# WS2812-Ring_v10.net
KiCad netlist of a schematic drawn in EAGLE
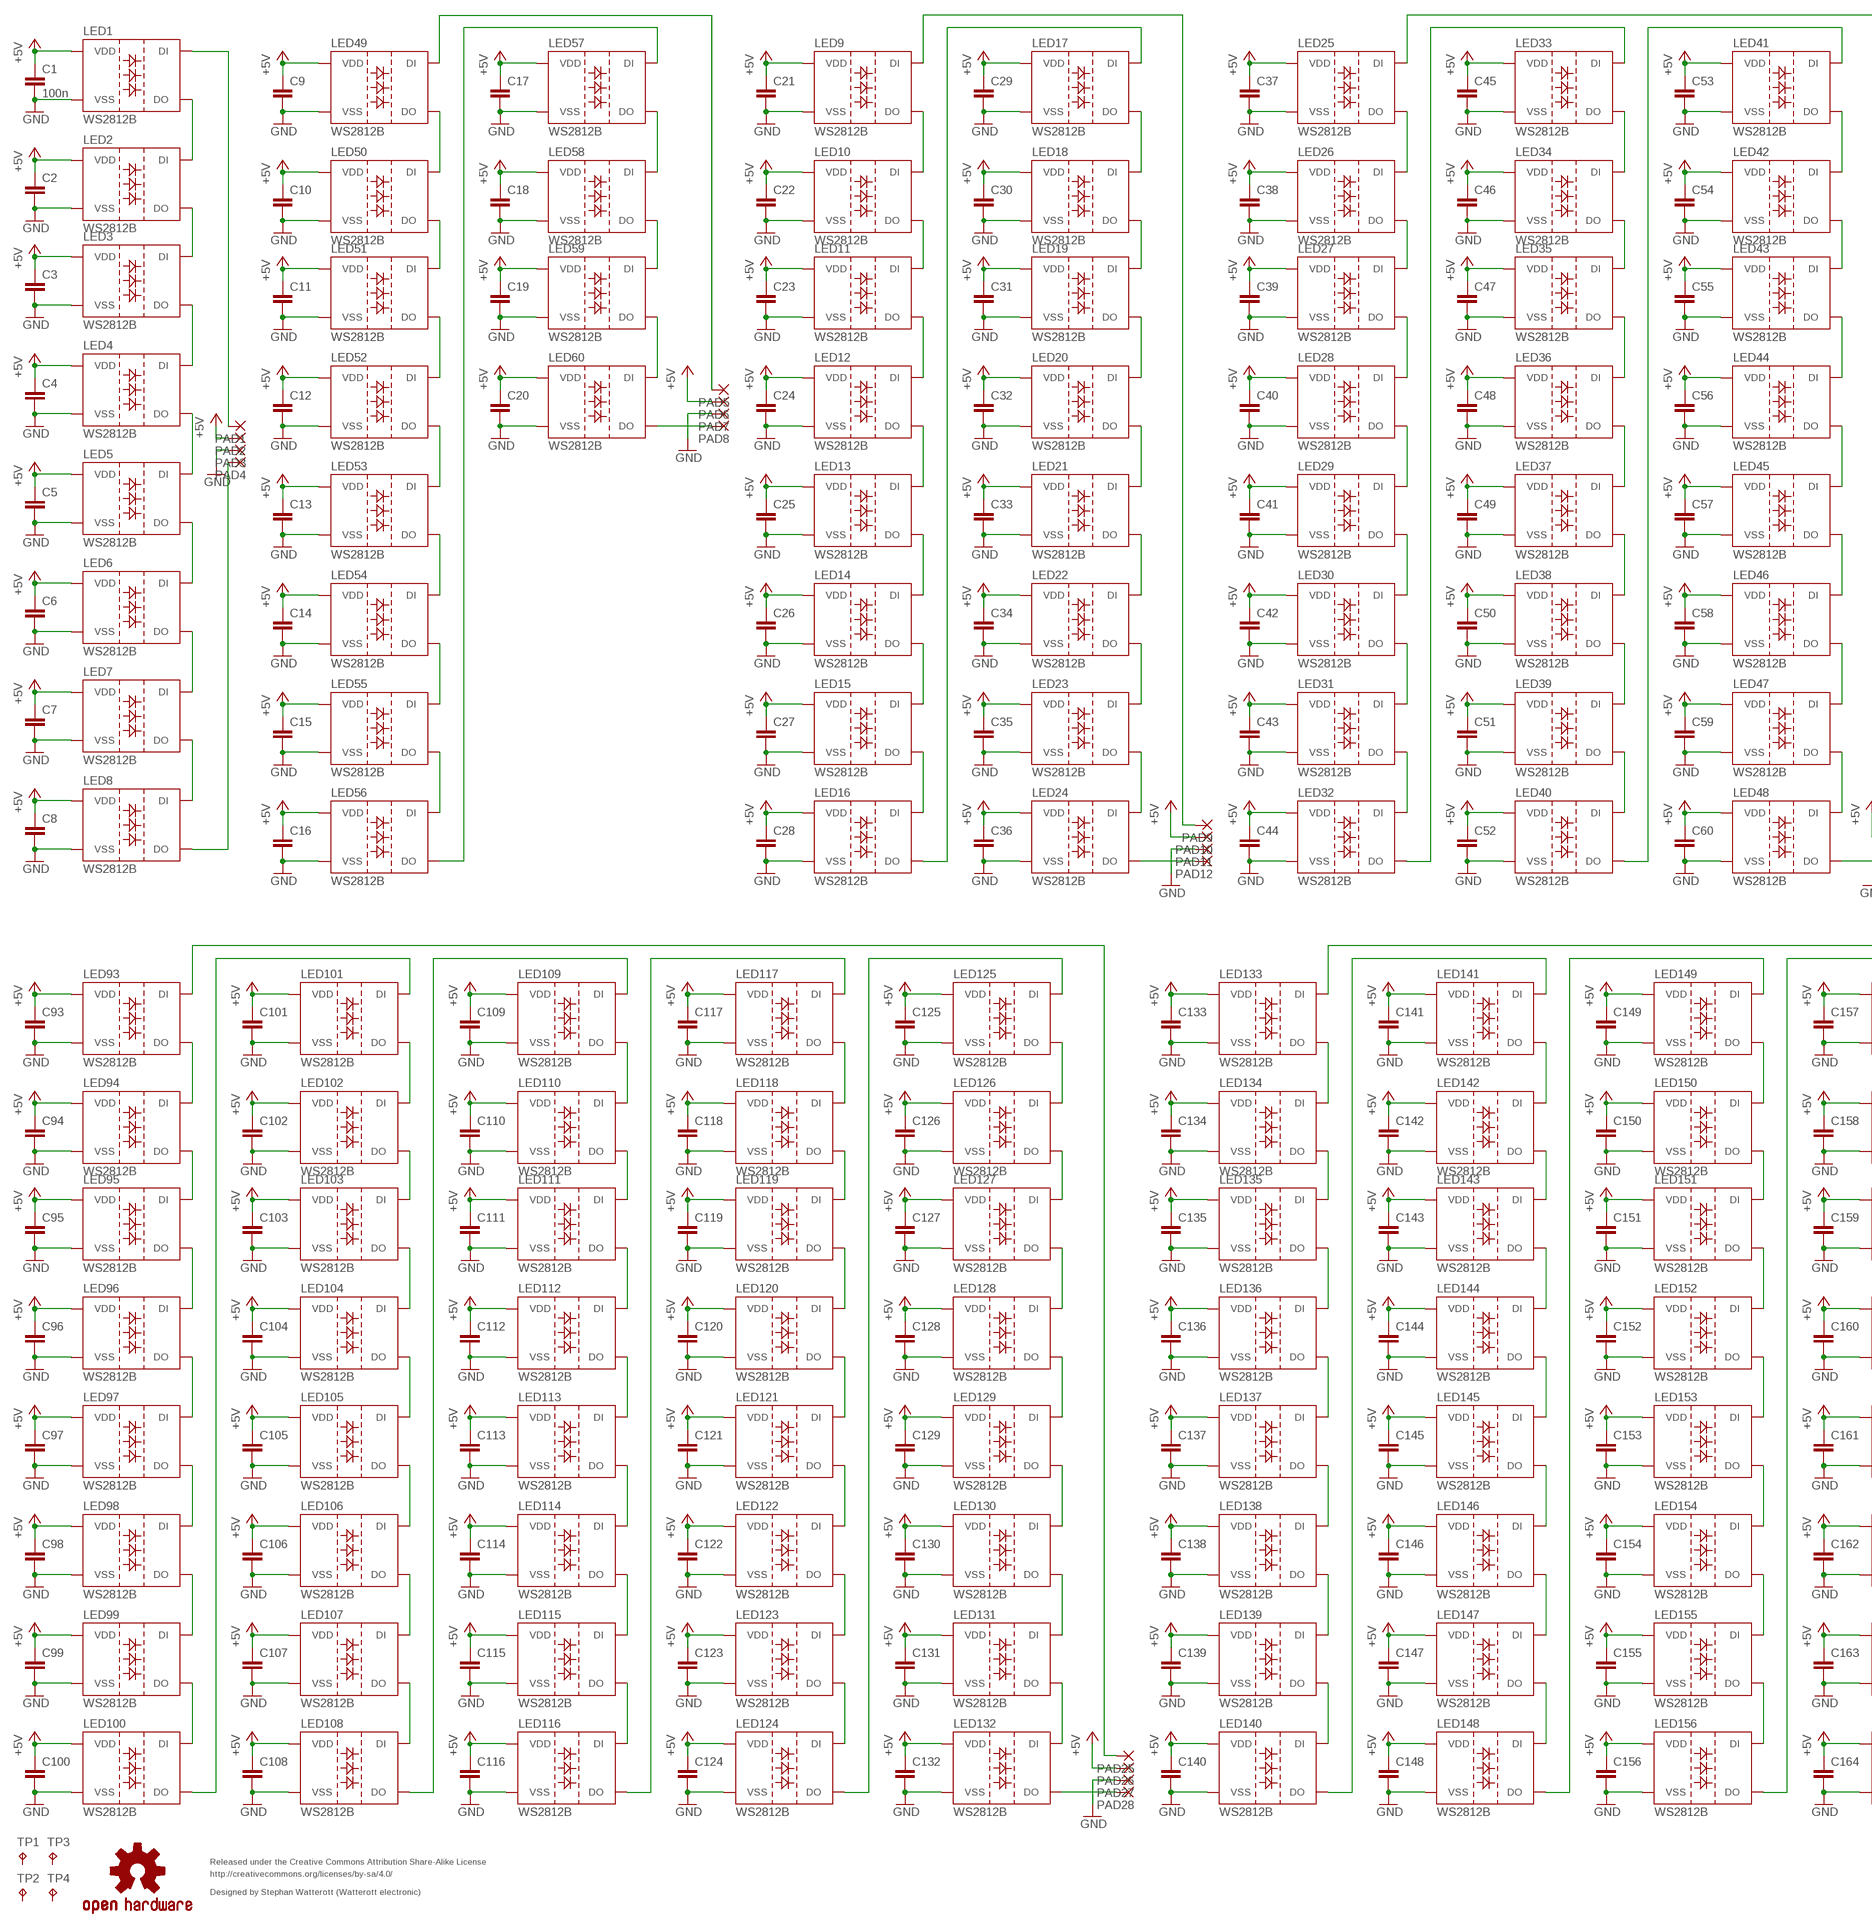
[diagram p0: schematic, sheet 1, part 1 of 2]
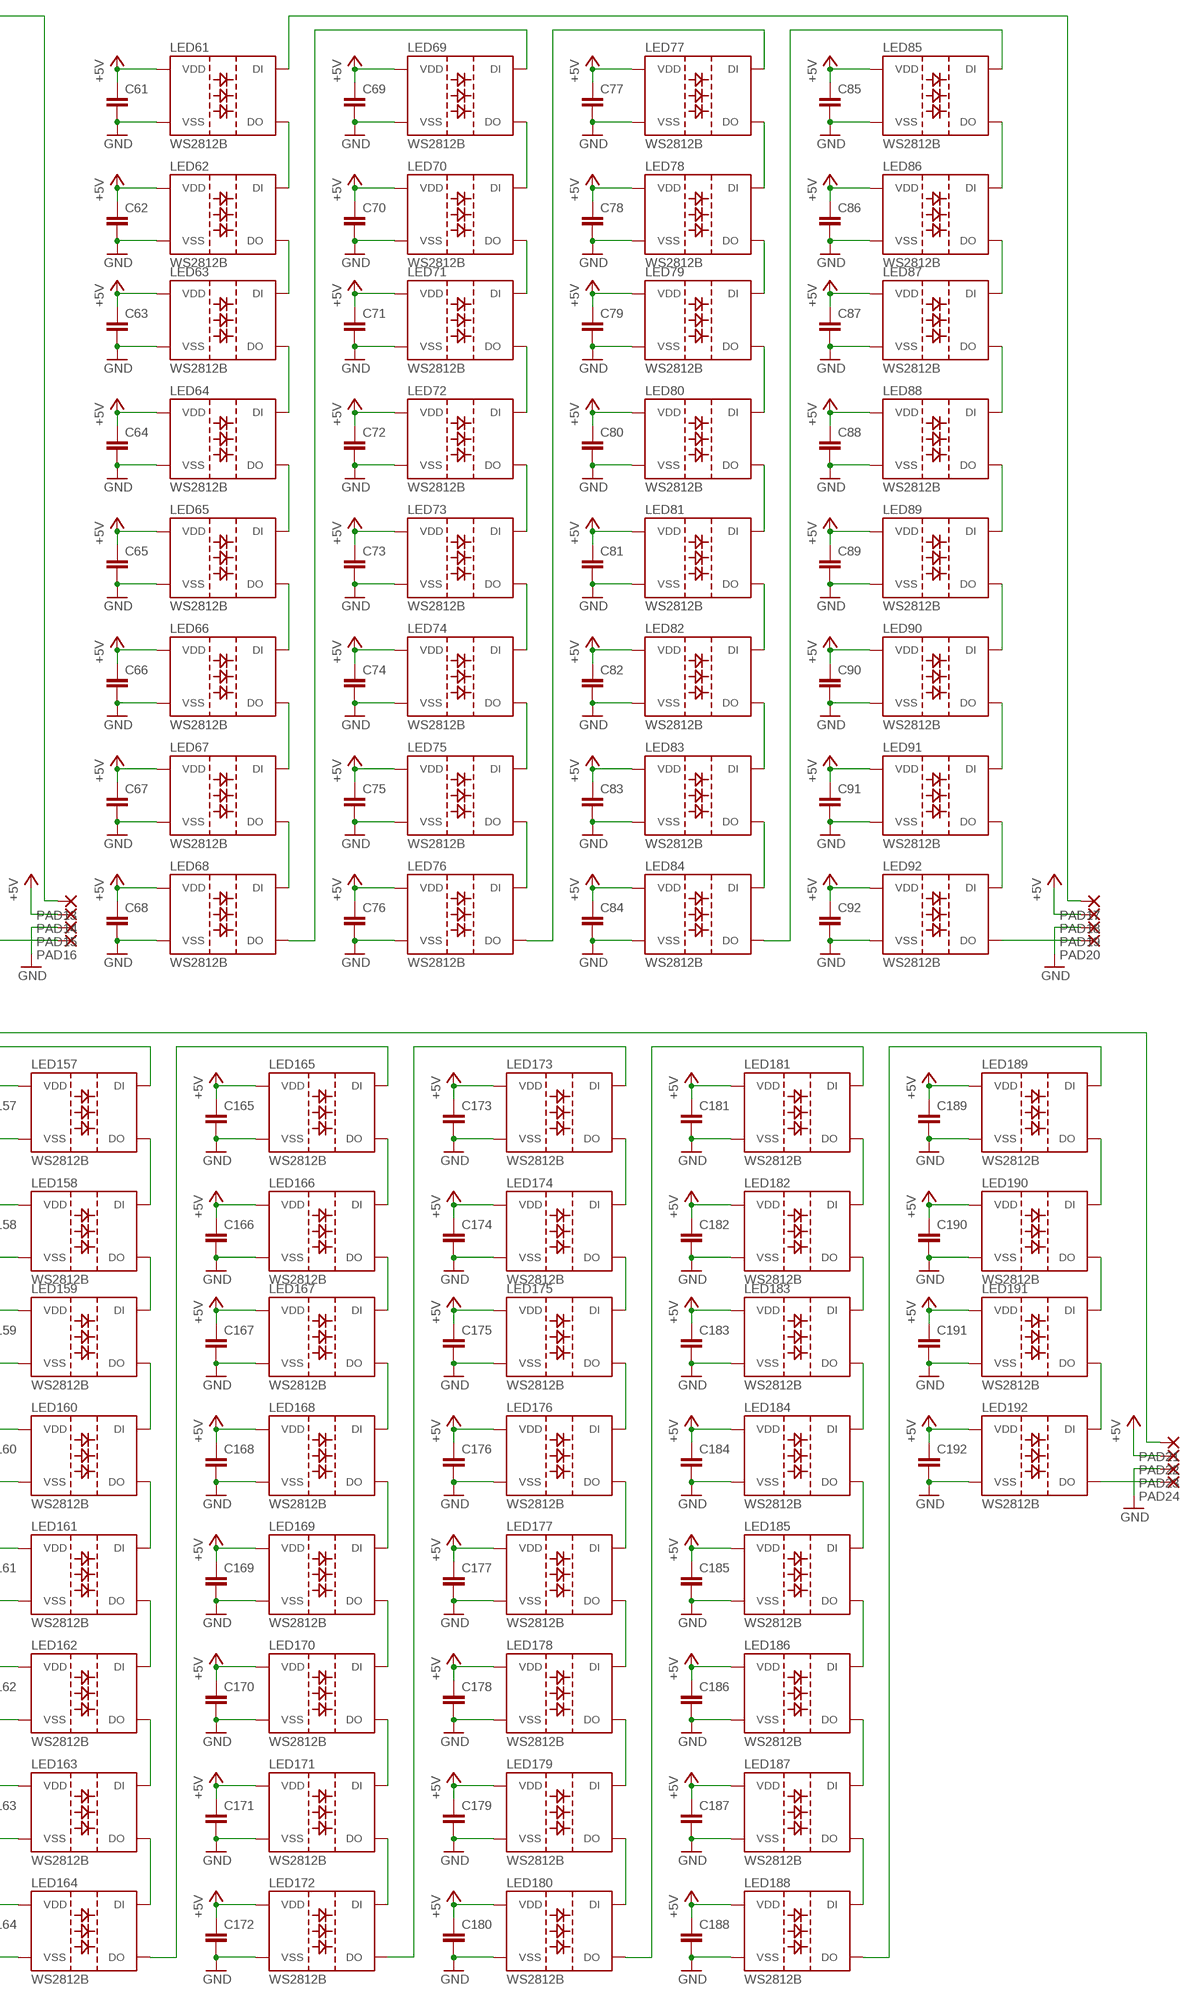
[diagram p1: schematic, sheet 1, part 2 of 2]

(export (version "E")
  (design (tool "Eeschema 10.0.6"))
  (components
    (comp (ref "C1")
      (value "100n")
      (footprint "eagle-import:C0402K")
      (libsource (lib "eagle-import") (part "C-EUC0402K"))
    )
    (comp (ref "C2")
      (value "C-EUC0402K")
      (footprint "eagle-import:C0402K")
      (libsource (lib "eagle-import") (part "C-EUC0402K"))
    )
    (comp (ref "C3")
      (value "C-EUC0402K")
      (footprint "eagle-import:C0402K")
      (libsource (lib "eagle-import") (part "C-EUC0402K"))
    )
    (comp (ref "C4")
      (value "C-EUC0402K")
      (footprint "eagle-import:C0402K")
      (libsource (lib "eagle-import") (part "C-EUC0402K"))
    )
    (comp (ref "C5")
      (value "C-EUC0402K")
      (footprint "eagle-import:C0402K")
      (libsource (lib "eagle-import") (part "C-EUC0402K"))
    )
    (comp (ref "C6")
      (value "C-EUC0402K")
      (footprint "eagle-import:C0402K")
      (libsource (lib "eagle-import") (part "C-EUC0402K"))
    )
    (comp (ref "C7")
      (value "C-EUC0402K")
      (footprint "eagle-import:C0402K")
      (libsource (lib "eagle-import") (part "C-EUC0402K"))
    )
    (comp (ref "C8")
      (value "C-EUC0402K")
      (footprint "eagle-import:C0402K")
      (libsource (lib "eagle-import") (part "C-EUC0402K"))
    )
    (comp (ref "C9")
      (value "C-EUC0402K")
      (footprint "eagle-import:C0402K")
      (libsource (lib "eagle-import") (part "C-EUC0402K"))
    )
    (comp (ref "C10")
      (value "C-EUC0402K")
      (footprint "eagle-import:C0402K")
      (libsource (lib "eagle-import") (part "C-EUC0402K"))
    )
    (comp (ref "C11")
      (value "C-EUC0402K")
      (footprint "eagle-import:C0402K")
      (libsource (lib "eagle-import") (part "C-EUC0402K"))
    )
    (comp (ref "C12")
      (value "C-EUC0402K")
      (footprint "eagle-import:C0402K")
      (libsource (lib "eagle-import") (part "C-EUC0402K"))
    )
    (comp (ref "C13")
      (value "C-EUC0402K")
      (footprint "eagle-import:C0402K")
      (libsource (lib "eagle-import") (part "C-EUC0402K"))
    )
    (comp (ref "C14")
      (value "C-EUC0402K")
      (footprint "eagle-import:C0402K")
      (libsource (lib "eagle-import") (part "C-EUC0402K"))
    )
    (comp (ref "C15")
      (value "C-EUC0402K")
      (footprint "eagle-import:C0402K")
      (libsource (lib "eagle-import") (part "C-EUC0402K"))
    )
    (comp (ref "C16")
      (value "C-EUC0402K")
      (footprint "eagle-import:C0402K")
      (libsource (lib "eagle-import") (part "C-EUC0402K"))
    )
    (comp (ref "C17")
      (value "C-EUC0402K")
      (footprint "eagle-import:C0402K")
      (libsource (lib "eagle-import") (part "C-EUC0402K"))
    )
    (comp (ref "C18")
      (value "C-EUC0402K")
      (footprint "eagle-import:C0402K")
      (libsource (lib "eagle-import") (part "C-EUC0402K"))
    )
    (comp (ref "C19")
      (value "C-EUC0402K")
      (footprint "eagle-import:C0402K")
      (libsource (lib "eagle-import") (part "C-EUC0402K"))
    )
    (comp (ref "C20")
      (value "C-EUC0402K")
      (footprint "eagle-import:C0402K")
      (libsource (lib "eagle-import") (part "C-EUC0402K"))
    )
    (comp (ref "C21")
      (value "C-EUC0402K")
      (footprint "eagle-import:C0402K")
      (libsource (lib "eagle-import") (part "C-EUC0402K"))
    )
    (comp (ref "C22")
      (value "C-EUC0402K")
      (footprint "eagle-import:C0402K")
      (libsource (lib "eagle-import") (part "C-EUC0402K"))
    )
    (comp (ref "C23")
      (value "C-EUC0402K")
      (footprint "eagle-import:C0402K")
      (libsource (lib "eagle-import") (part "C-EUC0402K"))
    )
    (comp (ref "C24")
      (value "C-EUC0402K")
      (footprint "eagle-import:C0402K")
      (libsource (lib "eagle-import") (part "C-EUC0402K"))
    )
    (comp (ref "C25")
      (value "C-EUC0402K")
      (footprint "eagle-import:C0402K")
      (libsource (lib "eagle-import") (part "C-EUC0402K"))
    )
    (comp (ref "C26")
      (value "C-EUC0402K")
      (footprint "eagle-import:C0402K")
      (libsource (lib "eagle-import") (part "C-EUC0402K"))
    )
    (comp (ref "C27")
      (value "C-EUC0402K")
      (footprint "eagle-import:C0402K")
      (libsource (lib "eagle-import") (part "C-EUC0402K"))
    )
    (comp (ref "C28")
      (value "C-EUC0402K")
      (footprint "eagle-import:C0402K")
      (libsource (lib "eagle-import") (part "C-EUC0402K"))
    )
    (comp (ref "C29")
      (value "C-EUC0402K")
      (footprint "eagle-import:C0402K")
      (libsource (lib "eagle-import") (part "C-EUC0402K"))
    )
    (comp (ref "C30")
      (value "C-EUC0402K")
      (footprint "eagle-import:C0402K")
      (libsource (lib "eagle-import") (part "C-EUC0402K"))
    )
    (comp (ref "C31")
      (value "C-EUC0402K")
      (footprint "eagle-import:C0402K")
      (libsource (lib "eagle-import") (part "C-EUC0402K"))
    )
    (comp (ref "C32")
      (value "C-EUC0402K")
      (footprint "eagle-import:C0402K")
      (libsource (lib "eagle-import") (part "C-EUC0402K"))
    )
    (comp (ref "C33")
      (value "C-EUC0402K")
      (footprint "eagle-import:C0402K")
      (libsource (lib "eagle-import") (part "C-EUC0402K"))
    )
    (comp (ref "C34")
      (value "C-EUC0402K")
      (footprint "eagle-import:C0402K")
      (libsource (lib "eagle-import") (part "C-EUC0402K"))
    )
    (comp (ref "C35")
      (value "C-EUC0402K")
      (footprint "eagle-import:C0402K")
      (libsource (lib "eagle-import") (part "C-EUC0402K"))
    )
    (comp (ref "C36")
      (value "C-EUC0402K")
      (footprint "eagle-import:C0402K")
      (libsource (lib "eagle-import") (part "C-EUC0402K"))
    )
    (comp (ref "C37")
      (value "C-EUC0402K")
      (footprint "eagle-import:C0402K")
      (libsource (lib "eagle-import") (part "C-EUC0402K"))
    )
    (comp (ref "C38")
      (value "C-EUC0402K")
      (footprint "eagle-import:C0402K")
      (libsource (lib "eagle-import") (part "C-EUC0402K"))
    )
    (comp (ref "C39")
      (value "C-EUC0402K")
      (footprint "eagle-import:C0402K")
      (libsource (lib "eagle-import") (part "C-EUC0402K"))
    )
    (comp (ref "C40")
      (value "C-EUC0402K")
      (footprint "eagle-import:C0402K")
      (libsource (lib "eagle-import") (part "C-EUC0402K"))
    )
    (comp (ref "C41")
      (value "C-EUC0402K")
      (footprint "eagle-import:C0402K")
      (libsource (lib "eagle-import") (part "C-EUC0402K"))
    )
    (comp (ref "C42")
      (value "C-EUC0402K")
      (footprint "eagle-import:C0402K")
      (libsource (lib "eagle-import") (part "C-EUC0402K"))
    )
    (comp (ref "C43")
      (value "C-EUC0402K")
      (footprint "eagle-import:C0402K")
      (libsource (lib "eagle-import") (part "C-EUC0402K"))
    )
    (comp (ref "C44")
      (value "C-EUC0402K")
      (footprint "eagle-import:C0402K")
      (libsource (lib "eagle-import") (part "C-EUC0402K"))
    )
    (comp (ref "C45")
      (value "C-EUC0402K")
      (footprint "eagle-import:C0402K")
      (libsource (lib "eagle-import") (part "C-EUC0402K"))
    )
    (comp (ref "C46")
      (value "C-EUC0402K")
      (footprint "eagle-import:C0402K")
      (libsource (lib "eagle-import") (part "C-EUC0402K"))
    )
    (comp (ref "C47")
      (value "C-EUC0402K")
      (footprint "eagle-import:C0402K")
      (libsource (lib "eagle-import") (part "C-EUC0402K"))
    )
    (comp (ref "C48")
      (value "C-EUC0402K")
      (footprint "eagle-import:C0402K")
      (libsource (lib "eagle-import") (part "C-EUC0402K"))
    )
    (comp (ref "C49")
      (value "C-EUC0402K")
      (footprint "eagle-import:C0402K")
      (libsource (lib "eagle-import") (part "C-EUC0402K"))
    )
    (comp (ref "C50")
      (value "C-EUC0402K")
      (footprint "eagle-import:C0402K")
      (libsource (lib "eagle-import") (part "C-EUC0402K"))
    )
    (comp (ref "C51")
      (value "C-EUC0402K")
      (footprint "eagle-import:C0402K")
      (libsource (lib "eagle-import") (part "C-EUC0402K"))
    )
    (comp (ref "C52")
      (value "C-EUC0402K")
      (footprint "eagle-import:C0402K")
      (libsource (lib "eagle-import") (part "C-EUC0402K"))
    )
    (comp (ref "C53")
      (value "C-EUC0402K")
      (footprint "eagle-import:C0402K")
      (libsource (lib "eagle-import") (part "C-EUC0402K"))
    )
    (comp (ref "C54")
      (value "C-EUC0402K")
      (footprint "eagle-import:C0402K")
      (libsource (lib "eagle-import") (part "C-EUC0402K"))
    )
    (comp (ref "C55")
      (value "C-EUC0402K")
      (footprint "eagle-import:C0402K")
      (libsource (lib "eagle-import") (part "C-EUC0402K"))
    )
    (comp (ref "C56")
      (value "C-EUC0402K")
      (footprint "eagle-import:C0402K")
      (libsource (lib "eagle-import") (part "C-EUC0402K"))
    )
    (comp (ref "C57")
      (value "C-EUC0402K")
      (footprint "eagle-import:C0402K")
      (libsource (lib "eagle-import") (part "C-EUC0402K"))
    )
    (comp (ref "C58")
      (value "C-EUC0402K")
      (footprint "eagle-import:C0402K")
      (libsource (lib "eagle-import") (part "C-EUC0402K"))
    )
    (comp (ref "C59")
      (value "C-EUC0402K")
      (footprint "eagle-import:C0402K")
      (libsource (lib "eagle-import") (part "C-EUC0402K"))
    )
    (comp (ref "C60")
      (value "C-EUC0402K")
      (footprint "eagle-import:C0402K")
      (libsource (lib "eagle-import") (part "C-EUC0402K"))
    )
    (comp (ref "C61")
      (value "C-EUC0402K")
      (footprint "eagle-import:C0402K")
      (libsource (lib "eagle-import") (part "C-EUC0402K"))
    )
    (comp (ref "C62")
      (value "C-EUC0402K")
      (footprint "eagle-import:C0402K")
      (libsource (lib "eagle-import") (part "C-EUC0402K"))
    )
    (comp (ref "C63")
      (value "C-EUC0402K")
      (footprint "eagle-import:C0402K")
      (libsource (lib "eagle-import") (part "C-EUC0402K"))
    )
    (comp (ref "C64")
      (value "C-EUC0402K")
      (footprint "eagle-import:C0402K")
      (libsource (lib "eagle-import") (part "C-EUC0402K"))
    )
    (comp (ref "C65")
      (value "C-EUC0402K")
      (footprint "eagle-import:C0402K")
      (libsource (lib "eagle-import") (part "C-EUC0402K"))
    )
    (comp (ref "C66")
      (value "C-EUC0402K")
      (footprint "eagle-import:C0402K")
      (libsource (lib "eagle-import") (part "C-EUC0402K"))
    )
    (comp (ref "C67")
      (value "C-EUC0402K")
      (footprint "eagle-import:C0402K")
      (libsource (lib "eagle-import") (part "C-EUC0402K"))
    )
    (comp (ref "C68")
      (value "C-EUC0402K")
      (footprint "eagle-import:C0402K")
      (libsource (lib "eagle-import") (part "C-EUC0402K"))
    )
    (comp (ref "C69")
      (value "C-EUC0402K")
      (footprint "eagle-import:C0402K")
      (libsource (lib "eagle-import") (part "C-EUC0402K"))
    )
    (comp (ref "C70")
      (value "C-EUC0402K")
      (footprint "eagle-import:C0402K")
      (libsource (lib "eagle-import") (part "C-EUC0402K"))
    )
    (comp (ref "C71")
      (value "C-EUC0402K")
      (footprint "eagle-import:C0402K")
      (libsource (lib "eagle-import") (part "C-EUC0402K"))
    )
    (comp (ref "C72")
      (value "C-EUC0402K")
      (footprint "eagle-import:C0402K")
      (libsource (lib "eagle-import") (part "C-EUC0402K"))
    )
    (comp (ref "C73")
      (value "C-EUC0402K")
      (footprint "eagle-import:C0402K")
      (libsource (lib "eagle-import") (part "C-EUC0402K"))
    )
    (comp (ref "C74")
      (value "C-EUC0402K")
      (footprint "eagle-import:C0402K")
      (libsource (lib "eagle-import") (part "C-EUC0402K"))
    )
    (comp (ref "C75")
      (value "C-EUC0402K")
      (footprint "eagle-import:C0402K")
      (libsource (lib "eagle-import") (part "C-EUC0402K"))
    )
    (comp (ref "C76")
      (value "C-EUC0402K")
      (footprint "eagle-import:C0402K")
      (libsource (lib "eagle-import") (part "C-EUC0402K"))
    )
    (comp (ref "C77")
      (value "C-EUC0402K")
      (footprint "eagle-import:C0402K")
      (libsource (lib "eagle-import") (part "C-EUC0402K"))
    )
    (comp (ref "C78")
      (value "C-EUC0402K")
      (footprint "eagle-import:C0402K")
      (libsource (lib "eagle-import") (part "C-EUC0402K"))
    )
    (comp (ref "C79")
      (value "C-EUC0402K")
      (footprint "eagle-import:C0402K")
      (libsource (lib "eagle-import") (part "C-EUC0402K"))
    )
    (comp (ref "C80")
      (value "C-EUC0402K")
      (footprint "eagle-import:C0402K")
      (libsource (lib "eagle-import") (part "C-EUC0402K"))
    )
    (comp (ref "C81")
      (value "C-EUC0402K")
      (footprint "eagle-import:C0402K")
      (libsource (lib "eagle-import") (part "C-EUC0402K"))
    )
    (comp (ref "C82")
      (value "C-EUC0402K")
      (footprint "eagle-import:C0402K")
      (libsource (lib "eagle-import") (part "C-EUC0402K"))
    )
    (comp (ref "C83")
      (value "C-EUC0402K")
      (footprint "eagle-import:C0402K")
      (libsource (lib "eagle-import") (part "C-EUC0402K"))
    )
    (comp (ref "C84")
      (value "C-EUC0402K")
      (footprint "eagle-import:C0402K")
      (libsource (lib "eagle-import") (part "C-EUC0402K"))
    )
    (comp (ref "C85")
      (value "C-EUC0402K")
      (footprint "eagle-import:C0402K")
      (libsource (lib "eagle-import") (part "C-EUC0402K"))
    )
    (comp (ref "C86")
      (value "C-EUC0402K")
      (footprint "eagle-import:C0402K")
      (libsource (lib "eagle-import") (part "C-EUC0402K"))
    )
    (comp (ref "C87")
      (value "C-EUC0402K")
      (footprint "eagle-import:C0402K")
      (libsource (lib "eagle-import") (part "C-EUC0402K"))
    )
    (comp (ref "C88")
      (value "C-EUC0402K")
      (footprint "eagle-import:C0402K")
      (libsource (lib "eagle-import") (part "C-EUC0402K"))
    )
    (comp (ref "C89")
      (value "C-EUC0402K")
      (footprint "eagle-import:C0402K")
      (libsource (lib "eagle-import") (part "C-EUC0402K"))
    )
    (comp (ref "C90")
      (value "C-EUC0402K")
      (footprint "eagle-import:C0402K")
      (libsource (lib "eagle-import") (part "C-EUC0402K"))
    )
    (comp (ref "C91")
      (value "C-EUC0402K")
      (footprint "eagle-import:C0402K")
      (libsource (lib "eagle-import") (part "C-EUC0402K"))
    )
    (comp (ref "C92")
      (value "C-EUC0402K")
      (footprint "eagle-import:C0402K")
      (libsource (lib "eagle-import") (part "C-EUC0402K"))
    )
    (comp (ref "C93")
      (value "C-EUC0402K")
      (footprint "eagle-import:C0402K")
      (libsource (lib "eagle-import") (part "C-EUC0402K"))
    )
    (comp (ref "C94")
      (value "C-EUC0402K")
      (footprint "eagle-import:C0402K")
      (libsource (lib "eagle-import") (part "C-EUC0402K"))
    )
    (comp (ref "C95")
      (value "C-EUC0402K")
      (footprint "eagle-import:C0402K")
      (libsource (lib "eagle-import") (part "C-EUC0402K"))
    )
    (comp (ref "C96")
      (value "C-EUC0402K")
      (footprint "eagle-import:C0402K")
      (libsource (lib "eagle-import") (part "C-EUC0402K"))
    )
    (comp (ref "C97")
      (value "C-EUC0402K")
      (footprint "eagle-import:C0402K")
      (libsource (lib "eagle-import") (part "C-EUC0402K"))
    )
    (comp (ref "C98")
      (value "C-EUC0402K")
      (footprint "eagle-import:C0402K")
      (libsource (lib "eagle-import") (part "C-EUC0402K"))
    )
    (comp (ref "C99")
      (value "C-EUC0402K")
      (footprint "eagle-import:C0402K")
      (libsource (lib "eagle-import") (part "C-EUC0402K"))
    )
    (comp (ref "C100")
      (value "C-EUC0402K")
      (footprint "eagle-import:C0402K")
      (libsource (lib "eagle-import") (part "C-EUC0402K"))
    )
    (comp (ref "C101")
      (value "C-EUC0402K")
      (footprint "eagle-import:C0402K")
      (libsource (lib "eagle-import") (part "C-EUC0402K"))
    )
    (comp (ref "C102")
      (value "C-EUC0402K")
      (footprint "eagle-import:C0402K")
      (libsource (lib "eagle-import") (part "C-EUC0402K"))
    )
    (comp (ref "C103")
      (value "C-EUC0402K")
      (footprint "eagle-import:C0402K")
      (libsource (lib "eagle-import") (part "C-EUC0402K"))
    )
    (comp (ref "C104")
      (value "C-EUC0402K")
      (footprint "eagle-import:C0402K")
      (libsource (lib "eagle-import") (part "C-EUC0402K"))
    )
    (comp (ref "C105")
      (value "C-EUC0402K")
      (footprint "eagle-import:C0402K")
      (libsource (lib "eagle-import") (part "C-EUC0402K"))
    )
    (comp (ref "C106")
      (value "C-EUC0402K")
      (footprint "eagle-import:C0402K")
      (libsource (lib "eagle-import") (part "C-EUC0402K"))
    )
    (comp (ref "C107")
      (value "C-EUC0402K")
      (footprint "eagle-import:C0402K")
      (libsource (lib "eagle-import") (part "C-EUC0402K"))
    )
    (comp (ref "C108")
      (value "C-EUC0402K")
      (footprint "eagle-import:C0402K")
      (libsource (lib "eagle-import") (part "C-EUC0402K"))
    )
    (comp (ref "C109")
      (value "C-EUC0402K")
      (footprint "eagle-import:C0402K")
      (libsource (lib "eagle-import") (part "C-EUC0402K"))
    )
    (comp (ref "C110")
      (value "C-EUC0402K")
      (footprint "eagle-import:C0402K")
      (libsource (lib "eagle-import") (part "C-EUC0402K"))
    )
    (comp (ref "C111")
      (value "C-EUC0402K")
      (footprint "eagle-import:C0402K")
      (libsource (lib "eagle-import") (part "C-EUC0402K"))
    )
    (comp (ref "C112")
      (value "C-EUC0402K")
      (footprint "eagle-import:C0402K")
      (libsource (lib "eagle-import") (part "C-EUC0402K"))
    )
    (comp (ref "C113")
      (value "C-EUC0402K")
      (footprint "eagle-import:C0402K")
      (libsource (lib "eagle-import") (part "C-EUC0402K"))
    )
    (comp (ref "C114")
      (value "C-EUC0402K")
      (footprint "eagle-import:C0402K")
      (libsource (lib "eagle-import") (part "C-EUC0402K"))
    )
    (comp (ref "C115")
      (value "C-EUC0402K")
      (footprint "eagle-import:C0402K")
      (libsource (lib "eagle-import") (part "C-EUC0402K"))
    )
    (comp (ref "C116")
      (value "C-EUC0402K")
      (footprint "eagle-import:C0402K")
      (libsource (lib "eagle-import") (part "C-EUC0402K"))
    )
    (comp (ref "C117")
      (value "C-EUC0402K")
      (footprint "eagle-import:C0402K")
      (libsource (lib "eagle-import") (part "C-EUC0402K"))
    )
    (comp (ref "C118")
      (value "C-EUC0402K")
      (footprint "eagle-import:C0402K")
      (libsource (lib "eagle-import") (part "C-EUC0402K"))
    )
    (comp (ref "C119")
      (value "C-EUC0402K")
      (footprint "eagle-import:C0402K")
      (libsource (lib "eagle-import") (part "C-EUC0402K"))
    )
    (comp (ref "C120")
      (value "C-EUC0402K")
      (footprint "eagle-import:C0402K")
      (libsource (lib "eagle-import") (part "C-EUC0402K"))
    )
    (comp (ref "C121")
      (value "C-EUC0402K")
      (footprint "eagle-import:C0402K")
      (libsource (lib "eagle-import") (part "C-EUC0402K"))
    )
    (comp (ref "C122")
      (value "C-EUC0402K")
      (footprint "eagle-import:C0402K")
      (libsource (lib "eagle-import") (part "C-EUC0402K"))
    )
    (comp (ref "C123")
      (value "C-EUC0402K")
      (footprint "eagle-import:C0402K")
      (libsource (lib "eagle-import") (part "C-EUC0402K"))
    )
    (comp (ref "C124")
      (value "C-EUC0402K")
      (footprint "eagle-import:C0402K")
      (libsource (lib "eagle-import") (part "C-EUC0402K"))
    )
    (comp (ref "C125")
      (value "C-EUC0402K")
      (footprint "eagle-import:C0402K")
      (libsource (lib "eagle-import") (part "C-EUC0402K"))
    )
    (comp (ref "C126")
      (value "C-EUC0402K")
      (footprint "eagle-import:C0402K")
      (libsource (lib "eagle-import") (part "C-EUC0402K"))
    )
    (comp (ref "C127")
      (value "C-EUC0402K")
      (footprint "eagle-import:C0402K")
      (libsource (lib "eagle-import") (part "C-EUC0402K"))
    )
    (comp (ref "C128")
      (value "C-EUC0402K")
      (footprint "eagle-import:C0402K")
      (libsource (lib "eagle-import") (part "C-EUC0402K"))
    )
    (comp (ref "C129")
      (value "C-EUC0402K")
      (footprint "eagle-import:C0402K")
      (libsource (lib "eagle-import") (part "C-EUC0402K"))
    )
    (comp (ref "C130")
      (value "C-EUC0402K")
      (footprint "eagle-import:C0402K")
      (libsource (lib "eagle-import") (part "C-EUC0402K"))
    )
    (comp (ref "C131")
      (value "C-EUC0402K")
      (footprint "eagle-import:C0402K")
      (libsource (lib "eagle-import") (part "C-EUC0402K"))
    )
    (comp (ref "C132")
      (value "C-EUC0402K")
      (footprint "eagle-import:C0402K")
      (libsource (lib "eagle-import") (part "C-EUC0402K"))
    )
    (comp (ref "C133")
      (value "C-EUC0402K")
      (footprint "eagle-import:C0402K")
      (libsource (lib "eagle-import") (part "C-EUC0402K"))
    )
    (comp (ref "C134")
      (value "C-EUC0402K")
      (footprint "eagle-import:C0402K")
      (libsource (lib "eagle-import") (part "C-EUC0402K"))
    )
    (comp (ref "C135")
      (value "C-EUC0402K")
      (footprint "eagle-import:C0402K")
      (libsource (lib "eagle-import") (part "C-EUC0402K"))
    )
    (comp (ref "C136")
      (value "C-EUC0402K")
      (footprint "eagle-import:C0402K")
      (libsource (lib "eagle-import") (part "C-EUC0402K"))
    )
    (comp (ref "C137")
      (value "C-EUC0402K")
      (footprint "eagle-import:C0402K")
      (libsource (lib "eagle-import") (part "C-EUC0402K"))
    )
    (comp (ref "C138")
      (value "C-EUC0402K")
      (footprint "eagle-import:C0402K")
      (libsource (lib "eagle-import") (part "C-EUC0402K"))
    )
    (comp (ref "C139")
      (value "C-EUC0402K")
      (footprint "eagle-import:C0402K")
      (libsource (lib "eagle-import") (part "C-EUC0402K"))
    )
    (comp (ref "C140")
      (value "C-EUC0402K")
      (footprint "eagle-import:C0402K")
      (libsource (lib "eagle-import") (part "C-EUC0402K"))
    )
    (comp (ref "C141")
      (value "C-EUC0402K")
      (footprint "eagle-import:C0402K")
      (libsource (lib "eagle-import") (part "C-EUC0402K"))
    )
    (comp (ref "C142")
      (value "C-EUC0402K")
      (footprint "eagle-import:C0402K")
      (libsource (lib "eagle-import") (part "C-EUC0402K"))
    )
    (comp (ref "C143")
      (value "C-EUC0402K")
      (footprint "eagle-import:C0402K")
      (libsource (lib "eagle-import") (part "C-EUC0402K"))
    )
    (comp (ref "C144")
      (value "C-EUC0402K")
      (footprint "eagle-import:C0402K")
      (libsource (lib "eagle-import") (part "C-EUC0402K"))
    )
    (comp (ref "C145")
      (value "C-EUC0402K")
      (footprint "eagle-import:C0402K")
      (libsource (lib "eagle-import") (part "C-EUC0402K"))
    )
    (comp (ref "C146")
      (value "C-EUC0402K")
      (footprint "eagle-import:C0402K")
      (libsource (lib "eagle-import") (part "C-EUC0402K"))
    )
    (comp (ref "C147")
      (value "C-EUC0402K")
      (footprint "eagle-import:C0402K")
      (libsource (lib "eagle-import") (part "C-EUC0402K"))
    )
    (comp (ref "C148")
      (value "C-EUC0402K")
      (footprint "eagle-import:C0402K")
      (libsource (lib "eagle-import") (part "C-EUC0402K"))
    )
    (comp (ref "C149")
      (value "C-EUC0402K")
      (footprint "eagle-import:C0402K")
      (libsource (lib "eagle-import") (part "C-EUC0402K"))
    )
    (comp (ref "C150")
      (value "C-EUC0402K")
      (footprint "eagle-import:C0402K")
      (libsource (lib "eagle-import") (part "C-EUC0402K"))
    )
    (comp (ref "C151")
      (value "C-EUC0402K")
      (footprint "eagle-import:C0402K")
      (libsource (lib "eagle-import") (part "C-EUC0402K"))
    )
    (comp (ref "C152")
      (value "C-EUC0402K")
      (footprint "eagle-import:C0402K")
      (libsource (lib "eagle-import") (part "C-EUC0402K"))
    )
    (comp (ref "C153")
      (value "C-EUC0402K")
      (footprint "eagle-import:C0402K")
      (libsource (lib "eagle-import") (part "C-EUC0402K"))
    )
    (comp (ref "C154")
      (value "C-EUC0402K")
      (footprint "eagle-import:C0402K")
      (libsource (lib "eagle-import") (part "C-EUC0402K"))
    )
    (comp (ref "C155")
      (value "C-EUC0402K")
      (footprint "eagle-import:C0402K")
      (libsource (lib "eagle-import") (part "C-EUC0402K"))
    )
    (comp (ref "C156")
      (value "C-EUC0402K")
      (footprint "eagle-import:C0402K")
      (libsource (lib "eagle-import") (part "C-EUC0402K"))
    )
    (comp (ref "C157")
      (value "C-EUC0402K")
      (footprint "eagle-import:C0402K")
      (libsource (lib "eagle-import") (part "C-EUC0402K"))
    )
    (comp (ref "C158")
      (value "C-EUC0402K")
      (footprint "eagle-import:C0402K")
      (libsource (lib "eagle-import") (part "C-EUC0402K"))
    )
    (comp (ref "C159")
      (value "C-EUC0402K")
      (footprint "eagle-import:C0402K")
      (libsource (lib "eagle-import") (part "C-EUC0402K"))
    )
    (comp (ref "C160")
      (value "C-EUC0402K")
      (footprint "eagle-import:C0402K")
      (libsource (lib "eagle-import") (part "C-EUC0402K"))
    )
    (comp (ref "C161")
      (value "C-EUC0402K")
      (footprint "eagle-import:C0402K")
      (libsource (lib "eagle-import") (part "C-EUC0402K"))
    )
    (comp (ref "C162")
      (value "C-EUC0402K")
      (footprint "eagle-import:C0402K")
      (libsource (lib "eagle-import") (part "C-EUC0402K"))
    )
    (comp (ref "C163")
      (value "C-EUC0402K")
      (footprint "eagle-import:C0402K")
      (libsource (lib "eagle-import") (part "C-EUC0402K"))
    )
    (comp (ref "C164")
      (value "C-EUC0402K")
      (footprint "eagle-import:C0402K")
      (libsource (lib "eagle-import") (part "C-EUC0402K"))
    )
    (comp (ref "C165")
      (value "C-EUC0402K")
      (footprint "eagle-import:C0402K")
      (libsource (lib "eagle-import") (part "C-EUC0402K"))
    )
    (comp (ref "C166")
      (value "C-EUC0402K")
      (footprint "eagle-import:C0402K")
      (libsource (lib "eagle-import") (part "C-EUC0402K"))
    )
    (comp (ref "C167")
      (value "C-EUC0402K")
      (footprint "eagle-import:C0402K")
      (libsource (lib "eagle-import") (part "C-EUC0402K"))
    )
    (comp (ref "C168")
      (value "C-EUC0402K")
      (footprint "eagle-import:C0402K")
      (libsource (lib "eagle-import") (part "C-EUC0402K"))
    )
    (comp (ref "C169")
      (value "C-EUC0402K")
      (footprint "eagle-import:C0402K")
      (libsource (lib "eagle-import") (part "C-EUC0402K"))
    )
    (comp (ref "C170")
      (value "C-EUC0402K")
      (footprint "eagle-import:C0402K")
      (libsource (lib "eagle-import") (part "C-EUC0402K"))
    )
    (comp (ref "C171")
      (value "C-EUC0402K")
      (footprint "eagle-import:C0402K")
      (libsource (lib "eagle-import") (part "C-EUC0402K"))
    )
    (comp (ref "C172")
      (value "C-EUC0402K")
      (footprint "eagle-import:C0402K")
      (libsource (lib "eagle-import") (part "C-EUC0402K"))
    )
    (comp (ref "C173")
      (value "C-EUC0402K")
      (footprint "eagle-import:C0402K")
      (libsource (lib "eagle-import") (part "C-EUC0402K"))
    )
    (comp (ref "C174")
      (value "C-EUC0402K")
      (footprint "eagle-import:C0402K")
      (libsource (lib "eagle-import") (part "C-EUC0402K"))
    )
    (comp (ref "C175")
      (value "C-EUC0402K")
      (footprint "eagle-import:C0402K")
      (libsource (lib "eagle-import") (part "C-EUC0402K"))
    )
    (comp (ref "C176")
      (value "C-EUC0402K")
      (footprint "eagle-import:C0402K")
      (libsource (lib "eagle-import") (part "C-EUC0402K"))
    )
    (comp (ref "C177")
      (value "C-EUC0402K")
      (footprint "eagle-import:C0402K")
      (libsource (lib "eagle-import") (part "C-EUC0402K"))
    )
    (comp (ref "C178")
      (value "C-EUC0402K")
      (footprint "eagle-import:C0402K")
      (libsource (lib "eagle-import") (part "C-EUC0402K"))
    )
    (comp (ref "C179")
      (value "C-EUC0402K")
      (footprint "eagle-import:C0402K")
      (libsource (lib "eagle-import") (part "C-EUC0402K"))
    )
    (comp (ref "C180")
      (value "C-EUC0402K")
      (footprint "eagle-import:C0402K")
      (libsource (lib "eagle-import") (part "C-EUC0402K"))
    )
    (comp (ref "C181")
      (value "C-EUC0402K")
      (footprint "eagle-import:C0402K")
      (libsource (lib "eagle-import") (part "C-EUC0402K"))
    )
    (comp (ref "C182")
      (value "C-EUC0402K")
      (footprint "eagle-import:C0402K")
      (libsource (lib "eagle-import") (part "C-EUC0402K"))
    )
    (comp (ref "C183")
      (value "C-EUC0402K")
      (footprint "eagle-import:C0402K")
      (libsource (lib "eagle-import") (part "C-EUC0402K"))
    )
    (comp (ref "C184")
      (value "C-EUC0402K")
      (footprint "eagle-import:C0402K")
      (libsource (lib "eagle-import") (part "C-EUC0402K"))
    )
    (comp (ref "C185")
      (value "C-EUC0402K")
      (footprint "eagle-import:C0402K")
      (libsource (lib "eagle-import") (part "C-EUC0402K"))
    )
    (comp (ref "C186")
      (value "C-EUC0402K")
      (footprint "eagle-import:C0402K")
      (libsource (lib "eagle-import") (part "C-EUC0402K"))
    )
    (comp (ref "C187")
      (value "C-EUC0402K")
      (footprint "eagle-import:C0402K")
      (libsource (lib "eagle-import") (part "C-EUC0402K"))
    )
    (comp (ref "C188")
      (value "C-EUC0402K")
      (footprint "eagle-import:C0402K")
      (libsource (lib "eagle-import") (part "C-EUC0402K"))
    )
    (comp (ref "C189")
      (value "C-EUC0402K")
      (footprint "eagle-import:C0402K")
      (libsource (lib "eagle-import") (part "C-EUC0402K"))
    )
    (comp (ref "C190")
      (value "C-EUC0402K")
      (footprint "eagle-import:C0402K")
      (libsource (lib "eagle-import") (part "C-EUC0402K"))
    )
    (comp (ref "C191")
      (value "C-EUC0402K")
      (footprint "eagle-import:C0402K")
      (libsource (lib "eagle-import") (part "C-EUC0402K"))
    )
    (comp (ref "C192")
      (value "C-EUC0402K")
      (footprint "eagle-import:C0402K")
      (libsource (lib "eagle-import") (part "C-EUC0402K"))
    )
    (comp (ref "LED1")
      (value "WS2812B")
      (footprint "eagle-import:WS2812B")
      (libsource (lib "eagle-import") (part "WS2812B"))
    )
    (comp (ref "LED2")
      (value "WS2812B")
      (footprint "eagle-import:WS2812B")
      (libsource (lib "eagle-import") (part "WS2812B"))
    )
    (comp (ref "LED3")
      (value "WS2812B")
      (footprint "eagle-import:WS2812B")
      (libsource (lib "eagle-import") (part "WS2812B"))
    )
    (comp (ref "LED4")
      (value "WS2812B")
      (footprint "eagle-import:WS2812B")
      (libsource (lib "eagle-import") (part "WS2812B"))
    )
    (comp (ref "LED5")
      (value "WS2812B")
      (footprint "eagle-import:WS2812B")
      (libsource (lib "eagle-import") (part "WS2812B"))
    )
    (comp (ref "LED6")
      (value "WS2812B")
      (footprint "eagle-import:WS2812B")
      (libsource (lib "eagle-import") (part "WS2812B"))
    )
    (comp (ref "LED7")
      (value "WS2812B")
      (footprint "eagle-import:WS2812B")
      (libsource (lib "eagle-import") (part "WS2812B"))
    )
    (comp (ref "LED8")
      (value "WS2812B")
      (footprint "eagle-import:WS2812B")
      (libsource (lib "eagle-import") (part "WS2812B"))
    )
    (comp (ref "LED9")
      (value "WS2812B")
      (footprint "eagle-import:WS2812B")
      (libsource (lib "eagle-import") (part "WS2812B"))
    )
    (comp (ref "LED10")
      (value "WS2812B")
      (footprint "eagle-import:WS2812B")
      (libsource (lib "eagle-import") (part "WS2812B"))
    )
    (comp (ref "LED11")
      (value "WS2812B")
      (footprint "eagle-import:WS2812B")
      (libsource (lib "eagle-import") (part "WS2812B"))
    )
    (comp (ref "LED12")
      (value "WS2812B")
      (footprint "eagle-import:WS2812B")
      (libsource (lib "eagle-import") (part "WS2812B"))
    )
    (comp (ref "LED13")
      (value "WS2812B")
      (footprint "eagle-import:WS2812B")
      (libsource (lib "eagle-import") (part "WS2812B"))
    )
    (comp (ref "LED14")
      (value "WS2812B")
      (footprint "eagle-import:WS2812B")
      (libsource (lib "eagle-import") (part "WS2812B"))
    )
    (comp (ref "LED15")
      (value "WS2812B")
      (footprint "eagle-import:WS2812B")
      (libsource (lib "eagle-import") (part "WS2812B"))
    )
    (comp (ref "LED16")
      (value "WS2812B")
      (footprint "eagle-import:WS2812B")
      (libsource (lib "eagle-import") (part "WS2812B"))
    )
    (comp (ref "LED17")
      (value "WS2812B")
      (footprint "eagle-import:WS2812B")
      (libsource (lib "eagle-import") (part "WS2812B"))
    )
    (comp (ref "LED18")
      (value "WS2812B")
      (footprint "eagle-import:WS2812B")
      (libsource (lib "eagle-import") (part "WS2812B"))
    )
    (comp (ref "LED19")
      (value "WS2812B")
      (footprint "eagle-import:WS2812B")
      (libsource (lib "eagle-import") (part "WS2812B"))
    )
    (comp (ref "LED20")
      (value "WS2812B")
      (footprint "eagle-import:WS2812B")
      (libsource (lib "eagle-import") (part "WS2812B"))
    )
    (comp (ref "LED21")
      (value "WS2812B")
      (footprint "eagle-import:WS2812B")
      (libsource (lib "eagle-import") (part "WS2812B"))
    )
    (comp (ref "LED22")
      (value "WS2812B")
      (footprint "eagle-import:WS2812B")
      (libsource (lib "eagle-import") (part "WS2812B"))
    )
    (comp (ref "LED23")
      (value "WS2812B")
      (footprint "eagle-import:WS2812B")
      (libsource (lib "eagle-import") (part "WS2812B"))
    )
    (comp (ref "LED24")
      (value "WS2812B")
      (footprint "eagle-import:WS2812B")
      (libsource (lib "eagle-import") (part "WS2812B"))
    )
    (comp (ref "LED25")
      (value "WS2812B")
      (footprint "eagle-import:WS2812B")
      (libsource (lib "eagle-import") (part "WS2812B"))
    )
    (comp (ref "LED26")
      (value "WS2812B")
      (footprint "eagle-import:WS2812B")
      (libsource (lib "eagle-import") (part "WS2812B"))
    )
    (comp (ref "LED27")
      (value "WS2812B")
      (footprint "eagle-import:WS2812B")
      (libsource (lib "eagle-import") (part "WS2812B"))
    )
    (comp (ref "LED28")
      (value "WS2812B")
      (footprint "eagle-import:WS2812B")
      (libsource (lib "eagle-import") (part "WS2812B"))
    )
    (comp (ref "LED29")
      (value "WS2812B")
      (footprint "eagle-import:WS2812B")
      (libsource (lib "eagle-import") (part "WS2812B"))
    )
    (comp (ref "LED30")
      (value "WS2812B")
      (footprint "eagle-import:WS2812B")
      (libsource (lib "eagle-import") (part "WS2812B"))
    )
    (comp (ref "LED31")
      (value "WS2812B")
      (footprint "eagle-import:WS2812B")
      (libsource (lib "eagle-import") (part "WS2812B"))
    )
    (comp (ref "LED32")
      (value "WS2812B")
      (footprint "eagle-import:WS2812B")
      (libsource (lib "eagle-import") (part "WS2812B"))
    )
    (comp (ref "LED33")
      (value "WS2812B")
      (footprint "eagle-import:WS2812B")
      (libsource (lib "eagle-import") (part "WS2812B"))
    )
    (comp (ref "LED34")
      (value "WS2812B")
      (footprint "eagle-import:WS2812B")
      (libsource (lib "eagle-import") (part "WS2812B"))
    )
    (comp (ref "LED35")
      (value "WS2812B")
      (footprint "eagle-import:WS2812B")
      (libsource (lib "eagle-import") (part "WS2812B"))
    )
    (comp (ref "LED36")
      (value "WS2812B")
      (footprint "eagle-import:WS2812B")
      (libsource (lib "eagle-import") (part "WS2812B"))
    )
    (comp (ref "LED37")
      (value "WS2812B")
      (footprint "eagle-import:WS2812B")
      (libsource (lib "eagle-import") (part "WS2812B"))
    )
    (comp (ref "LED38")
      (value "WS2812B")
      (footprint "eagle-import:WS2812B")
      (libsource (lib "eagle-import") (part "WS2812B"))
    )
    (comp (ref "LED39")
      (value "WS2812B")
      (footprint "eagle-import:WS2812B")
      (libsource (lib "eagle-import") (part "WS2812B"))
    )
    (comp (ref "LED40")
      (value "WS2812B")
      (footprint "eagle-import:WS2812B")
      (libsource (lib "eagle-import") (part "WS2812B"))
    )
    (comp (ref "LED41")
      (value "WS2812B")
      (footprint "eagle-import:WS2812B")
      (libsource (lib "eagle-import") (part "WS2812B"))
    )
    (comp (ref "LED42")
      (value "WS2812B")
      (footprint "eagle-import:WS2812B")
      (libsource (lib "eagle-import") (part "WS2812B"))
    )
    (comp (ref "LED43")
      (value "WS2812B")
      (footprint "eagle-import:WS2812B")
      (libsource (lib "eagle-import") (part "WS2812B"))
    )
    (comp (ref "LED44")
      (value "WS2812B")
      (footprint "eagle-import:WS2812B")
      (libsource (lib "eagle-import") (part "WS2812B"))
    )
    (comp (ref "LED45")
      (value "WS2812B")
      (footprint "eagle-import:WS2812B")
      (libsource (lib "eagle-import") (part "WS2812B"))
    )
    (comp (ref "LED46")
      (value "WS2812B")
      (footprint "eagle-import:WS2812B")
      (libsource (lib "eagle-import") (part "WS2812B"))
    )
    (comp (ref "LED47")
      (value "WS2812B")
      (footprint "eagle-import:WS2812B")
      (libsource (lib "eagle-import") (part "WS2812B"))
    )
    (comp (ref "LED48")
      (value "WS2812B")
      (footprint "eagle-import:WS2812B")
      (libsource (lib "eagle-import") (part "WS2812B"))
    )
    (comp (ref "LED49")
      (value "WS2812B")
      (footprint "eagle-import:WS2812B")
      (libsource (lib "eagle-import") (part "WS2812B"))
    )
    (comp (ref "LED50")
      (value "WS2812B")
      (footprint "eagle-import:WS2812B")
      (libsource (lib "eagle-import") (part "WS2812B"))
    )
    (comp (ref "LED51")
      (value "WS2812B")
      (footprint "eagle-import:WS2812B")
      (libsource (lib "eagle-import") (part "WS2812B"))
    )
    (comp (ref "LED52")
      (value "WS2812B")
      (footprint "eagle-import:WS2812B")
      (libsource (lib "eagle-import") (part "WS2812B"))
    )
    (comp (ref "LED53")
      (value "WS2812B")
      (footprint "eagle-import:WS2812B")
      (libsource (lib "eagle-import") (part "WS2812B"))
    )
    (comp (ref "LED54")
      (value "WS2812B")
      (footprint "eagle-import:WS2812B")
      (libsource (lib "eagle-import") (part "WS2812B"))
    )
    (comp (ref "LED55")
      (value "WS2812B")
      (footprint "eagle-import:WS2812B")
      (libsource (lib "eagle-import") (part "WS2812B"))
    )
    (comp (ref "LED56")
      (value "WS2812B")
      (footprint "eagle-import:WS2812B")
      (libsource (lib "eagle-import") (part "WS2812B"))
    )
    (comp (ref "LED57")
      (value "WS2812B")
      (footprint "eagle-import:WS2812B")
      (libsource (lib "eagle-import") (part "WS2812B"))
    )
    (comp (ref "LED58")
      (value "WS2812B")
      (footprint "eagle-import:WS2812B")
      (libsource (lib "eagle-import") (part "WS2812B"))
    )
    (comp (ref "LED59")
      (value "WS2812B")
      (footprint "eagle-import:WS2812B")
      (libsource (lib "eagle-import") (part "WS2812B"))
    )
    (comp (ref "LED60")
      (value "WS2812B")
      (footprint "eagle-import:WS2812B")
      (libsource (lib "eagle-import") (part "WS2812B"))
    )
    (comp (ref "LED61")
      (value "WS2812B")
      (footprint "eagle-import:WS2812B")
      (libsource (lib "eagle-import") (part "WS2812B"))
    )
    (comp (ref "LED62")
      (value "WS2812B")
      (footprint "eagle-import:WS2812B")
      (libsource (lib "eagle-import") (part "WS2812B"))
    )
    (comp (ref "LED63")
      (value "WS2812B")
      (footprint "eagle-import:WS2812B")
      (libsource (lib "eagle-import") (part "WS2812B"))
    )
    (comp (ref "LED64")
      (value "WS2812B")
      (footprint "eagle-import:WS2812B")
      (libsource (lib "eagle-import") (part "WS2812B"))
    )
    (comp (ref "LED65")
      (value "WS2812B")
      (footprint "eagle-import:WS2812B")
      (libsource (lib "eagle-import") (part "WS2812B"))
    )
    (comp (ref "LED66")
      (value "WS2812B")
      (footprint "eagle-import:WS2812B")
      (libsource (lib "eagle-import") (part "WS2812B"))
    )
    (comp (ref "LED67")
      (value "WS2812B")
      (footprint "eagle-import:WS2812B")
      (libsource (lib "eagle-import") (part "WS2812B"))
    )
    (comp (ref "LED68")
      (value "WS2812B")
      (footprint "eagle-import:WS2812B")
      (libsource (lib "eagle-import") (part "WS2812B"))
    )
    (comp (ref "LED69")
      (value "WS2812B")
      (footprint "eagle-import:WS2812B")
      (libsource (lib "eagle-import") (part "WS2812B"))
    )
    (comp (ref "LED70")
      (value "WS2812B")
      (footprint "eagle-import:WS2812B")
      (libsource (lib "eagle-import") (part "WS2812B"))
    )
    (comp (ref "LED71")
      (value "WS2812B")
      (footprint "eagle-import:WS2812B")
      (libsource (lib "eagle-import") (part "WS2812B"))
    )
    (comp (ref "LED72")
      (value "WS2812B")
      (footprint "eagle-import:WS2812B")
      (libsource (lib "eagle-import") (part "WS2812B"))
    )
    (comp (ref "LED73")
      (value "WS2812B")
      (footprint "eagle-import:WS2812B")
      (libsource (lib "eagle-import") (part "WS2812B"))
    )
    (comp (ref "LED74")
      (value "WS2812B")
      (footprint "eagle-import:WS2812B")
      (libsource (lib "eagle-import") (part "WS2812B"))
    )
    (comp (ref "LED75")
      (value "WS2812B")
      (footprint "eagle-import:WS2812B")
      (libsource (lib "eagle-import") (part "WS2812B"))
    )
    (comp (ref "LED76")
      (value "WS2812B")
      (footprint "eagle-import:WS2812B")
      (libsource (lib "eagle-import") (part "WS2812B"))
    )
    (comp (ref "LED77")
      (value "WS2812B")
      (footprint "eagle-import:WS2812B")
      (libsource (lib "eagle-import") (part "WS2812B"))
    )
    (comp (ref "LED78")
      (value "WS2812B")
      (footprint "eagle-import:WS2812B")
      (libsource (lib "eagle-import") (part "WS2812B"))
    )
    (comp (ref "LED79")
      (value "WS2812B")
      (footprint "eagle-import:WS2812B")
      (libsource (lib "eagle-import") (part "WS2812B"))
    )
    (comp (ref "LED80")
      (value "WS2812B")
      (footprint "eagle-import:WS2812B")
      (libsource (lib "eagle-import") (part "WS2812B"))
    )
    (comp (ref "LED81")
      (value "WS2812B")
      (footprint "eagle-import:WS2812B")
      (libsource (lib "eagle-import") (part "WS2812B"))
    )
    (comp (ref "LED82")
      (value "WS2812B")
      (footprint "eagle-import:WS2812B")
      (libsource (lib "eagle-import") (part "WS2812B"))
    )
    (comp (ref "LED83")
      (value "WS2812B")
      (footprint "eagle-import:WS2812B")
      (libsource (lib "eagle-import") (part "WS2812B"))
    )
    (comp (ref "LED84")
      (value "WS2812B")
      (footprint "eagle-import:WS2812B")
      (libsource (lib "eagle-import") (part "WS2812B"))
    )
    (comp (ref "LED85")
      (value "WS2812B")
      (footprint "eagle-import:WS2812B")
      (libsource (lib "eagle-import") (part "WS2812B"))
    )
    (comp (ref "LED86")
      (value "WS2812B")
      (footprint "eagle-import:WS2812B")
      (libsource (lib "eagle-import") (part "WS2812B"))
    )
    (comp (ref "LED87")
      (value "WS2812B")
      (footprint "eagle-import:WS2812B")
      (libsource (lib "eagle-import") (part "WS2812B"))
    )
    (comp (ref "LED88")
      (value "WS2812B")
      (footprint "eagle-import:WS2812B")
      (libsource (lib "eagle-import") (part "WS2812B"))
    )
    (comp (ref "LED89")
      (value "WS2812B")
      (footprint "eagle-import:WS2812B")
      (libsource (lib "eagle-import") (part "WS2812B"))
    )
    (comp (ref "LED90")
      (value "WS2812B")
      (footprint "eagle-import:WS2812B")
      (libsource (lib "eagle-import") (part "WS2812B"))
    )
    (comp (ref "LED91")
      (value "WS2812B")
      (footprint "eagle-import:WS2812B")
      (libsource (lib "eagle-import") (part "WS2812B"))
    )
    (comp (ref "LED92")
      (value "WS2812B")
      (footprint "eagle-import:WS2812B")
      (libsource (lib "eagle-import") (part "WS2812B"))
    )
    (comp (ref "LED93")
      (value "WS2812B")
      (footprint "eagle-import:WS2812B")
      (libsource (lib "eagle-import") (part "WS2812B"))
    )
    (comp (ref "LED94")
      (value "WS2812B")
      (footprint "eagle-import:WS2812B")
      (libsource (lib "eagle-import") (part "WS2812B"))
    )
    (comp (ref "LED95")
      (value "WS2812B")
      (footprint "eagle-import:WS2812B")
      (libsource (lib "eagle-import") (part "WS2812B"))
    )
    (comp (ref "LED96")
      (value "WS2812B")
      (footprint "eagle-import:WS2812B")
      (libsource (lib "eagle-import") (part "WS2812B"))
    )
    (comp (ref "LED97")
      (value "WS2812B")
      (footprint "eagle-import:WS2812B")
      (libsource (lib "eagle-import") (part "WS2812B"))
    )
    (comp (ref "LED98")
      (value "WS2812B")
      (footprint "eagle-import:WS2812B")
      (libsource (lib "eagle-import") (part "WS2812B"))
    )
    (comp (ref "LED99")
      (value "WS2812B")
      (footprint "eagle-import:WS2812B")
      (libsource (lib "eagle-import") (part "WS2812B"))
    )
    (comp (ref "LED100")
      (value "WS2812B")
      (footprint "eagle-import:WS2812B")
      (libsource (lib "eagle-import") (part "WS2812B"))
    )
    (comp (ref "LED101")
      (value "WS2812B")
      (footprint "eagle-import:WS2812B")
      (libsource (lib "eagle-import") (part "WS2812B"))
    )
    (comp (ref "LED102")
      (value "WS2812B")
      (footprint "eagle-import:WS2812B")
      (libsource (lib "eagle-import") (part "WS2812B"))
    )
    (comp (ref "LED103")
      (value "WS2812B")
      (footprint "eagle-import:WS2812B")
      (libsource (lib "eagle-import") (part "WS2812B"))
    )
    (comp (ref "LED104")
      (value "WS2812B")
      (footprint "eagle-import:WS2812B")
      (libsource (lib "eagle-import") (part "WS2812B"))
    )
    (comp (ref "LED105")
      (value "WS2812B")
      (footprint "eagle-import:WS2812B")
      (libsource (lib "eagle-import") (part "WS2812B"))
    )
    (comp (ref "LED106")
      (value "WS2812B")
      (footprint "eagle-import:WS2812B")
      (libsource (lib "eagle-import") (part "WS2812B"))
    )
    (comp (ref "LED107")
      (value "WS2812B")
      (footprint "eagle-import:WS2812B")
      (libsource (lib "eagle-import") (part "WS2812B"))
    )
    (comp (ref "LED108")
      (value "WS2812B")
      (footprint "eagle-import:WS2812B")
      (libsource (lib "eagle-import") (part "WS2812B"))
    )
    (comp (ref "LED109")
      (value "WS2812B")
      (footprint "eagle-import:WS2812B")
      (libsource (lib "eagle-import") (part "WS2812B"))
    )
    (comp (ref "LED110")
      (value "WS2812B")
      (footprint "eagle-import:WS2812B")
      (libsource (lib "eagle-import") (part "WS2812B"))
    )
    (comp (ref "LED111")
      (value "WS2812B")
      (footprint "eagle-import:WS2812B")
      (libsource (lib "eagle-import") (part "WS2812B"))
    )
    (comp (ref "LED112")
      (value "WS2812B")
      (footprint "eagle-import:WS2812B")
      (libsource (lib "eagle-import") (part "WS2812B"))
    )
    (comp (ref "LED113")
      (value "WS2812B")
      (footprint "eagle-import:WS2812B")
      (libsource (lib "eagle-import") (part "WS2812B"))
    )
    (comp (ref "LED114")
      (value "WS2812B")
      (footprint "eagle-import:WS2812B")
      (libsource (lib "eagle-import") (part "WS2812B"))
    )
    (comp (ref "LED115")
      (value "WS2812B")
      (footprint "eagle-import:WS2812B")
      (libsource (lib "eagle-import") (part "WS2812B"))
    )
    (comp (ref "LED116")
      (value "WS2812B")
      (footprint "eagle-import:WS2812B")
      (libsource (lib "eagle-import") (part "WS2812B"))
    )
    (comp (ref "LED117")
      (value "WS2812B")
      (footprint "eagle-import:WS2812B")
      (libsource (lib "eagle-import") (part "WS2812B"))
    )
    (comp (ref "LED118")
      (value "WS2812B")
      (footprint "eagle-import:WS2812B")
      (libsource (lib "eagle-import") (part "WS2812B"))
    )
    (comp (ref "LED119")
      (value "WS2812B")
      (footprint "eagle-import:WS2812B")
      (libsource (lib "eagle-import") (part "WS2812B"))
    )
    (comp (ref "LED120")
      (value "WS2812B")
      (footprint "eagle-import:WS2812B")
      (libsource (lib "eagle-import") (part "WS2812B"))
    )
    (comp (ref "LED121")
      (value "WS2812B")
      (footprint "eagle-import:WS2812B")
      (libsource (lib "eagle-import") (part "WS2812B"))
    )
    (comp (ref "LED122")
      (value "WS2812B")
      (footprint "eagle-import:WS2812B")
      (libsource (lib "eagle-import") (part "WS2812B"))
    )
    (comp (ref "LED123")
      (value "WS2812B")
      (footprint "eagle-import:WS2812B")
      (libsource (lib "eagle-import") (part "WS2812B"))
    )
    (comp (ref "LED124")
      (value "WS2812B")
      (footprint "eagle-import:WS2812B")
      (libsource (lib "eagle-import") (part "WS2812B"))
    )
    (comp (ref "LED125")
      (value "WS2812B")
      (footprint "eagle-import:WS2812B")
      (libsource (lib "eagle-import") (part "WS2812B"))
    )
    (comp (ref "LED126")
      (value "WS2812B")
      (footprint "eagle-import:WS2812B")
      (libsource (lib "eagle-import") (part "WS2812B"))
    )
    (comp (ref "LED127")
      (value "WS2812B")
      (footprint "eagle-import:WS2812B")
      (libsource (lib "eagle-import") (part "WS2812B"))
    )
    (comp (ref "LED128")
      (value "WS2812B")
      (footprint "eagle-import:WS2812B")
      (libsource (lib "eagle-import") (part "WS2812B"))
    )
    (comp (ref "LED129")
      (value "WS2812B")
      (footprint "eagle-import:WS2812B")
      (libsource (lib "eagle-import") (part "WS2812B"))
    )
    (comp (ref "LED130")
      (value "WS2812B")
      (footprint "eagle-import:WS2812B")
      (libsource (lib "eagle-import") (part "WS2812B"))
    )
    (comp (ref "LED131")
      (value "WS2812B")
      (footprint "eagle-import:WS2812B")
      (libsource (lib "eagle-import") (part "WS2812B"))
    )
    (comp (ref "LED132")
      (value "WS2812B")
      (footprint "eagle-import:WS2812B")
      (libsource (lib "eagle-import") (part "WS2812B"))
    )
    (comp (ref "LED133")
      (value "WS2812B")
      (footprint "eagle-import:WS2812B")
      (libsource (lib "eagle-import") (part "WS2812B"))
    )
    (comp (ref "LED134")
      (value "WS2812B")
      (footprint "eagle-import:WS2812B")
      (libsource (lib "eagle-import") (part "WS2812B"))
    )
    (comp (ref "LED135")
      (value "WS2812B")
      (footprint "eagle-import:WS2812B")
      (libsource (lib "eagle-import") (part "WS2812B"))
    )
    (comp (ref "LED136")
      (value "WS2812B")
      (footprint "eagle-import:WS2812B")
      (libsource (lib "eagle-import") (part "WS2812B"))
    )
    (comp (ref "LED137")
      (value "WS2812B")
      (footprint "eagle-import:WS2812B")
      (libsource (lib "eagle-import") (part "WS2812B"))
    )
    (comp (ref "LED138")
      (value "WS2812B")
      (footprint "eagle-import:WS2812B")
      (libsource (lib "eagle-import") (part "WS2812B"))
    )
    (comp (ref "LED139")
      (value "WS2812B")
      (footprint "eagle-import:WS2812B")
      (libsource (lib "eagle-import") (part "WS2812B"))
    )
    (comp (ref "LED140")
      (value "WS2812B")
      (footprint "eagle-import:WS2812B")
      (libsource (lib "eagle-import") (part "WS2812B"))
    )
    (comp (ref "LED141")
      (value "WS2812B")
      (footprint "eagle-import:WS2812B")
      (libsource (lib "eagle-import") (part "WS2812B"))
    )
    (comp (ref "LED142")
      (value "WS2812B")
      (footprint "eagle-import:WS2812B")
      (libsource (lib "eagle-import") (part "WS2812B"))
    )
    (comp (ref "LED143")
      (value "WS2812B")
      (footprint "eagle-import:WS2812B")
      (libsource (lib "eagle-import") (part "WS2812B"))
    )
    (comp (ref "LED144")
      (value "WS2812B")
      (footprint "eagle-import:WS2812B")
      (libsource (lib "eagle-import") (part "WS2812B"))
    )
    (comp (ref "LED145")
      (value "WS2812B")
      (footprint "eagle-import:WS2812B")
      (libsource (lib "eagle-import") (part "WS2812B"))
    )
    (comp (ref "LED146")
      (value "WS2812B")
      (footprint "eagle-import:WS2812B")
      (libsource (lib "eagle-import") (part "WS2812B"))
    )
    (comp (ref "LED147")
      (value "WS2812B")
      (footprint "eagle-import:WS2812B")
      (libsource (lib "eagle-import") (part "WS2812B"))
    )
    (comp (ref "LED148")
      (value "WS2812B")
      (footprint "eagle-import:WS2812B")
      (libsource (lib "eagle-import") (part "WS2812B"))
    )
    (comp (ref "LED149")
      (value "WS2812B")
      (footprint "eagle-import:WS2812B")
      (libsource (lib "eagle-import") (part "WS2812B"))
    )
    (comp (ref "LED150")
      (value "WS2812B")
      (footprint "eagle-import:WS2812B")
      (libsource (lib "eagle-import") (part "WS2812B"))
    )
    (comp (ref "LED151")
      (value "WS2812B")
      (footprint "eagle-import:WS2812B")
      (libsource (lib "eagle-import") (part "WS2812B"))
    )
    (comp (ref "LED152")
      (value "WS2812B")
      (footprint "eagle-import:WS2812B")
      (libsource (lib "eagle-import") (part "WS2812B"))
    )
    (comp (ref "LED153")
      (value "WS2812B")
      (footprint "eagle-import:WS2812B")
      (libsource (lib "eagle-import") (part "WS2812B"))
    )
    (comp (ref "LED154")
      (value "WS2812B")
      (footprint "eagle-import:WS2812B")
      (libsource (lib "eagle-import") (part "WS2812B"))
    )
    (comp (ref "LED155")
      (value "WS2812B")
      (footprint "eagle-import:WS2812B")
      (libsource (lib "eagle-import") (part "WS2812B"))
    )
    (comp (ref "LED156")
      (value "WS2812B")
      (footprint "eagle-import:WS2812B")
      (libsource (lib "eagle-import") (part "WS2812B"))
    )
    (comp (ref "LED157")
      (value "WS2812B")
      (footprint "eagle-import:WS2812B")
      (libsource (lib "eagle-import") (part "WS2812B"))
    )
    (comp (ref "LED158")
      (value "WS2812B")
      (footprint "eagle-import:WS2812B")
      (libsource (lib "eagle-import") (part "WS2812B"))
    )
    (comp (ref "LED159")
      (value "WS2812B")
      (footprint "eagle-import:WS2812B")
      (libsource (lib "eagle-import") (part "WS2812B"))
    )
    (comp (ref "LED160")
      (value "WS2812B")
      (footprint "eagle-import:WS2812B")
      (libsource (lib "eagle-import") (part "WS2812B"))
    )
    (comp (ref "LED161")
      (value "WS2812B")
      (footprint "eagle-import:WS2812B")
      (libsource (lib "eagle-import") (part "WS2812B"))
    )
    (comp (ref "LED162")
      (value "WS2812B")
      (footprint "eagle-import:WS2812B")
      (libsource (lib "eagle-import") (part "WS2812B"))
    )
    (comp (ref "LED163")
      (value "WS2812B")
      (footprint "eagle-import:WS2812B")
      (libsource (lib "eagle-import") (part "WS2812B"))
    )
    (comp (ref "LED164")
      (value "WS2812B")
      (footprint "eagle-import:WS2812B")
      (libsource (lib "eagle-import") (part "WS2812B"))
    )
    (comp (ref "LED165")
      (value "WS2812B")
      (footprint "eagle-import:WS2812B")
      (libsource (lib "eagle-import") (part "WS2812B"))
    )
    (comp (ref "LED166")
      (value "WS2812B")
      (footprint "eagle-import:WS2812B")
      (libsource (lib "eagle-import") (part "WS2812B"))
    )
    (comp (ref "LED167")
      (value "WS2812B")
      (footprint "eagle-import:WS2812B")
      (libsource (lib "eagle-import") (part "WS2812B"))
    )
    (comp (ref "LED168")
      (value "WS2812B")
      (footprint "eagle-import:WS2812B")
      (libsource (lib "eagle-import") (part "WS2812B"))
    )
    (comp (ref "LED169")
      (value "WS2812B")
      (footprint "eagle-import:WS2812B")
      (libsource (lib "eagle-import") (part "WS2812B"))
    )
    (comp (ref "LED170")
      (value "WS2812B")
      (footprint "eagle-import:WS2812B")
      (libsource (lib "eagle-import") (part "WS2812B"))
    )
    (comp (ref "LED171")
      (value "WS2812B")
      (footprint "eagle-import:WS2812B")
      (libsource (lib "eagle-import") (part "WS2812B"))
    )
    (comp (ref "LED172")
      (value "WS2812B")
      (footprint "eagle-import:WS2812B")
      (libsource (lib "eagle-import") (part "WS2812B"))
    )
    (comp (ref "LED173")
      (value "WS2812B")
      (footprint "eagle-import:WS2812B")
      (libsource (lib "eagle-import") (part "WS2812B"))
    )
    (comp (ref "LED174")
      (value "WS2812B")
      (footprint "eagle-import:WS2812B")
      (libsource (lib "eagle-import") (part "WS2812B"))
    )
    (comp (ref "LED175")
      (value "WS2812B")
      (footprint "eagle-import:WS2812B")
      (libsource (lib "eagle-import") (part "WS2812B"))
    )
    (comp (ref "LED176")
      (value "WS2812B")
      (footprint "eagle-import:WS2812B")
      (libsource (lib "eagle-import") (part "WS2812B"))
    )
    (comp (ref "LED177")
      (value "WS2812B")
      (footprint "eagle-import:WS2812B")
      (libsource (lib "eagle-import") (part "WS2812B"))
    )
    (comp (ref "LED178")
      (value "WS2812B")
      (footprint "eagle-import:WS2812B")
      (libsource (lib "eagle-import") (part "WS2812B"))
    )
    (comp (ref "LED179")
      (value "WS2812B")
      (footprint "eagle-import:WS2812B")
      (libsource (lib "eagle-import") (part "WS2812B"))
    )
    (comp (ref "LED180")
      (value "WS2812B")
      (footprint "eagle-import:WS2812B")
      (libsource (lib "eagle-import") (part "WS2812B"))
    )
    (comp (ref "LED181")
      (value "WS2812B")
      (footprint "eagle-import:WS2812B")
      (libsource (lib "eagle-import") (part "WS2812B"))
    )
    (comp (ref "LED182")
      (value "WS2812B")
      (footprint "eagle-import:WS2812B")
      (libsource (lib "eagle-import") (part "WS2812B"))
    )
    (comp (ref "LED183")
      (value "WS2812B")
      (footprint "eagle-import:WS2812B")
      (libsource (lib "eagle-import") (part "WS2812B"))
    )
    (comp (ref "LED184")
      (value "WS2812B")
      (footprint "eagle-import:WS2812B")
      (libsource (lib "eagle-import") (part "WS2812B"))
    )
    (comp (ref "LED185")
      (value "WS2812B")
      (footprint "eagle-import:WS2812B")
      (libsource (lib "eagle-import") (part "WS2812B"))
    )
    (comp (ref "LED186")
      (value "WS2812B")
      (footprint "eagle-import:WS2812B")
      (libsource (lib "eagle-import") (part "WS2812B"))
    )
    (comp (ref "LED187")
      (value "WS2812B")
      (footprint "eagle-import:WS2812B")
      (libsource (lib "eagle-import") (part "WS2812B"))
    )
    (comp (ref "LED188")
      (value "WS2812B")
      (footprint "eagle-import:WS2812B")
      (libsource (lib "eagle-import") (part "WS2812B"))
    )
    (comp (ref "LED189")
      (value "WS2812B")
      (footprint "eagle-import:WS2812B")
      (libsource (lib "eagle-import") (part "WS2812B"))
    )
    (comp (ref "LED190")
      (value "WS2812B")
      (footprint "eagle-import:WS2812B")
      (libsource (lib "eagle-import") (part "WS2812B"))
    )
    (comp (ref "LED191")
      (value "WS2812B")
      (footprint "eagle-import:WS2812B")
      (libsource (lib "eagle-import") (part "WS2812B"))
    )
    (comp (ref "LED192")
      (value "WS2812B")
      (footprint "eagle-import:WS2812B")
      (libsource (lib "eagle-import") (part "WS2812B"))
    )
    (comp (ref "LOGO7")
      (value "OSHW-LOGOM")
      (footprint "eagle-import:OSHW-LOGO-M")
      (libsource (lib "eagle-import") (part "OSHW-LOGOM"))
    )
    (comp (ref "PAD1")
      (value "SMD2")
      (footprint "eagle-import:SMD1,27-2,54")
      (libsource (lib "eagle-import") (part "SMD2"))
    )
    (comp (ref "PAD2")
      (value "SMD2")
      (footprint "eagle-import:SMD1,27-2,54")
      (libsource (lib "eagle-import") (part "SMD2"))
    )
    (comp (ref "PAD3")
      (value "SMD2")
      (footprint "eagle-import:SMD1,27-2,54")
      (libsource (lib "eagle-import") (part "SMD2"))
    )
    (comp (ref "PAD4")
      (value "SMD2")
      (footprint "eagle-import:SMD1,27-2,54")
      (libsource (lib "eagle-import") (part "SMD2"))
    )
    (comp (ref "PAD5")
      (value "SMD2")
      (footprint "eagle-import:SMD1,27-2,54")
      (libsource (lib "eagle-import") (part "SMD2"))
    )
    (comp (ref "PAD6")
      (value "SMD2")
      (footprint "eagle-import:SMD1,27-2,54")
      (libsource (lib "eagle-import") (part "SMD2"))
    )
    (comp (ref "PAD7")
      (value "SMD2")
      (footprint "eagle-import:SMD1,27-2,54")
      (libsource (lib "eagle-import") (part "SMD2"))
    )
    (comp (ref "PAD8")
      (value "SMD2")
      (footprint "eagle-import:SMD1,27-2,54")
      (libsource (lib "eagle-import") (part "SMD2"))
    )
    (comp (ref "PAD9")
      (value "SMD2")
      (footprint "eagle-import:SMD1,27-2,54")
      (libsource (lib "eagle-import") (part "SMD2"))
    )
    (comp (ref "PAD10")
      (value "SMD2")
      (footprint "eagle-import:SMD1,27-2,54")
      (libsource (lib "eagle-import") (part "SMD2"))
    )
    (comp (ref "PAD11")
      (value "SMD2")
      (footprint "eagle-import:SMD1,27-2,54")
      (libsource (lib "eagle-import") (part "SMD2"))
    )
    (comp (ref "PAD12")
      (value "SMD2")
      (footprint "eagle-import:SMD1,27-2,54")
      (libsource (lib "eagle-import") (part "SMD2"))
    )
    (comp (ref "PAD13")
      (value "SMD2")
      (footprint "eagle-import:SMD1,27-2,54")
      (libsource (lib "eagle-import") (part "SMD2"))
    )
    (comp (ref "PAD14")
      (value "SMD2")
      (footprint "eagle-import:SMD1,27-2,54")
      (libsource (lib "eagle-import") (part "SMD2"))
    )
    (comp (ref "PAD15")
      (value "SMD2")
      (footprint "eagle-import:SMD1,27-2,54")
      (libsource (lib "eagle-import") (part "SMD2"))
    )
    (comp (ref "PAD16")
      (value "SMD2")
      (footprint "eagle-import:SMD1,27-2,54")
      (libsource (lib "eagle-import") (part "SMD2"))
    )
    (comp (ref "PAD17")
      (value "SMD2")
      (footprint "eagle-import:SMD1,27-2,54")
      (libsource (lib "eagle-import") (part "SMD2"))
    )
    (comp (ref "PAD18")
      (value "SMD2")
      (footprint "eagle-import:SMD1,27-2,54")
      (libsource (lib "eagle-import") (part "SMD2"))
    )
    (comp (ref "PAD19")
      (value "SMD2")
      (footprint "eagle-import:SMD1,27-2,54")
      (libsource (lib "eagle-import") (part "SMD2"))
    )
    (comp (ref "PAD20")
      (value "SMD2")
      (footprint "eagle-import:SMD1,27-2,54")
      (libsource (lib "eagle-import") (part "SMD2"))
    )
    (comp (ref "PAD21")
      (value "SMD2")
      (footprint "eagle-import:SMD1,27-2,54")
      (libsource (lib "eagle-import") (part "SMD2"))
    )
    (comp (ref "PAD22")
      (value "SMD2")
      (footprint "eagle-import:SMD1,27-2,54")
      (libsource (lib "eagle-import") (part "SMD2"))
    )
    (comp (ref "PAD23")
      (value "SMD2")
      (footprint "eagle-import:SMD1,27-2,54")
      (libsource (lib "eagle-import") (part "SMD2"))
    )
    (comp (ref "PAD24")
      (value "SMD2")
      (footprint "eagle-import:SMD1,27-2,54")
      (libsource (lib "eagle-import") (part "SMD2"))
    )
    (comp (ref "PAD25")
      (value "SMD2")
      (footprint "eagle-import:SMD1,27-2,54")
      (libsource (lib "eagle-import") (part "SMD2"))
    )
    (comp (ref "PAD26")
      (value "SMD2")
      (footprint "eagle-import:SMD1,27-2,54")
      (libsource (lib "eagle-import") (part "SMD2"))
    )
    (comp (ref "PAD27")
      (value "SMD2")
      (footprint "eagle-import:SMD1,27-2,54")
      (libsource (lib "eagle-import") (part "SMD2"))
    )
    (comp (ref "PAD28")
      (value "SMD2")
      (footprint "eagle-import:SMD1,27-2,54")
      (libsource (lib "eagle-import") (part "SMD2"))
    )
    (comp (ref "TP1")
      (value "TPB1,27")
      (footprint "eagle-import:B1,27")
      (libsource (lib "eagle-import") (part "TPB1,27"))
    )
    (comp (ref "TP2")
      (value "TPB1,27")
      (footprint "eagle-import:B1,27")
      (libsource (lib "eagle-import") (part "TPB1,27"))
    )
    (comp (ref "TP3")
      (value "TPB1,27")
      (footprint "eagle-import:B1,27")
      (libsource (lib "eagle-import") (part "TPB1,27"))
    )
    (comp (ref "TP4")
      (value "TPB1,27")
      (footprint "eagle-import:B1,27")
      (libsource (lib "eagle-import") (part "TPB1,27"))
    )
  )
  (nets
    (net (code "1") (name "+5V") (class "Default")
      (node (ref "C1") (pin "1") (pinfunction "1_1") (pintype "passive"))
      (node (ref "C10") (pin "1") (pinfunction "1_1") (pintype "passive"))
      (node (ref "C100") (pin "1") (pinfunction "1_1") (pintype "passive"))
      (node (ref "C101") (pin "1") (pinfunction "1_1") (pintype "passive"))
      (node (ref "C102") (pin "1") (pinfunction "1_1") (pintype "passive"))
      (node (ref "C103") (pin "1") (pinfunction "1_1") (pintype "passive"))
      (node (ref "C104") (pin "1") (pinfunction "1_1") (pintype "passive"))
      (node (ref "C105") (pin "1") (pinfunction "1_1") (pintype "passive"))
      (node (ref "C106") (pin "1") (pinfunction "1_1") (pintype "passive"))
      (node (ref "C107") (pin "1") (pinfunction "1_1") (pintype "passive"))
      (node (ref "C108") (pin "1") (pinfunction "1_1") (pintype "passive"))
      (node (ref "C109") (pin "1") (pinfunction "1_1") (pintype "passive"))
      (node (ref "C11") (pin "1") (pinfunction "1_1") (pintype "passive"))
      (node (ref "C110") (pin "1") (pinfunction "1_1") (pintype "passive"))
      (node (ref "C111") (pin "1") (pinfunction "1_1") (pintype "passive"))
      (node (ref "C112") (pin "1") (pinfunction "1_1") (pintype "passive"))
      (node (ref "C113") (pin "1") (pinfunction "1_1") (pintype "passive"))
      (node (ref "C114") (pin "1") (pinfunction "1_1") (pintype "passive"))
      (node (ref "C115") (pin "1") (pinfunction "1_1") (pintype "passive"))
      (node (ref "C116") (pin "1") (pinfunction "1_1") (pintype "passive"))
      (node (ref "C117") (pin "1") (pinfunction "1_1") (pintype "passive"))
      (node (ref "C118") (pin "1") (pinfunction "1_1") (pintype "passive"))
      (node (ref "C119") (pin "1") (pinfunction "1_1") (pintype "passive"))
      (node (ref "C12") (pin "1") (pinfunction "1_1") (pintype "passive"))
      (node (ref "C120") (pin "1") (pinfunction "1_1") (pintype "passive"))
      (node (ref "C121") (pin "1") (pinfunction "1_1") (pintype "passive"))
      (node (ref "C122") (pin "1") (pinfunction "1_1") (pintype "passive"))
      (node (ref "C123") (pin "1") (pinfunction "1_1") (pintype "passive"))
      (node (ref "C124") (pin "1") (pinfunction "1_1") (pintype "passive"))
      (node (ref "C125") (pin "1") (pinfunction "1_1") (pintype "passive"))
      (node (ref "C126") (pin "1") (pinfunction "1_1") (pintype "passive"))
      (node (ref "C127") (pin "1") (pinfunction "1_1") (pintype "passive"))
      (node (ref "C128") (pin "1") (pinfunction "1_1") (pintype "passive"))
      (node (ref "C129") (pin "1") (pinfunction "1_1") (pintype "passive"))
      (node (ref "C13") (pin "1") (pinfunction "1_1") (pintype "passive"))
      (node (ref "C130") (pin "1") (pinfunction "1_1") (pintype "passive"))
      (node (ref "C131") (pin "1") (pinfunction "1_1") (pintype "passive"))
      (node (ref "C132") (pin "1") (pinfunction "1_1") (pintype "passive"))
      (node (ref "C133") (pin "1") (pinfunction "1_1") (pintype "passive"))
      (node (ref "C134") (pin "1") (pinfunction "1_1") (pintype "passive"))
      (node (ref "C135") (pin "1") (pinfunction "1_1") (pintype "passive"))
      (node (ref "C136") (pin "1") (pinfunction "1_1") (pintype "passive"))
      (node (ref "C137") (pin "1") (pinfunction "1_1") (pintype "passive"))
      (node (ref "C138") (pin "1") (pinfunction "1_1") (pintype "passive"))
      (node (ref "C139") (pin "1") (pinfunction "1_1") (pintype "passive"))
      (node (ref "C14") (pin "1") (pinfunction "1_1") (pintype "passive"))
      (node (ref "C140") (pin "1") (pinfunction "1_1") (pintype "passive"))
      (node (ref "C141") (pin "1") (pinfunction "1_1") (pintype "passive"))
      (node (ref "C142") (pin "1") (pinfunction "1_1") (pintype "passive"))
      (node (ref "C143") (pin "1") (pinfunction "1_1") (pintype "passive"))
      (node (ref "C144") (pin "1") (pinfunction "1_1") (pintype "passive"))
      (node (ref "C145") (pin "1") (pinfunction "1_1") (pintype "passive"))
      (node (ref "C146") (pin "1") (pinfunction "1_1") (pintype "passive"))
      (node (ref "C147") (pin "1") (pinfunction "1_1") (pintype "passive"))
      (node (ref "C148") (pin "1") (pinfunction "1_1") (pintype "passive"))
      (node (ref "C149") (pin "1") (pinfunction "1_1") (pintype "passive"))
      (node (ref "C15") (pin "1") (pinfunction "1_1") (pintype "passive"))
      (node (ref "C150") (pin "1") (pinfunction "1_1") (pintype "passive"))
      (node (ref "C151") (pin "1") (pinfunction "1_1") (pintype "passive"))
      (node (ref "C152") (pin "1") (pinfunction "1_1") (pintype "passive"))
      (node (ref "C153") (pin "1") (pinfunction "1_1") (pintype "passive"))
      (node (ref "C154") (pin "1") (pinfunction "1_1") (pintype "passive"))
      (node (ref "C155") (pin "1") (pinfunction "1_1") (pintype "passive"))
      (node (ref "C156") (pin "1") (pinfunction "1_1") (pintype "passive"))
      (node (ref "C157") (pin "1") (pinfunction "1_1") (pintype "passive"))
      (node (ref "C158") (pin "1") (pinfunction "1_1") (pintype "passive"))
      (node (ref "C159") (pin "1") (pinfunction "1_1") (pintype "passive"))
      (node (ref "C16") (pin "1") (pinfunction "1_1") (pintype "passive"))
      (node (ref "C160") (pin "1") (pinfunction "1_1") (pintype "passive"))
      (node (ref "C161") (pin "1") (pinfunction "1_1") (pintype "passive"))
      (node (ref "C162") (pin "1") (pinfunction "1_1") (pintype "passive"))
      (node (ref "C163") (pin "1") (pinfunction "1_1") (pintype "passive"))
      (node (ref "C164") (pin "1") (pinfunction "1_1") (pintype "passive"))
      (node (ref "C165") (pin "1") (pinfunction "1_1") (pintype "passive"))
      (node (ref "C166") (pin "1") (pinfunction "1_1") (pintype "passive"))
      (node (ref "C167") (pin "1") (pinfunction "1_1") (pintype "passive"))
      (node (ref "C168") (pin "1") (pinfunction "1_1") (pintype "passive"))
      (node (ref "C169") (pin "1") (pinfunction "1_1") (pintype "passive"))
      (node (ref "C17") (pin "1") (pinfunction "1_1") (pintype "passive"))
      (node (ref "C170") (pin "1") (pinfunction "1_1") (pintype "passive"))
      (node (ref "C171") (pin "1") (pinfunction "1_1") (pintype "passive"))
      (node (ref "C172") (pin "1") (pinfunction "1_1") (pintype "passive"))
      (node (ref "C173") (pin "1") (pinfunction "1_1") (pintype "passive"))
      (node (ref "C174") (pin "1") (pinfunction "1_1") (pintype "passive"))
      (node (ref "C175") (pin "1") (pinfunction "1_1") (pintype "passive"))
      (node (ref "C176") (pin "1") (pinfunction "1_1") (pintype "passive"))
      (node (ref "C177") (pin "1") (pinfunction "1_1") (pintype "passive"))
      (node (ref "C178") (pin "1") (pinfunction "1_1") (pintype "passive"))
      (node (ref "C179") (pin "1") (pinfunction "1_1") (pintype "passive"))
      (node (ref "C18") (pin "1") (pinfunction "1_1") (pintype "passive"))
      (node (ref "C180") (pin "1") (pinfunction "1_1") (pintype "passive"))
      (node (ref "C181") (pin "1") (pinfunction "1_1") (pintype "passive"))
      (node (ref "C182") (pin "1") (pinfunction "1_1") (pintype "passive"))
      (node (ref "C183") (pin "1") (pinfunction "1_1") (pintype "passive"))
      (node (ref "C184") (pin "1") (pinfunction "1_1") (pintype "passive"))
      (node (ref "C185") (pin "1") (pinfunction "1_1") (pintype "passive"))
      (node (ref "C186") (pin "1") (pinfunction "1_1") (pintype "passive"))
      (node (ref "C187") (pin "1") (pinfunction "1_1") (pintype "passive"))
      (node (ref "C188") (pin "1") (pinfunction "1_1") (pintype "passive"))
      (node (ref "C189") (pin "1") (pinfunction "1_1") (pintype "passive"))
      (node (ref "C19") (pin "1") (pinfunction "1_1") (pintype "passive"))
      (node (ref "C190") (pin "1") (pinfunction "1_1") (pintype "passive"))
      (node (ref "C191") (pin "1") (pinfunction "1_1") (pintype "passive"))
      (node (ref "C192") (pin "1") (pinfunction "1_1") (pintype "passive"))
      (node (ref "C2") (pin "1") (pinfunction "1_1") (pintype "passive"))
      (node (ref "C20") (pin "1") (pinfunction "1_1") (pintype "passive"))
      (node (ref "C21") (pin "1") (pinfunction "1_1") (pintype "passive"))
      (node (ref "C22") (pin "1") (pinfunction "1_1") (pintype "passive"))
      (node (ref "C23") (pin "1") (pinfunction "1_1") (pintype "passive"))
      (node (ref "C24") (pin "1") (pinfunction "1_1") (pintype "passive"))
      (node (ref "C25") (pin "1") (pinfunction "1_1") (pintype "passive"))
      (node (ref "C26") (pin "1") (pinfunction "1_1") (pintype "passive"))
      (node (ref "C27") (pin "1") (pinfunction "1_1") (pintype "passive"))
      (node (ref "C28") (pin "1") (pinfunction "1_1") (pintype "passive"))
      (node (ref "C29") (pin "1") (pinfunction "1_1") (pintype "passive"))
      (node (ref "C3") (pin "1") (pinfunction "1_1") (pintype "passive"))
      (node (ref "C30") (pin "1") (pinfunction "1_1") (pintype "passive"))
      (node (ref "C31") (pin "1") (pinfunction "1_1") (pintype "passive"))
      (node (ref "C32") (pin "1") (pinfunction "1_1") (pintype "passive"))
      (node (ref "C33") (pin "1") (pinfunction "1_1") (pintype "passive"))
      (node (ref "C34") (pin "1") (pinfunction "1_1") (pintype "passive"))
      (node (ref "C35") (pin "1") (pinfunction "1_1") (pintype "passive"))
      (node (ref "C36") (pin "1") (pinfunction "1_1") (pintype "passive"))
      (node (ref "C37") (pin "1") (pinfunction "1_1") (pintype "passive"))
      (node (ref "C38") (pin "1") (pinfunction "1_1") (pintype "passive"))
      (node (ref "C39") (pin "1") (pinfunction "1_1") (pintype "passive"))
      (node (ref "C4") (pin "1") (pinfunction "1_1") (pintype "passive"))
      (node (ref "C40") (pin "1") (pinfunction "1_1") (pintype "passive"))
      (node (ref "C41") (pin "1") (pinfunction "1_1") (pintype "passive"))
      (node (ref "C42") (pin "1") (pinfunction "1_1") (pintype "passive"))
      (node (ref "C43") (pin "1") (pinfunction "1_1") (pintype "passive"))
      (node (ref "C44") (pin "1") (pinfunction "1_1") (pintype "passive"))
      (node (ref "C45") (pin "1") (pinfunction "1_1") (pintype "passive"))
      (node (ref "C46") (pin "1") (pinfunction "1_1") (pintype "passive"))
      (node (ref "C47") (pin "1") (pinfunction "1_1") (pintype "passive"))
      (node (ref "C48") (pin "1") (pinfunction "1_1") (pintype "passive"))
      (node (ref "C49") (pin "1") (pinfunction "1_1") (pintype "passive"))
      (node (ref "C5") (pin "1") (pinfunction "1_1") (pintype "passive"))
      (node (ref "C50") (pin "1") (pinfunction "1_1") (pintype "passive"))
      (node (ref "C51") (pin "1") (pinfunction "1_1") (pintype "passive"))
      (node (ref "C52") (pin "1") (pinfunction "1_1") (pintype "passive"))
      (node (ref "C53") (pin "1") (pinfunction "1_1") (pintype "passive"))
      (node (ref "C54") (pin "1") (pinfunction "1_1") (pintype "passive"))
      (node (ref "C55") (pin "1") (pinfunction "1_1") (pintype "passive"))
      (node (ref "C56") (pin "1") (pinfunction "1_1") (pintype "passive"))
      (node (ref "C57") (pin "1") (pinfunction "1_1") (pintype "passive"))
      (node (ref "C58") (pin "1") (pinfunction "1_1") (pintype "passive"))
      (node (ref "C59") (pin "1") (pinfunction "1_1") (pintype "passive"))
      (node (ref "C6") (pin "1") (pinfunction "1_1") (pintype "passive"))
      (node (ref "C60") (pin "1") (pinfunction "1_1") (pintype "passive"))
      (node (ref "C61") (pin "1") (pinfunction "1_1") (pintype "passive"))
      (node (ref "C62") (pin "1") (pinfunction "1_1") (pintype "passive"))
      (node (ref "C63") (pin "1") (pinfunction "1_1") (pintype "passive"))
      (node (ref "C64") (pin "1") (pinfunction "1_1") (pintype "passive"))
      (node (ref "C65") (pin "1") (pinfunction "1_1") (pintype "passive"))
      (node (ref "C66") (pin "1") (pinfunction "1_1") (pintype "passive"))
      (node (ref "C67") (pin "1") (pinfunction "1_1") (pintype "passive"))
      (node (ref "C68") (pin "1") (pinfunction "1_1") (pintype "passive"))
      (node (ref "C69") (pin "1") (pinfunction "1_1") (pintype "passive"))
      (node (ref "C7") (pin "1") (pinfunction "1_1") (pintype "passive"))
      (node (ref "C70") (pin "1") (pinfunction "1_1") (pintype "passive"))
      (node (ref "C71") (pin "1") (pinfunction "1_1") (pintype "passive"))
      (node (ref "C72") (pin "1") (pinfunction "1_1") (pintype "passive"))
      (node (ref "C73") (pin "1") (pinfunction "1_1") (pintype "passive"))
      (node (ref "C74") (pin "1") (pinfunction "1_1") (pintype "passive"))
      (node (ref "C75") (pin "1") (pinfunction "1_1") (pintype "passive"))
      (node (ref "C76") (pin "1") (pinfunction "1_1") (pintype "passive"))
      (node (ref "C77") (pin "1") (pinfunction "1_1") (pintype "passive"))
      (node (ref "C78") (pin "1") (pinfunction "1_1") (pintype "passive"))
      (node (ref "C79") (pin "1") (pinfunction "1_1") (pintype "passive"))
      (node (ref "C8") (pin "1") (pinfunction "1_1") (pintype "passive"))
      (node (ref "C80") (pin "1") (pinfunction "1_1") (pintype "passive"))
      (node (ref "C81") (pin "1") (pinfunction "1_1") (pintype "passive"))
      (node (ref "C82") (pin "1") (pinfunction "1_1") (pintype "passive"))
      (node (ref "C83") (pin "1") (pinfunction "1_1") (pintype "passive"))
      (node (ref "C84") (pin "1") (pinfunction "1_1") (pintype "passive"))
      (node (ref "C85") (pin "1") (pinfunction "1_1") (pintype "passive"))
      (node (ref "C86") (pin "1") (pinfunction "1_1") (pintype "passive"))
      (node (ref "C87") (pin "1") (pinfunction "1_1") (pintype "passive"))
      (node (ref "C88") (pin "1") (pinfunction "1_1") (pintype "passive"))
      (node (ref "C89") (pin "1") (pinfunction "1_1") (pintype "passive"))
      (node (ref "C9") (pin "1") (pinfunction "1_1") (pintype "passive"))
      (node (ref "C90") (pin "1") (pinfunction "1_1") (pintype "passive"))
      (node (ref "C91") (pin "1") (pinfunction "1_1") (pintype "passive"))
      (node (ref "C92") (pin "1") (pinfunction "1_1") (pintype "passive"))
      (node (ref "C93") (pin "1") (pinfunction "1_1") (pintype "passive"))
      (node (ref "C94") (pin "1") (pinfunction "1_1") (pintype "passive"))
      (node (ref "C95") (pin "1") (pinfunction "1_1") (pintype "passive"))
      (node (ref "C96") (pin "1") (pinfunction "1_1") (pintype "passive"))
      (node (ref "C97") (pin "1") (pinfunction "1_1") (pintype "passive"))
      (node (ref "C98") (pin "1") (pinfunction "1_1") (pintype "passive"))
      (node (ref "C99") (pin "1") (pinfunction "1_1") (pintype "passive"))
      (node (ref "LED1") (pin "1") (pinfunction "VDD_1") (pintype "bidirectional"))
      (node (ref "LED10") (pin "1") (pinfunction "VDD_1") (pintype "bidirectional"))
      (node (ref "LED100") (pin "1") (pinfunction "VDD_1") (pintype "bidirectional"))
      (node (ref "LED101") (pin "1") (pinfunction "VDD_1") (pintype "bidirectional"))
      (node (ref "LED102") (pin "1") (pinfunction "VDD_1") (pintype "bidirectional"))
      (node (ref "LED103") (pin "1") (pinfunction "VDD_1") (pintype "bidirectional"))
      (node (ref "LED104") (pin "1") (pinfunction "VDD_1") (pintype "bidirectional"))
      (node (ref "LED105") (pin "1") (pinfunction "VDD_1") (pintype "bidirectional"))
      (node (ref "LED106") (pin "1") (pinfunction "VDD_1") (pintype "bidirectional"))
      (node (ref "LED107") (pin "1") (pinfunction "VDD_1") (pintype "bidirectional"))
      (node (ref "LED108") (pin "1") (pinfunction "VDD_1") (pintype "bidirectional"))
      (node (ref "LED109") (pin "1") (pinfunction "VDD_1") (pintype "bidirectional"))
      (node (ref "LED11") (pin "1") (pinfunction "VDD_1") (pintype "bidirectional"))
      (node (ref "LED110") (pin "1") (pinfunction "VDD_1") (pintype "bidirectional"))
      (node (ref "LED111") (pin "1") (pinfunction "VDD_1") (pintype "bidirectional"))
      (node (ref "LED112") (pin "1") (pinfunction "VDD_1") (pintype "bidirectional"))
      (node (ref "LED113") (pin "1") (pinfunction "VDD_1") (pintype "bidirectional"))
      (node (ref "LED114") (pin "1") (pinfunction "VDD_1") (pintype "bidirectional"))
      (node (ref "LED115") (pin "1") (pinfunction "VDD_1") (pintype "bidirectional"))
      (node (ref "LED116") (pin "1") (pinfunction "VDD_1") (pintype "bidirectional"))
      (node (ref "LED117") (pin "1") (pinfunction "VDD_1") (pintype "bidirectional"))
      (node (ref "LED118") (pin "1") (pinfunction "VDD_1") (pintype "bidirectional"))
      (node (ref "LED119") (pin "1") (pinfunction "VDD_1") (pintype "bidirectional"))
      (node (ref "LED12") (pin "1") (pinfunction "VDD_1") (pintype "bidirectional"))
      (node (ref "LED120") (pin "1") (pinfunction "VDD_1") (pintype "bidirectional"))
      (node (ref "LED121") (pin "1") (pinfunction "VDD_1") (pintype "bidirectional"))
      (node (ref "LED122") (pin "1") (pinfunction "VDD_1") (pintype "bidirectional"))
      (node (ref "LED123") (pin "1") (pinfunction "VDD_1") (pintype "bidirectional"))
      (node (ref "LED124") (pin "1") (pinfunction "VDD_1") (pintype "bidirectional"))
      (node (ref "LED125") (pin "1") (pinfunction "VDD_1") (pintype "bidirectional"))
      (node (ref "LED126") (pin "1") (pinfunction "VDD_1") (pintype "bidirectional"))
      (node (ref "LED127") (pin "1") (pinfunction "VDD_1") (pintype "bidirectional"))
      (node (ref "LED128") (pin "1") (pinfunction "VDD_1") (pintype "bidirectional"))
      (node (ref "LED129") (pin "1") (pinfunction "VDD_1") (pintype "bidirectional"))
      (node (ref "LED13") (pin "1") (pinfunction "VDD_1") (pintype "bidirectional"))
      (node (ref "LED130") (pin "1") (pinfunction "VDD_1") (pintype "bidirectional"))
      (node (ref "LED131") (pin "1") (pinfunction "VDD_1") (pintype "bidirectional"))
      (node (ref "LED132") (pin "1") (pinfunction "VDD_1") (pintype "bidirectional"))
      (node (ref "LED133") (pin "1") (pinfunction "VDD_1") (pintype "bidirectional"))
      (node (ref "LED134") (pin "1") (pinfunction "VDD_1") (pintype "bidirectional"))
      (node (ref "LED135") (pin "1") (pinfunction "VDD_1") (pintype "bidirectional"))
      (node (ref "LED136") (pin "1") (pinfunction "VDD_1") (pintype "bidirectional"))
      (node (ref "LED137") (pin "1") (pinfunction "VDD_1") (pintype "bidirectional"))
      (node (ref "LED138") (pin "1") (pinfunction "VDD_1") (pintype "bidirectional"))
      (node (ref "LED139") (pin "1") (pinfunction "VDD_1") (pintype "bidirectional"))
      (node (ref "LED14") (pin "1") (pinfunction "VDD_1") (pintype "bidirectional"))
      (node (ref "LED140") (pin "1") (pinfunction "VDD_1") (pintype "bidirectional"))
      (node (ref "LED141") (pin "1") (pinfunction "VDD_1") (pintype "bidirectional"))
      (node (ref "LED142") (pin "1") (pinfunction "VDD_1") (pintype "bidirectional"))
      (node (ref "LED143") (pin "1") (pinfunction "VDD_1") (pintype "bidirectional"))
      (node (ref "LED144") (pin "1") (pinfunction "VDD_1") (pintype "bidirectional"))
      (node (ref "LED145") (pin "1") (pinfunction "VDD_1") (pintype "bidirectional"))
      (node (ref "LED146") (pin "1") (pinfunction "VDD_1") (pintype "bidirectional"))
      (node (ref "LED147") (pin "1") (pinfunction "VDD_1") (pintype "bidirectional"))
      (node (ref "LED148") (pin "1") (pinfunction "VDD_1") (pintype "bidirectional"))
      (node (ref "LED149") (pin "1") (pinfunction "VDD_1") (pintype "bidirectional"))
      (node (ref "LED15") (pin "1") (pinfunction "VDD_1") (pintype "bidirectional"))
      (node (ref "LED150") (pin "1") (pinfunction "VDD_1") (pintype "bidirectional"))
      (node (ref "LED151") (pin "1") (pinfunction "VDD_1") (pintype "bidirectional"))
      (node (ref "LED152") (pin "1") (pinfunction "VDD_1") (pintype "bidirectional"))
      (node (ref "LED153") (pin "1") (pinfunction "VDD_1") (pintype "bidirectional"))
      (node (ref "LED154") (pin "1") (pinfunction "VDD_1") (pintype "bidirectional"))
      (node (ref "LED155") (pin "1") (pinfunction "VDD_1") (pintype "bidirectional"))
      (node (ref "LED156") (pin "1") (pinfunction "VDD_1") (pintype "bidirectional"))
      (node (ref "LED157") (pin "1") (pinfunction "VDD_1") (pintype "bidirectional"))
      (node (ref "LED158") (pin "1") (pinfunction "VDD_1") (pintype "bidirectional"))
      (node (ref "LED159") (pin "1") (pinfunction "VDD_1") (pintype "bidirectional"))
      (node (ref "LED16") (pin "1") (pinfunction "VDD_1") (pintype "bidirectional"))
      (node (ref "LED160") (pin "1") (pinfunction "VDD_1") (pintype "bidirectional"))
      (node (ref "LED161") (pin "1") (pinfunction "VDD_1") (pintype "bidirectional"))
      (node (ref "LED162") (pin "1") (pinfunction "VDD_1") (pintype "bidirectional"))
      (node (ref "LED163") (pin "1") (pinfunction "VDD_1") (pintype "bidirectional"))
      (node (ref "LED164") (pin "1") (pinfunction "VDD_1") (pintype "bidirectional"))
      (node (ref "LED165") (pin "1") (pinfunction "VDD_1") (pintype "bidirectional"))
      (node (ref "LED166") (pin "1") (pinfunction "VDD_1") (pintype "bidirectional"))
      (node (ref "LED167") (pin "1") (pinfunction "VDD_1") (pintype "bidirectional"))
      (node (ref "LED168") (pin "1") (pinfunction "VDD_1") (pintype "bidirectional"))
      (node (ref "LED169") (pin "1") (pinfunction "VDD_1") (pintype "bidirectional"))
      (node (ref "LED17") (pin "1") (pinfunction "VDD_1") (pintype "bidirectional"))
      (node (ref "LED170") (pin "1") (pinfunction "VDD_1") (pintype "bidirectional"))
      (node (ref "LED171") (pin "1") (pinfunction "VDD_1") (pintype "bidirectional"))
      (node (ref "LED172") (pin "1") (pinfunction "VDD_1") (pintype "bidirectional"))
      (node (ref "LED173") (pin "1") (pinfunction "VDD_1") (pintype "bidirectional"))
      (node (ref "LED174") (pin "1") (pinfunction "VDD_1") (pintype "bidirectional"))
      (node (ref "LED175") (pin "1") (pinfunction "VDD_1") (pintype "bidirectional"))
      (node (ref "LED176") (pin "1") (pinfunction "VDD_1") (pintype "bidirectional"))
      (node (ref "LED177") (pin "1") (pinfunction "VDD_1") (pintype "bidirectional"))
      (node (ref "LED178") (pin "1") (pinfunction "VDD_1") (pintype "bidirectional"))
      (node (ref "LED179") (pin "1") (pinfunction "VDD_1") (pintype "bidirectional"))
      (node (ref "LED18") (pin "1") (pinfunction "VDD_1") (pintype "bidirectional"))
      (node (ref "LED180") (pin "1") (pinfunction "VDD_1") (pintype "bidirectional"))
      (node (ref "LED181") (pin "1") (pinfunction "VDD_1") (pintype "bidirectional"))
      (node (ref "LED182") (pin "1") (pinfunction "VDD_1") (pintype "bidirectional"))
      (node (ref "LED183") (pin "1") (pinfunction "VDD_1") (pintype "bidirectional"))
      (node (ref "LED184") (pin "1") (pinfunction "VDD_1") (pintype "bidirectional"))
      (node (ref "LED185") (pin "1") (pinfunction "VDD_1") (pintype "bidirectional"))
      (node (ref "LED186") (pin "1") (pinfunction "VDD_1") (pintype "bidirectional"))
      (node (ref "LED187") (pin "1") (pinfunction "VDD_1") (pintype "bidirectional"))
      (node (ref "LED188") (pin "1") (pinfunction "VDD_1") (pintype "bidirectional"))
      (node (ref "LED189") (pin "1") (pinfunction "VDD_1") (pintype "bidirectional"))
      (node (ref "LED19") (pin "1") (pinfunction "VDD_1") (pintype "bidirectional"))
      (node (ref "LED190") (pin "1") (pinfunction "VDD_1") (pintype "bidirectional"))
      (node (ref "LED191") (pin "1") (pinfunction "VDD_1") (pintype "bidirectional"))
      (node (ref "LED192") (pin "1") (pinfunction "VDD_1") (pintype "bidirectional"))
      (node (ref "LED2") (pin "1") (pinfunction "VDD_1") (pintype "bidirectional"))
      (node (ref "LED20") (pin "1") (pinfunction "VDD_1") (pintype "bidirectional"))
      (node (ref "LED21") (pin "1") (pinfunction "VDD_1") (pintype "bidirectional"))
      (node (ref "LED22") (pin "1") (pinfunction "VDD_1") (pintype "bidirectional"))
      (node (ref "LED23") (pin "1") (pinfunction "VDD_1") (pintype "bidirectional"))
      (node (ref "LED24") (pin "1") (pinfunction "VDD_1") (pintype "bidirectional"))
      (node (ref "LED25") (pin "1") (pinfunction "VDD_1") (pintype "bidirectional"))
      (node (ref "LED26") (pin "1") (pinfunction "VDD_1") (pintype "bidirectional"))
      (node (ref "LED27") (pin "1") (pinfunction "VDD_1") (pintype "bidirectional"))
      (node (ref "LED28") (pin "1") (pinfunction "VDD_1") (pintype "bidirectional"))
      (node (ref "LED29") (pin "1") (pinfunction "VDD_1") (pintype "bidirectional"))
      (node (ref "LED3") (pin "1") (pinfunction "VDD_1") (pintype "bidirectional"))
      (node (ref "LED30") (pin "1") (pinfunction "VDD_1") (pintype "bidirectional"))
      (node (ref "LED31") (pin "1") (pinfunction "VDD_1") (pintype "bidirectional"))
      (node (ref "LED32") (pin "1") (pinfunction "VDD_1") (pintype "bidirectional"))
      (node (ref "LED33") (pin "1") (pinfunction "VDD_1") (pintype "bidirectional"))
      (node (ref "LED34") (pin "1") (pinfunction "VDD_1") (pintype "bidirectional"))
      (node (ref "LED35") (pin "1") (pinfunction "VDD_1") (pintype "bidirectional"))
      (node (ref "LED36") (pin "1") (pinfunction "VDD_1") (pintype "bidirectional"))
      (node (ref "LED37") (pin "1") (pinfunction "VDD_1") (pintype "bidirectional"))
      (node (ref "LED38") (pin "1") (pinfunction "VDD_1") (pintype "bidirectional"))
      (node (ref "LED39") (pin "1") (pinfunction "VDD_1") (pintype "bidirectional"))
      (node (ref "LED4") (pin "1") (pinfunction "VDD_1") (pintype "bidirectional"))
      (node (ref "LED40") (pin "1") (pinfunction "VDD_1") (pintype "bidirectional"))
      (node (ref "LED41") (pin "1") (pinfunction "VDD_1") (pintype "bidirectional"))
      (node (ref "LED42") (pin "1") (pinfunction "VDD_1") (pintype "bidirectional"))
      (node (ref "LED43") (pin "1") (pinfunction "VDD_1") (pintype "bidirectional"))
      (node (ref "LED44") (pin "1") (pinfunction "VDD_1") (pintype "bidirectional"))
      (node (ref "LED45") (pin "1") (pinfunction "VDD_1") (pintype "bidirectional"))
      (node (ref "LED46") (pin "1") (pinfunction "VDD_1") (pintype "bidirectional"))
      (node (ref "LED47") (pin "1") (pinfunction "VDD_1") (pintype "bidirectional"))
      (node (ref "LED48") (pin "1") (pinfunction "VDD_1") (pintype "bidirectional"))
      (node (ref "LED49") (pin "1") (pinfunction "VDD_1") (pintype "bidirectional"))
      (node (ref "LED5") (pin "1") (pinfunction "VDD_1") (pintype "bidirectional"))
      (node (ref "LED50") (pin "1") (pinfunction "VDD_1") (pintype "bidirectional"))
      (node (ref "LED51") (pin "1") (pinfunction "VDD_1") (pintype "bidirectional"))
      (node (ref "LED52") (pin "1") (pinfunction "VDD_1") (pintype "bidirectional"))
      (node (ref "LED53") (pin "1") (pinfunction "VDD_1") (pintype "bidirectional"))
      (node (ref "LED54") (pin "1") (pinfunction "VDD_1") (pintype "bidirectional"))
      (node (ref "LED55") (pin "1") (pinfunction "VDD_1") (pintype "bidirectional"))
      (node (ref "LED56") (pin "1") (pinfunction "VDD_1") (pintype "bidirectional"))
      (node (ref "LED57") (pin "1") (pinfunction "VDD_1") (pintype "bidirectional"))
      (node (ref "LED58") (pin "1") (pinfunction "VDD_1") (pintype "bidirectional"))
      (node (ref "LED59") (pin "1") (pinfunction "VDD_1") (pintype "bidirectional"))
      (node (ref "LED6") (pin "1") (pinfunction "VDD_1") (pintype "bidirectional"))
      (node (ref "LED60") (pin "1") (pinfunction "VDD_1") (pintype "bidirectional"))
      (node (ref "LED61") (pin "1") (pinfunction "VDD_1") (pintype "bidirectional"))
      (node (ref "LED62") (pin "1") (pinfunction "VDD_1") (pintype "bidirectional"))
      (node (ref "LED63") (pin "1") (pinfunction "VDD_1") (pintype "bidirectional"))
      (node (ref "LED64") (pin "1") (pinfunction "VDD_1") (pintype "bidirectional"))
      (node (ref "LED65") (pin "1") (pinfunction "VDD_1") (pintype "bidirectional"))
      (node (ref "LED66") (pin "1") (pinfunction "VDD_1") (pintype "bidirectional"))
      (node (ref "LED67") (pin "1") (pinfunction "VDD_1") (pintype "bidirectional"))
      (node (ref "LED68") (pin "1") (pinfunction "VDD_1") (pintype "bidirectional"))
      (node (ref "LED69") (pin "1") (pinfunction "VDD_1") (pintype "bidirectional"))
      (node (ref "LED7") (pin "1") (pinfunction "VDD_1") (pintype "bidirectional"))
      (node (ref "LED70") (pin "1") (pinfunction "VDD_1") (pintype "bidirectional"))
      (node (ref "LED71") (pin "1") (pinfunction "VDD_1") (pintype "bidirectional"))
      (node (ref "LED72") (pin "1") (pinfunction "VDD_1") (pintype "bidirectional"))
      (node (ref "LED73") (pin "1") (pinfunction "VDD_1") (pintype "bidirectional"))
      (node (ref "LED74") (pin "1") (pinfunction "VDD_1") (pintype "bidirectional"))
      (node (ref "LED75") (pin "1") (pinfunction "VDD_1") (pintype "bidirectional"))
      (node (ref "LED76") (pin "1") (pinfunction "VDD_1") (pintype "bidirectional"))
      (node (ref "LED77") (pin "1") (pinfunction "VDD_1") (pintype "bidirectional"))
      (node (ref "LED78") (pin "1") (pinfunction "VDD_1") (pintype "bidirectional"))
      (node (ref "LED79") (pin "1") (pinfunction "VDD_1") (pintype "bidirectional"))
      (node (ref "LED8") (pin "1") (pinfunction "VDD_1") (pintype "bidirectional"))
      (node (ref "LED80") (pin "1") (pinfunction "VDD_1") (pintype "bidirectional"))
      (node (ref "LED81") (pin "1") (pinfunction "VDD_1") (pintype "bidirectional"))
      (node (ref "LED82") (pin "1") (pinfunction "VDD_1") (pintype "bidirectional"))
      (node (ref "LED83") (pin "1") (pinfunction "VDD_1") (pintype "bidirectional"))
      (node (ref "LED84") (pin "1") (pinfunction "VDD_1") (pintype "bidirectional"))
      (node (ref "LED85") (pin "1") (pinfunction "VDD_1") (pintype "bidirectional"))
      (node (ref "LED86") (pin "1") (pinfunction "VDD_1") (pintype "bidirectional"))
      (node (ref "LED87") (pin "1") (pinfunction "VDD_1") (pintype "bidirectional"))
      (node (ref "LED88") (pin "1") (pinfunction "VDD_1") (pintype "bidirectional"))
      (node (ref "LED89") (pin "1") (pinfunction "VDD_1") (pintype "bidirectional"))
      (node (ref "LED9") (pin "1") (pinfunction "VDD_1") (pintype "bidirectional"))
      (node (ref "LED90") (pin "1") (pinfunction "VDD_1") (pintype "bidirectional"))
      (node (ref "LED91") (pin "1") (pinfunction "VDD_1") (pintype "bidirectional"))
      (node (ref "LED92") (pin "1") (pinfunction "VDD_1") (pintype "bidirectional"))
      (node (ref "LED93") (pin "1") (pinfunction "VDD_1") (pintype "bidirectional"))
      (node (ref "LED94") (pin "1") (pinfunction "VDD_1") (pintype "bidirectional"))
      (node (ref "LED95") (pin "1") (pinfunction "VDD_1") (pintype "bidirectional"))
      (node (ref "LED96") (pin "1") (pinfunction "VDD_1") (pintype "bidirectional"))
      (node (ref "LED97") (pin "1") (pinfunction "VDD_1") (pintype "bidirectional"))
      (node (ref "LED98") (pin "1") (pinfunction "VDD_1") (pintype "bidirectional"))
      (node (ref "LED99") (pin "1") (pinfunction "VDD_1") (pintype "bidirectional"))
      (node (ref "PAD10") (pin "1") (pinfunction "P_1") (pintype "passive"))
      (node (ref "PAD14") (pin "1") (pinfunction "P_1") (pintype "passive"))
      (node (ref "PAD18") (pin "1") (pinfunction "P_1") (pintype "passive"))
      (node (ref "PAD2") (pin "1") (pinfunction "P_1") (pintype "passive"))
      (node (ref "PAD22") (pin "1") (pinfunction "P_1") (pintype "passive"))
      (node (ref "PAD26") (pin "1") (pinfunction "P_1") (pintype "passive"))
      (node (ref "PAD6") (pin "1") (pinfunction "P_1") (pintype "passive"))
    )
    (net (code "2") (name "GND") (class "Default")
      (node (ref "C1") (pin "2") (pinfunction "2_2") (pintype "passive"))
      (node (ref "C10") (pin "2") (pinfunction "2_2") (pintype "passive"))
      (node (ref "C100") (pin "2") (pinfunction "2_2") (pintype "passive"))
      (node (ref "C101") (pin "2") (pinfunction "2_2") (pintype "passive"))
      (node (ref "C102") (pin "2") (pinfunction "2_2") (pintype "passive"))
      (node (ref "C103") (pin "2") (pinfunction "2_2") (pintype "passive"))
      (node (ref "C104") (pin "2") (pinfunction "2_2") (pintype "passive"))
      (node (ref "C105") (pin "2") (pinfunction "2_2") (pintype "passive"))
      (node (ref "C106") (pin "2") (pinfunction "2_2") (pintype "passive"))
      (node (ref "C107") (pin "2") (pinfunction "2_2") (pintype "passive"))
      (node (ref "C108") (pin "2") (pinfunction "2_2") (pintype "passive"))
      (node (ref "C109") (pin "2") (pinfunction "2_2") (pintype "passive"))
      (node (ref "C11") (pin "2") (pinfunction "2_2") (pintype "passive"))
      (node (ref "C110") (pin "2") (pinfunction "2_2") (pintype "passive"))
      (node (ref "C111") (pin "2") (pinfunction "2_2") (pintype "passive"))
      (node (ref "C112") (pin "2") (pinfunction "2_2") (pintype "passive"))
      (node (ref "C113") (pin "2") (pinfunction "2_2") (pintype "passive"))
      (node (ref "C114") (pin "2") (pinfunction "2_2") (pintype "passive"))
      (node (ref "C115") (pin "2") (pinfunction "2_2") (pintype "passive"))
      (node (ref "C116") (pin "2") (pinfunction "2_2") (pintype "passive"))
      (node (ref "C117") (pin "2") (pinfunction "2_2") (pintype "passive"))
      (node (ref "C118") (pin "2") (pinfunction "2_2") (pintype "passive"))
      (node (ref "C119") (pin "2") (pinfunction "2_2") (pintype "passive"))
      (node (ref "C12") (pin "2") (pinfunction "2_2") (pintype "passive"))
      (node (ref "C120") (pin "2") (pinfunction "2_2") (pintype "passive"))
      (node (ref "C121") (pin "2") (pinfunction "2_2") (pintype "passive"))
      (node (ref "C122") (pin "2") (pinfunction "2_2") (pintype "passive"))
      (node (ref "C123") (pin "2") (pinfunction "2_2") (pintype "passive"))
      (node (ref "C124") (pin "2") (pinfunction "2_2") (pintype "passive"))
      (node (ref "C125") (pin "2") (pinfunction "2_2") (pintype "passive"))
      (node (ref "C126") (pin "2") (pinfunction "2_2") (pintype "passive"))
      (node (ref "C127") (pin "2") (pinfunction "2_2") (pintype "passive"))
      (node (ref "C128") (pin "2") (pinfunction "2_2") (pintype "passive"))
      (node (ref "C129") (pin "2") (pinfunction "2_2") (pintype "passive"))
      (node (ref "C13") (pin "2") (pinfunction "2_2") (pintype "passive"))
      (node (ref "C130") (pin "2") (pinfunction "2_2") (pintype "passive"))
      (node (ref "C131") (pin "2") (pinfunction "2_2") (pintype "passive"))
      (node (ref "C132") (pin "2") (pinfunction "2_2") (pintype "passive"))
      (node (ref "C133") (pin "2") (pinfunction "2_2") (pintype "passive"))
      (node (ref "C134") (pin "2") (pinfunction "2_2") (pintype "passive"))
      (node (ref "C135") (pin "2") (pinfunction "2_2") (pintype "passive"))
      (node (ref "C136") (pin "2") (pinfunction "2_2") (pintype "passive"))
      (node (ref "C137") (pin "2") (pinfunction "2_2") (pintype "passive"))
      (node (ref "C138") (pin "2") (pinfunction "2_2") (pintype "passive"))
      (node (ref "C139") (pin "2") (pinfunction "2_2") (pintype "passive"))
      (node (ref "C14") (pin "2") (pinfunction "2_2") (pintype "passive"))
      (node (ref "C140") (pin "2") (pinfunction "2_2") (pintype "passive"))
      (node (ref "C141") (pin "2") (pinfunction "2_2") (pintype "passive"))
      (node (ref "C142") (pin "2") (pinfunction "2_2") (pintype "passive"))
      (node (ref "C143") (pin "2") (pinfunction "2_2") (pintype "passive"))
      (node (ref "C144") (pin "2") (pinfunction "2_2") (pintype "passive"))
      (node (ref "C145") (pin "2") (pinfunction "2_2") (pintype "passive"))
      (node (ref "C146") (pin "2") (pinfunction "2_2") (pintype "passive"))
      (node (ref "C147") (pin "2") (pinfunction "2_2") (pintype "passive"))
      (node (ref "C148") (pin "2") (pinfunction "2_2") (pintype "passive"))
      (node (ref "C149") (pin "2") (pinfunction "2_2") (pintype "passive"))
      (node (ref "C15") (pin "2") (pinfunction "2_2") (pintype "passive"))
      (node (ref "C150") (pin "2") (pinfunction "2_2") (pintype "passive"))
      (node (ref "C151") (pin "2") (pinfunction "2_2") (pintype "passive"))
      (node (ref "C152") (pin "2") (pinfunction "2_2") (pintype "passive"))
      (node (ref "C153") (pin "2") (pinfunction "2_2") (pintype "passive"))
      (node (ref "C154") (pin "2") (pinfunction "2_2") (pintype "passive"))
      (node (ref "C155") (pin "2") (pinfunction "2_2") (pintype "passive"))
      (node (ref "C156") (pin "2") (pinfunction "2_2") (pintype "passive"))
      (node (ref "C157") (pin "2") (pinfunction "2_2") (pintype "passive"))
      (node (ref "C158") (pin "2") (pinfunction "2_2") (pintype "passive"))
      (node (ref "C159") (pin "2") (pinfunction "2_2") (pintype "passive"))
      (node (ref "C16") (pin "2") (pinfunction "2_2") (pintype "passive"))
      (node (ref "C160") (pin "2") (pinfunction "2_2") (pintype "passive"))
      (node (ref "C161") (pin "2") (pinfunction "2_2") (pintype "passive"))
      (node (ref "C162") (pin "2") (pinfunction "2_2") (pintype "passive"))
      (node (ref "C163") (pin "2") (pinfunction "2_2") (pintype "passive"))
      (node (ref "C164") (pin "2") (pinfunction "2_2") (pintype "passive"))
      (node (ref "C165") (pin "2") (pinfunction "2_2") (pintype "passive"))
      (node (ref "C166") (pin "2") (pinfunction "2_2") (pintype "passive"))
      (node (ref "C167") (pin "2") (pinfunction "2_2") (pintype "passive"))
      (node (ref "C168") (pin "2") (pinfunction "2_2") (pintype "passive"))
      (node (ref "C169") (pin "2") (pinfunction "2_2") (pintype "passive"))
      (node (ref "C17") (pin "2") (pinfunction "2_2") (pintype "passive"))
      (node (ref "C170") (pin "2") (pinfunction "2_2") (pintype "passive"))
      (node (ref "C171") (pin "2") (pinfunction "2_2") (pintype "passive"))
      (node (ref "C172") (pin "2") (pinfunction "2_2") (pintype "passive"))
      (node (ref "C173") (pin "2") (pinfunction "2_2") (pintype "passive"))
      (node (ref "C174") (pin "2") (pinfunction "2_2") (pintype "passive"))
      (node (ref "C175") (pin "2") (pinfunction "2_2") (pintype "passive"))
      (node (ref "C176") (pin "2") (pinfunction "2_2") (pintype "passive"))
      (node (ref "C177") (pin "2") (pinfunction "2_2") (pintype "passive"))
      (node (ref "C178") (pin "2") (pinfunction "2_2") (pintype "passive"))
      (node (ref "C179") (pin "2") (pinfunction "2_2") (pintype "passive"))
      (node (ref "C18") (pin "2") (pinfunction "2_2") (pintype "passive"))
      (node (ref "C180") (pin "2") (pinfunction "2_2") (pintype "passive"))
      (node (ref "C181") (pin "2") (pinfunction "2_2") (pintype "passive"))
      (node (ref "C182") (pin "2") (pinfunction "2_2") (pintype "passive"))
      (node (ref "C183") (pin "2") (pinfunction "2_2") (pintype "passive"))
      (node (ref "C184") (pin "2") (pinfunction "2_2") (pintype "passive"))
      (node (ref "C185") (pin "2") (pinfunction "2_2") (pintype "passive"))
      (node (ref "C186") (pin "2") (pinfunction "2_2") (pintype "passive"))
      (node (ref "C187") (pin "2") (pinfunction "2_2") (pintype "passive"))
      (node (ref "C188") (pin "2") (pinfunction "2_2") (pintype "passive"))
      (node (ref "C189") (pin "2") (pinfunction "2_2") (pintype "passive"))
      (node (ref "C19") (pin "2") (pinfunction "2_2") (pintype "passive"))
      (node (ref "C190") (pin "2") (pinfunction "2_2") (pintype "passive"))
      (node (ref "C191") (pin "2") (pinfunction "2_2") (pintype "passive"))
      (node (ref "C192") (pin "2") (pinfunction "2_2") (pintype "passive"))
      (node (ref "C2") (pin "2") (pinfunction "2_2") (pintype "passive"))
      (node (ref "C20") (pin "2") (pinfunction "2_2") (pintype "passive"))
      (node (ref "C21") (pin "2") (pinfunction "2_2") (pintype "passive"))
      (node (ref "C22") (pin "2") (pinfunction "2_2") (pintype "passive"))
      (node (ref "C23") (pin "2") (pinfunction "2_2") (pintype "passive"))
      (node (ref "C24") (pin "2") (pinfunction "2_2") (pintype "passive"))
      (node (ref "C25") (pin "2") (pinfunction "2_2") (pintype "passive"))
      (node (ref "C26") (pin "2") (pinfunction "2_2") (pintype "passive"))
      (node (ref "C27") (pin "2") (pinfunction "2_2") (pintype "passive"))
      (node (ref "C28") (pin "2") (pinfunction "2_2") (pintype "passive"))
      (node (ref "C29") (pin "2") (pinfunction "2_2") (pintype "passive"))
      (node (ref "C3") (pin "2") (pinfunction "2_2") (pintype "passive"))
      (node (ref "C30") (pin "2") (pinfunction "2_2") (pintype "passive"))
      (node (ref "C31") (pin "2") (pinfunction "2_2") (pintype "passive"))
      (node (ref "C32") (pin "2") (pinfunction "2_2") (pintype "passive"))
      (node (ref "C33") (pin "2") (pinfunction "2_2") (pintype "passive"))
      (node (ref "C34") (pin "2") (pinfunction "2_2") (pintype "passive"))
      (node (ref "C35") (pin "2") (pinfunction "2_2") (pintype "passive"))
      (node (ref "C36") (pin "2") (pinfunction "2_2") (pintype "passive"))
      (node (ref "C37") (pin "2") (pinfunction "2_2") (pintype "passive"))
      (node (ref "C38") (pin "2") (pinfunction "2_2") (pintype "passive"))
      (node (ref "C39") (pin "2") (pinfunction "2_2") (pintype "passive"))
      (node (ref "C4") (pin "2") (pinfunction "2_2") (pintype "passive"))
      (node (ref "C40") (pin "2") (pinfunction "2_2") (pintype "passive"))
      (node (ref "C41") (pin "2") (pinfunction "2_2") (pintype "passive"))
      (node (ref "C42") (pin "2") (pinfunction "2_2") (pintype "passive"))
      (node (ref "C43") (pin "2") (pinfunction "2_2") (pintype "passive"))
      (node (ref "C44") (pin "2") (pinfunction "2_2") (pintype "passive"))
      (node (ref "C45") (pin "2") (pinfunction "2_2") (pintype "passive"))
      (node (ref "C46") (pin "2") (pinfunction "2_2") (pintype "passive"))
      (node (ref "C47") (pin "2") (pinfunction "2_2") (pintype "passive"))
      (node (ref "C48") (pin "2") (pinfunction "2_2") (pintype "passive"))
      (node (ref "C49") (pin "2") (pinfunction "2_2") (pintype "passive"))
      (node (ref "C5") (pin "2") (pinfunction "2_2") (pintype "passive"))
      (node (ref "C50") (pin "2") (pinfunction "2_2") (pintype "passive"))
      (node (ref "C51") (pin "2") (pinfunction "2_2") (pintype "passive"))
      (node (ref "C52") (pin "2") (pinfunction "2_2") (pintype "passive"))
      (node (ref "C53") (pin "2") (pinfunction "2_2") (pintype "passive"))
      (node (ref "C54") (pin "2") (pinfunction "2_2") (pintype "passive"))
      (node (ref "C55") (pin "2") (pinfunction "2_2") (pintype "passive"))
      (node (ref "C56") (pin "2") (pinfunction "2_2") (pintype "passive"))
      (node (ref "C57") (pin "2") (pinfunction "2_2") (pintype "passive"))
      (node (ref "C58") (pin "2") (pinfunction "2_2") (pintype "passive"))
      (node (ref "C59") (pin "2") (pinfunction "2_2") (pintype "passive"))
      (node (ref "C6") (pin "2") (pinfunction "2_2") (pintype "passive"))
      (node (ref "C60") (pin "2") (pinfunction "2_2") (pintype "passive"))
      (node (ref "C61") (pin "2") (pinfunction "2_2") (pintype "passive"))
      (node (ref "C62") (pin "2") (pinfunction "2_2") (pintype "passive"))
      (node (ref "C63") (pin "2") (pinfunction "2_2") (pintype "passive"))
      (node (ref "C64") (pin "2") (pinfunction "2_2") (pintype "passive"))
      (node (ref "C65") (pin "2") (pinfunction "2_2") (pintype "passive"))
      (node (ref "C66") (pin "2") (pinfunction "2_2") (pintype "passive"))
      (node (ref "C67") (pin "2") (pinfunction "2_2") (pintype "passive"))
      (node (ref "C68") (pin "2") (pinfunction "2_2") (pintype "passive"))
      (node (ref "C69") (pin "2") (pinfunction "2_2") (pintype "passive"))
      (node (ref "C7") (pin "2") (pinfunction "2_2") (pintype "passive"))
      (node (ref "C70") (pin "2") (pinfunction "2_2") (pintype "passive"))
      (node (ref "C71") (pin "2") (pinfunction "2_2") (pintype "passive"))
      (node (ref "C72") (pin "2") (pinfunction "2_2") (pintype "passive"))
      (node (ref "C73") (pin "2") (pinfunction "2_2") (pintype "passive"))
      (node (ref "C74") (pin "2") (pinfunction "2_2") (pintype "passive"))
      (node (ref "C75") (pin "2") (pinfunction "2_2") (pintype "passive"))
      (node (ref "C76") (pin "2") (pinfunction "2_2") (pintype "passive"))
      (node (ref "C77") (pin "2") (pinfunction "2_2") (pintype "passive"))
      (node (ref "C78") (pin "2") (pinfunction "2_2") (pintype "passive"))
      (node (ref "C79") (pin "2") (pinfunction "2_2") (pintype "passive"))
      (node (ref "C8") (pin "2") (pinfunction "2_2") (pintype "passive"))
      (node (ref "C80") (pin "2") (pinfunction "2_2") (pintype "passive"))
      (node (ref "C81") (pin "2") (pinfunction "2_2") (pintype "passive"))
      (node (ref "C82") (pin "2") (pinfunction "2_2") (pintype "passive"))
      (node (ref "C83") (pin "2") (pinfunction "2_2") (pintype "passive"))
      (node (ref "C84") (pin "2") (pinfunction "2_2") (pintype "passive"))
      (node (ref "C85") (pin "2") (pinfunction "2_2") (pintype "passive"))
      (node (ref "C86") (pin "2") (pinfunction "2_2") (pintype "passive"))
      (node (ref "C87") (pin "2") (pinfunction "2_2") (pintype "passive"))
      (node (ref "C88") (pin "2") (pinfunction "2_2") (pintype "passive"))
      (node (ref "C89") (pin "2") (pinfunction "2_2") (pintype "passive"))
      (node (ref "C9") (pin "2") (pinfunction "2_2") (pintype "passive"))
      (node (ref "C90") (pin "2") (pinfunction "2_2") (pintype "passive"))
      (node (ref "C91") (pin "2") (pinfunction "2_2") (pintype "passive"))
      (node (ref "C92") (pin "2") (pinfunction "2_2") (pintype "passive"))
      (node (ref "C93") (pin "2") (pinfunction "2_2") (pintype "passive"))
      (node (ref "C94") (pin "2") (pinfunction "2_2") (pintype "passive"))
      (node (ref "C95") (pin "2") (pinfunction "2_2") (pintype "passive"))
      (node (ref "C96") (pin "2") (pinfunction "2_2") (pintype "passive"))
      (node (ref "C97") (pin "2") (pinfunction "2_2") (pintype "passive"))
      (node (ref "C98") (pin "2") (pinfunction "2_2") (pintype "passive"))
      (node (ref "C99") (pin "2") (pinfunction "2_2") (pintype "passive"))
      (node (ref "LED1") (pin "3") (pinfunction "VSS_3") (pintype "bidirectional"))
      (node (ref "LED10") (pin "3") (pinfunction "VSS_3") (pintype "bidirectional"))
      (node (ref "LED100") (pin "3") (pinfunction "VSS_3") (pintype "bidirectional"))
      (node (ref "LED101") (pin "3") (pinfunction "VSS_3") (pintype "bidirectional"))
      (node (ref "LED102") (pin "3") (pinfunction "VSS_3") (pintype "bidirectional"))
      (node (ref "LED103") (pin "3") (pinfunction "VSS_3") (pintype "bidirectional"))
      (node (ref "LED104") (pin "3") (pinfunction "VSS_3") (pintype "bidirectional"))
      (node (ref "LED105") (pin "3") (pinfunction "VSS_3") (pintype "bidirectional"))
      (node (ref "LED106") (pin "3") (pinfunction "VSS_3") (pintype "bidirectional"))
      (node (ref "LED107") (pin "3") (pinfunction "VSS_3") (pintype "bidirectional"))
      (node (ref "LED108") (pin "3") (pinfunction "VSS_3") (pintype "bidirectional"))
      (node (ref "LED109") (pin "3") (pinfunction "VSS_3") (pintype "bidirectional"))
      (node (ref "LED11") (pin "3") (pinfunction "VSS_3") (pintype "bidirectional"))
      (node (ref "LED110") (pin "3") (pinfunction "VSS_3") (pintype "bidirectional"))
      (node (ref "LED111") (pin "3") (pinfunction "VSS_3") (pintype "bidirectional"))
      (node (ref "LED112") (pin "3") (pinfunction "VSS_3") (pintype "bidirectional"))
      (node (ref "LED113") (pin "3") (pinfunction "VSS_3") (pintype "bidirectional"))
      (node (ref "LED114") (pin "3") (pinfunction "VSS_3") (pintype "bidirectional"))
      (node (ref "LED115") (pin "3") (pinfunction "VSS_3") (pintype "bidirectional"))
      (node (ref "LED116") (pin "3") (pinfunction "VSS_3") (pintype "bidirectional"))
      (node (ref "LED117") (pin "3") (pinfunction "VSS_3") (pintype "bidirectional"))
      (node (ref "LED118") (pin "3") (pinfunction "VSS_3") (pintype "bidirectional"))
      (node (ref "LED119") (pin "3") (pinfunction "VSS_3") (pintype "bidirectional"))
      (node (ref "LED12") (pin "3") (pinfunction "VSS_3") (pintype "bidirectional"))
      (node (ref "LED120") (pin "3") (pinfunction "VSS_3") (pintype "bidirectional"))
      (node (ref "LED121") (pin "3") (pinfunction "VSS_3") (pintype "bidirectional"))
      (node (ref "LED122") (pin "3") (pinfunction "VSS_3") (pintype "bidirectional"))
      (node (ref "LED123") (pin "3") (pinfunction "VSS_3") (pintype "bidirectional"))
      (node (ref "LED124") (pin "3") (pinfunction "VSS_3") (pintype "bidirectional"))
      (node (ref "LED125") (pin "3") (pinfunction "VSS_3") (pintype "bidirectional"))
      (node (ref "LED126") (pin "3") (pinfunction "VSS_3") (pintype "bidirectional"))
      (node (ref "LED127") (pin "3") (pinfunction "VSS_3") (pintype "bidirectional"))
      (node (ref "LED128") (pin "3") (pinfunction "VSS_3") (pintype "bidirectional"))
      (node (ref "LED129") (pin "3") (pinfunction "VSS_3") (pintype "bidirectional"))
      (node (ref "LED13") (pin "3") (pinfunction "VSS_3") (pintype "bidirectional"))
      (node (ref "LED130") (pin "3") (pinfunction "VSS_3") (pintype "bidirectional"))
      (node (ref "LED131") (pin "3") (pinfunction "VSS_3") (pintype "bidirectional"))
      (node (ref "LED132") (pin "3") (pinfunction "VSS_3") (pintype "bidirectional"))
      (node (ref "LED133") (pin "3") (pinfunction "VSS_3") (pintype "bidirectional"))
      (node (ref "LED134") (pin "3") (pinfunction "VSS_3") (pintype "bidirectional"))
      (node (ref "LED135") (pin "3") (pinfunction "VSS_3") (pintype "bidirectional"))
      (node (ref "LED136") (pin "3") (pinfunction "VSS_3") (pintype "bidirectional"))
      (node (ref "LED137") (pin "3") (pinfunction "VSS_3") (pintype "bidirectional"))
      (node (ref "LED138") (pin "3") (pinfunction "VSS_3") (pintype "bidirectional"))
      (node (ref "LED139") (pin "3") (pinfunction "VSS_3") (pintype "bidirectional"))
      (node (ref "LED14") (pin "3") (pinfunction "VSS_3") (pintype "bidirectional"))
      (node (ref "LED140") (pin "3") (pinfunction "VSS_3") (pintype "bidirectional"))
      (node (ref "LED141") (pin "3") (pinfunction "VSS_3") (pintype "bidirectional"))
      (node (ref "LED142") (pin "3") (pinfunction "VSS_3") (pintype "bidirectional"))
      (node (ref "LED143") (pin "3") (pinfunction "VSS_3") (pintype "bidirectional"))
      (node (ref "LED144") (pin "3") (pinfunction "VSS_3") (pintype "bidirectional"))
      (node (ref "LED145") (pin "3") (pinfunction "VSS_3") (pintype "bidirectional"))
      (node (ref "LED146") (pin "3") (pinfunction "VSS_3") (pintype "bidirectional"))
      (node (ref "LED147") (pin "3") (pinfunction "VSS_3") (pintype "bidirectional"))
      (node (ref "LED148") (pin "3") (pinfunction "VSS_3") (pintype "bidirectional"))
      (node (ref "LED149") (pin "3") (pinfunction "VSS_3") (pintype "bidirectional"))
      (node (ref "LED15") (pin "3") (pinfunction "VSS_3") (pintype "bidirectional"))
      (node (ref "LED150") (pin "3") (pinfunction "VSS_3") (pintype "bidirectional"))
      (node (ref "LED151") (pin "3") (pinfunction "VSS_3") (pintype "bidirectional"))
      (node (ref "LED152") (pin "3") (pinfunction "VSS_3") (pintype "bidirectional"))
      (node (ref "LED153") (pin "3") (pinfunction "VSS_3") (pintype "bidirectional"))
      (node (ref "LED154") (pin "3") (pinfunction "VSS_3") (pintype "bidirectional"))
      (node (ref "LED155") (pin "3") (pinfunction "VSS_3") (pintype "bidirectional"))
      (node (ref "LED156") (pin "3") (pinfunction "VSS_3") (pintype "bidirectional"))
      (node (ref "LED157") (pin "3") (pinfunction "VSS_3") (pintype "bidirectional"))
      (node (ref "LED158") (pin "3") (pinfunction "VSS_3") (pintype "bidirectional"))
      (node (ref "LED159") (pin "3") (pinfunction "VSS_3") (pintype "bidirectional"))
      (node (ref "LED16") (pin "3") (pinfunction "VSS_3") (pintype "bidirectional"))
      (node (ref "LED160") (pin "3") (pinfunction "VSS_3") (pintype "bidirectional"))
      (node (ref "LED161") (pin "3") (pinfunction "VSS_3") (pintype "bidirectional"))
      (node (ref "LED162") (pin "3") (pinfunction "VSS_3") (pintype "bidirectional"))
      (node (ref "LED163") (pin "3") (pinfunction "VSS_3") (pintype "bidirectional"))
      (node (ref "LED164") (pin "3") (pinfunction "VSS_3") (pintype "bidirectional"))
      (node (ref "LED165") (pin "3") (pinfunction "VSS_3") (pintype "bidirectional"))
      (node (ref "LED166") (pin "3") (pinfunction "VSS_3") (pintype "bidirectional"))
      (node (ref "LED167") (pin "3") (pinfunction "VSS_3") (pintype "bidirectional"))
      (node (ref "LED168") (pin "3") (pinfunction "VSS_3") (pintype "bidirectional"))
      (node (ref "LED169") (pin "3") (pinfunction "VSS_3") (pintype "bidirectional"))
      (node (ref "LED17") (pin "3") (pinfunction "VSS_3") (pintype "bidirectional"))
      (node (ref "LED170") (pin "3") (pinfunction "VSS_3") (pintype "bidirectional"))
      (node (ref "LED171") (pin "3") (pinfunction "VSS_3") (pintype "bidirectional"))
      (node (ref "LED172") (pin "3") (pinfunction "VSS_3") (pintype "bidirectional"))
      (node (ref "LED173") (pin "3") (pinfunction "VSS_3") (pintype "bidirectional"))
      (node (ref "LED174") (pin "3") (pinfunction "VSS_3") (pintype "bidirectional"))
      (node (ref "LED175") (pin "3") (pinfunction "VSS_3") (pintype "bidirectional"))
      (node (ref "LED176") (pin "3") (pinfunction "VSS_3") (pintype "bidirectional"))
      (node (ref "LED177") (pin "3") (pinfunction "VSS_3") (pintype "bidirectional"))
      (node (ref "LED178") (pin "3") (pinfunction "VSS_3") (pintype "bidirectional"))
      (node (ref "LED179") (pin "3") (pinfunction "VSS_3") (pintype "bidirectional"))
      (node (ref "LED18") (pin "3") (pinfunction "VSS_3") (pintype "bidirectional"))
      (node (ref "LED180") (pin "3") (pinfunction "VSS_3") (pintype "bidirectional"))
      (node (ref "LED181") (pin "3") (pinfunction "VSS_3") (pintype "bidirectional"))
      (node (ref "LED182") (pin "3") (pinfunction "VSS_3") (pintype "bidirectional"))
      (node (ref "LED183") (pin "3") (pinfunction "VSS_3") (pintype "bidirectional"))
      (node (ref "LED184") (pin "3") (pinfunction "VSS_3") (pintype "bidirectional"))
      (node (ref "LED185") (pin "3") (pinfunction "VSS_3") (pintype "bidirectional"))
      (node (ref "LED186") (pin "3") (pinfunction "VSS_3") (pintype "bidirectional"))
      (node (ref "LED187") (pin "3") (pinfunction "VSS_3") (pintype "bidirectional"))
      (node (ref "LED188") (pin "3") (pinfunction "VSS_3") (pintype "bidirectional"))
      (node (ref "LED189") (pin "3") (pinfunction "VSS_3") (pintype "bidirectional"))
      (node (ref "LED19") (pin "3") (pinfunction "VSS_3") (pintype "bidirectional"))
      (node (ref "LED190") (pin "3") (pinfunction "VSS_3") (pintype "bidirectional"))
      (node (ref "LED191") (pin "3") (pinfunction "VSS_3") (pintype "bidirectional"))
      (node (ref "LED192") (pin "3") (pinfunction "VSS_3") (pintype "bidirectional"))
      (node (ref "LED2") (pin "3") (pinfunction "VSS_3") (pintype "bidirectional"))
      (node (ref "LED20") (pin "3") (pinfunction "VSS_3") (pintype "bidirectional"))
      (node (ref "LED21") (pin "3") (pinfunction "VSS_3") (pintype "bidirectional"))
      (node (ref "LED22") (pin "3") (pinfunction "VSS_3") (pintype "bidirectional"))
      (node (ref "LED23") (pin "3") (pinfunction "VSS_3") (pintype "bidirectional"))
      (node (ref "LED24") (pin "3") (pinfunction "VSS_3") (pintype "bidirectional"))
      (node (ref "LED25") (pin "3") (pinfunction "VSS_3") (pintype "bidirectional"))
      (node (ref "LED26") (pin "3") (pinfunction "VSS_3") (pintype "bidirectional"))
      (node (ref "LED27") (pin "3") (pinfunction "VSS_3") (pintype "bidirectional"))
      (node (ref "LED28") (pin "3") (pinfunction "VSS_3") (pintype "bidirectional"))
      (node (ref "LED29") (pin "3") (pinfunction "VSS_3") (pintype "bidirectional"))
      (node (ref "LED3") (pin "3") (pinfunction "VSS_3") (pintype "bidirectional"))
      (node (ref "LED30") (pin "3") (pinfunction "VSS_3") (pintype "bidirectional"))
      (node (ref "LED31") (pin "3") (pinfunction "VSS_3") (pintype "bidirectional"))
      (node (ref "LED32") (pin "3") (pinfunction "VSS_3") (pintype "bidirectional"))
      (node (ref "LED33") (pin "3") (pinfunction "VSS_3") (pintype "bidirectional"))
      (node (ref "LED34") (pin "3") (pinfunction "VSS_3") (pintype "bidirectional"))
      (node (ref "LED35") (pin "3") (pinfunction "VSS_3") (pintype "bidirectional"))
      (node (ref "LED36") (pin "3") (pinfunction "VSS_3") (pintype "bidirectional"))
      (node (ref "LED37") (pin "3") (pinfunction "VSS_3") (pintype "bidirectional"))
      (node (ref "LED38") (pin "3") (pinfunction "VSS_3") (pintype "bidirectional"))
      (node (ref "LED39") (pin "3") (pinfunction "VSS_3") (pintype "bidirectional"))
      (node (ref "LED4") (pin "3") (pinfunction "VSS_3") (pintype "bidirectional"))
      (node (ref "LED40") (pin "3") (pinfunction "VSS_3") (pintype "bidirectional"))
      (node (ref "LED41") (pin "3") (pinfunction "VSS_3") (pintype "bidirectional"))
      (node (ref "LED42") (pin "3") (pinfunction "VSS_3") (pintype "bidirectional"))
      (node (ref "LED43") (pin "3") (pinfunction "VSS_3") (pintype "bidirectional"))
      (node (ref "LED44") (pin "3") (pinfunction "VSS_3") (pintype "bidirectional"))
      (node (ref "LED45") (pin "3") (pinfunction "VSS_3") (pintype "bidirectional"))
      (node (ref "LED46") (pin "3") (pinfunction "VSS_3") (pintype "bidirectional"))
      (node (ref "LED47") (pin "3") (pinfunction "VSS_3") (pintype "bidirectional"))
      (node (ref "LED48") (pin "3") (pinfunction "VSS_3") (pintype "bidirectional"))
      (node (ref "LED49") (pin "3") (pinfunction "VSS_3") (pintype "bidirectional"))
      (node (ref "LED5") (pin "3") (pinfunction "VSS_3") (pintype "bidirectional"))
      (node (ref "LED50") (pin "3") (pinfunction "VSS_3") (pintype "bidirectional"))
      (node (ref "LED51") (pin "3") (pinfunction "VSS_3") (pintype "bidirectional"))
      (node (ref "LED52") (pin "3") (pinfunction "VSS_3") (pintype "bidirectional"))
      (node (ref "LED53") (pin "3") (pinfunction "VSS_3") (pintype "bidirectional"))
      (node (ref "LED54") (pin "3") (pinfunction "VSS_3") (pintype "bidirectional"))
      (node (ref "LED55") (pin "3") (pinfunction "VSS_3") (pintype "bidirectional"))
      (node (ref "LED56") (pin "3") (pinfunction "VSS_3") (pintype "bidirectional"))
      (node (ref "LED57") (pin "3") (pinfunction "VSS_3") (pintype "bidirectional"))
      (node (ref "LED58") (pin "3") (pinfunction "VSS_3") (pintype "bidirectional"))
      (node (ref "LED59") (pin "3") (pinfunction "VSS_3") (pintype "bidirectional"))
      (node (ref "LED6") (pin "3") (pinfunction "VSS_3") (pintype "bidirectional"))
      (node (ref "LED60") (pin "3") (pinfunction "VSS_3") (pintype "bidirectional"))
      (node (ref "LED61") (pin "3") (pinfunction "VSS_3") (pintype "bidirectional"))
      (node (ref "LED62") (pin "3") (pinfunction "VSS_3") (pintype "bidirectional"))
      (node (ref "LED63") (pin "3") (pinfunction "VSS_3") (pintype "bidirectional"))
      (node (ref "LED64") (pin "3") (pinfunction "VSS_3") (pintype "bidirectional"))
      (node (ref "LED65") (pin "3") (pinfunction "VSS_3") (pintype "bidirectional"))
      (node (ref "LED66") (pin "3") (pinfunction "VSS_3") (pintype "bidirectional"))
      (node (ref "LED67") (pin "3") (pinfunction "VSS_3") (pintype "bidirectional"))
      (node (ref "LED68") (pin "3") (pinfunction "VSS_3") (pintype "bidirectional"))
      (node (ref "LED69") (pin "3") (pinfunction "VSS_3") (pintype "bidirectional"))
      (node (ref "LED7") (pin "3") (pinfunction "VSS_3") (pintype "bidirectional"))
      (node (ref "LED70") (pin "3") (pinfunction "VSS_3") (pintype "bidirectional"))
      (node (ref "LED71") (pin "3") (pinfunction "VSS_3") (pintype "bidirectional"))
      (node (ref "LED72") (pin "3") (pinfunction "VSS_3") (pintype "bidirectional"))
      (node (ref "LED73") (pin "3") (pinfunction "VSS_3") (pintype "bidirectional"))
      (node (ref "LED74") (pin "3") (pinfunction "VSS_3") (pintype "bidirectional"))
      (node (ref "LED75") (pin "3") (pinfunction "VSS_3") (pintype "bidirectional"))
      (node (ref "LED76") (pin "3") (pinfunction "VSS_3") (pintype "bidirectional"))
      (node (ref "LED77") (pin "3") (pinfunction "VSS_3") (pintype "bidirectional"))
      (node (ref "LED78") (pin "3") (pinfunction "VSS_3") (pintype "bidirectional"))
      (node (ref "LED79") (pin "3") (pinfunction "VSS_3") (pintype "bidirectional"))
      (node (ref "LED8") (pin "3") (pinfunction "VSS_3") (pintype "bidirectional"))
      (node (ref "LED80") (pin "3") (pinfunction "VSS_3") (pintype "bidirectional"))
      (node (ref "LED81") (pin "3") (pinfunction "VSS_3") (pintype "bidirectional"))
      (node (ref "LED82") (pin "3") (pinfunction "VSS_3") (pintype "bidirectional"))
      (node (ref "LED83") (pin "3") (pinfunction "VSS_3") (pintype "bidirectional"))
      (node (ref "LED84") (pin "3") (pinfunction "VSS_3") (pintype "bidirectional"))
      (node (ref "LED85") (pin "3") (pinfunction "VSS_3") (pintype "bidirectional"))
      (node (ref "LED86") (pin "3") (pinfunction "VSS_3") (pintype "bidirectional"))
      (node (ref "LED87") (pin "3") (pinfunction "VSS_3") (pintype "bidirectional"))
      (node (ref "LED88") (pin "3") (pinfunction "VSS_3") (pintype "bidirectional"))
      (node (ref "LED89") (pin "3") (pinfunction "VSS_3") (pintype "bidirectional"))
      (node (ref "LED9") (pin "3") (pinfunction "VSS_3") (pintype "bidirectional"))
      (node (ref "LED90") (pin "3") (pinfunction "VSS_3") (pintype "bidirectional"))
      (node (ref "LED91") (pin "3") (pinfunction "VSS_3") (pintype "bidirectional"))
      (node (ref "LED92") (pin "3") (pinfunction "VSS_3") (pintype "bidirectional"))
      (node (ref "LED93") (pin "3") (pinfunction "VSS_3") (pintype "bidirectional"))
      (node (ref "LED94") (pin "3") (pinfunction "VSS_3") (pintype "bidirectional"))
      (node (ref "LED95") (pin "3") (pinfunction "VSS_3") (pintype "bidirectional"))
      (node (ref "LED96") (pin "3") (pinfunction "VSS_3") (pintype "bidirectional"))
      (node (ref "LED97") (pin "3") (pinfunction "VSS_3") (pintype "bidirectional"))
      (node (ref "LED98") (pin "3") (pinfunction "VSS_3") (pintype "bidirectional"))
      (node (ref "LED99") (pin "3") (pinfunction "VSS_3") (pintype "bidirectional"))
      (node (ref "PAD11") (pin "1") (pinfunction "P_1") (pintype "passive"))
      (node (ref "PAD15") (pin "1") (pinfunction "P_1") (pintype "passive"))
      (node (ref "PAD19") (pin "1") (pinfunction "P_1") (pintype "passive"))
      (node (ref "PAD23") (pin "1") (pinfunction "P_1") (pintype "passive"))
      (node (ref "PAD27") (pin "1") (pinfunction "P_1") (pintype "passive"))
      (node (ref "PAD3") (pin "1") (pinfunction "P_1") (pintype "passive"))
      (node (ref "PAD7") (pin "1") (pinfunction "P_1") (pintype "passive"))
    )
    (net (code "3") (name "Net-(LED1-DI)") (class "Default")
      (node (ref "LED1") (pin "4") (pinfunction "DI_4") (pintype "bidirectional"))
      (node (ref "PAD1") (pin "1") (pinfunction "P_1") (pintype "passive"))
    )
    (net (code "4") (name "Net-(LED1-DO)") (class "Default")
      (node (ref "LED1") (pin "2") (pinfunction "DO_2") (pintype "bidirectional"))
      (node (ref "LED2") (pin "4") (pinfunction "DI_4") (pintype "bidirectional"))
    )
    (net (code "5") (name "Net-(LED2-DO)") (class "Default")
      (node (ref "LED2") (pin "2") (pinfunction "DO_2") (pintype "bidirectional"))
      (node (ref "LED3") (pin "4") (pinfunction "DI_4") (pintype "bidirectional"))
    )
    (net (code "6") (name "Net-(LED3-DO)") (class "Default")
      (node (ref "LED3") (pin "2") (pinfunction "DO_2") (pintype "bidirectional"))
      (node (ref "LED4") (pin "4") (pinfunction "DI_4") (pintype "bidirectional"))
    )
    (net (code "7") (name "Net-(LED4-DO)") (class "Default")
      (node (ref "LED4") (pin "2") (pinfunction "DO_2") (pintype "bidirectional"))
      (node (ref "LED5") (pin "4") (pinfunction "DI_4") (pintype "bidirectional"))
    )
    (net (code "8") (name "Net-(LED5-DO)") (class "Default")
      (node (ref "LED5") (pin "2") (pinfunction "DO_2") (pintype "bidirectional"))
      (node (ref "LED6") (pin "4") (pinfunction "DI_4") (pintype "bidirectional"))
    )
    (net (code "9") (name "Net-(LED6-DO)") (class "Default")
      (node (ref "LED6") (pin "2") (pinfunction "DO_2") (pintype "bidirectional"))
      (node (ref "LED7") (pin "4") (pinfunction "DI_4") (pintype "bidirectional"))
    )
    (net (code "10") (name "Net-(LED7-DO)") (class "Default")
      (node (ref "LED7") (pin "2") (pinfunction "DO_2") (pintype "bidirectional"))
      (node (ref "LED8") (pin "4") (pinfunction "DI_4") (pintype "bidirectional"))
    )
    (net (code "11") (name "Net-(LED8-DO)") (class "Default")
      (node (ref "LED8") (pin "2") (pinfunction "DO_2") (pintype "bidirectional"))
      (node (ref "PAD4") (pin "1") (pinfunction "P_1") (pintype "passive"))
    )
    (net (code "12") (name "Net-(LED9-DI)") (class "Default")
      (node (ref "LED9") (pin "4") (pinfunction "DI_4") (pintype "bidirectional"))
      (node (ref "PAD9") (pin "1") (pinfunction "P_1") (pintype "passive"))
    )
    (net (code "13") (name "Net-(LED10-DI)") (class "Default")
      (node (ref "LED10") (pin "4") (pinfunction "DI_4") (pintype "bidirectional"))
      (node (ref "LED9") (pin "2") (pinfunction "DO_2") (pintype "bidirectional"))
    )
    (net (code "14") (name "Net-(LED10-DO)") (class "Default")
      (node (ref "LED10") (pin "2") (pinfunction "DO_2") (pintype "bidirectional"))
      (node (ref "LED11") (pin "4") (pinfunction "DI_4") (pintype "bidirectional"))
    )
    (net (code "15") (name "Net-(LED11-DO)") (class "Default")
      (node (ref "LED11") (pin "2") (pinfunction "DO_2") (pintype "bidirectional"))
      (node (ref "LED12") (pin "4") (pinfunction "DI_4") (pintype "bidirectional"))
    )
    (net (code "16") (name "Net-(LED12-DO)") (class "Default")
      (node (ref "LED12") (pin "2") (pinfunction "DO_2") (pintype "bidirectional"))
      (node (ref "LED13") (pin "4") (pinfunction "DI_4") (pintype "bidirectional"))
    )
    (net (code "17") (name "Net-(LED13-DO)") (class "Default")
      (node (ref "LED13") (pin "2") (pinfunction "DO_2") (pintype "bidirectional"))
      (node (ref "LED14") (pin "4") (pinfunction "DI_4") (pintype "bidirectional"))
    )
    (net (code "18") (name "Net-(LED14-DO)") (class "Default")
      (node (ref "LED14") (pin "2") (pinfunction "DO_2") (pintype "bidirectional"))
      (node (ref "LED15") (pin "4") (pinfunction "DI_4") (pintype "bidirectional"))
    )
    (net (code "19") (name "Net-(LED15-DO)") (class "Default")
      (node (ref "LED15") (pin "2") (pinfunction "DO_2") (pintype "bidirectional"))
      (node (ref "LED16") (pin "4") (pinfunction "DI_4") (pintype "bidirectional"))
    )
    (net (code "20") (name "Net-(LED16-DO)") (class "Default")
      (node (ref "LED16") (pin "2") (pinfunction "DO_2") (pintype "bidirectional"))
      (node (ref "LED17") (pin "4") (pinfunction "DI_4") (pintype "bidirectional"))
    )
    (net (code "21") (name "Net-(LED17-DO)") (class "Default")
      (node (ref "LED17") (pin "2") (pinfunction "DO_2") (pintype "bidirectional"))
      (node (ref "LED18") (pin "4") (pinfunction "DI_4") (pintype "bidirectional"))
    )
    (net (code "22") (name "Net-(LED18-DO)") (class "Default")
      (node (ref "LED18") (pin "2") (pinfunction "DO_2") (pintype "bidirectional"))
      (node (ref "LED19") (pin "4") (pinfunction "DI_4") (pintype "bidirectional"))
    )
    (net (code "23") (name "Net-(LED19-DO)") (class "Default")
      (node (ref "LED19") (pin "2") (pinfunction "DO_2") (pintype "bidirectional"))
      (node (ref "LED20") (pin "4") (pinfunction "DI_4") (pintype "bidirectional"))
    )
    (net (code "24") (name "Net-(LED20-DO)") (class "Default")
      (node (ref "LED20") (pin "2") (pinfunction "DO_2") (pintype "bidirectional"))
      (node (ref "LED21") (pin "4") (pinfunction "DI_4") (pintype "bidirectional"))
    )
    (net (code "25") (name "Net-(LED21-DO)") (class "Default")
      (node (ref "LED21") (pin "2") (pinfunction "DO_2") (pintype "bidirectional"))
      (node (ref "LED22") (pin "4") (pinfunction "DI_4") (pintype "bidirectional"))
    )
    (net (code "26") (name "Net-(LED22-DO)") (class "Default")
      (node (ref "LED22") (pin "2") (pinfunction "DO_2") (pintype "bidirectional"))
      (node (ref "LED23") (pin "4") (pinfunction "DI_4") (pintype "bidirectional"))
    )
    (net (code "27") (name "Net-(LED23-DO)") (class "Default")
      (node (ref "LED23") (pin "2") (pinfunction "DO_2") (pintype "bidirectional"))
      (node (ref "LED24") (pin "4") (pinfunction "DI_4") (pintype "bidirectional"))
    )
    (net (code "28") (name "Net-(LED24-DO)") (class "Default")
      (node (ref "LED24") (pin "2") (pinfunction "DO_2") (pintype "bidirectional"))
      (node (ref "PAD12") (pin "1") (pinfunction "P_1") (pintype "passive"))
    )
    (net (code "29") (name "Net-(LED25-DI)") (class "Default")
      (node (ref "LED25") (pin "4") (pinfunction "DI_4") (pintype "bidirectional"))
      (node (ref "PAD13") (pin "1") (pinfunction "P_1") (pintype "passive"))
    )
    (net (code "30") (name "Net-(LED25-DO)") (class "Default")
      (node (ref "LED25") (pin "2") (pinfunction "DO_2") (pintype "bidirectional"))
      (node (ref "LED26") (pin "4") (pinfunction "DI_4") (pintype "bidirectional"))
    )
    (net (code "31") (name "Net-(LED26-DO)") (class "Default")
      (node (ref "LED26") (pin "2") (pinfunction "DO_2") (pintype "bidirectional"))
      (node (ref "LED27") (pin "4") (pinfunction "DI_4") (pintype "bidirectional"))
    )
    (net (code "32") (name "Net-(LED27-DO)") (class "Default")
      (node (ref "LED27") (pin "2") (pinfunction "DO_2") (pintype "bidirectional"))
      (node (ref "LED28") (pin "4") (pinfunction "DI_4") (pintype "bidirectional"))
    )
    (net (code "33") (name "Net-(LED28-DO)") (class "Default")
      (node (ref "LED28") (pin "2") (pinfunction "DO_2") (pintype "bidirectional"))
      (node (ref "LED29") (pin "4") (pinfunction "DI_4") (pintype "bidirectional"))
    )
    (net (code "34") (name "Net-(LED29-DO)") (class "Default")
      (node (ref "LED29") (pin "2") (pinfunction "DO_2") (pintype "bidirectional"))
      (node (ref "LED30") (pin "4") (pinfunction "DI_4") (pintype "bidirectional"))
    )
    (net (code "35") (name "Net-(LED30-DO)") (class "Default")
      (node (ref "LED30") (pin "2") (pinfunction "DO_2") (pintype "bidirectional"))
      (node (ref "LED31") (pin "4") (pinfunction "DI_4") (pintype "bidirectional"))
    )
    (net (code "36") (name "Net-(LED31-DO)") (class "Default")
      (node (ref "LED31") (pin "2") (pinfunction "DO_2") (pintype "bidirectional"))
      (node (ref "LED32") (pin "4") (pinfunction "DI_4") (pintype "bidirectional"))
    )
    (net (code "37") (name "Net-(LED32-DO)") (class "Default")
      (node (ref "LED32") (pin "2") (pinfunction "DO_2") (pintype "bidirectional"))
      (node (ref "LED33") (pin "4") (pinfunction "DI_4") (pintype "bidirectional"))
    )
    (net (code "38") (name "Net-(LED33-DO)") (class "Default")
      (node (ref "LED33") (pin "2") (pinfunction "DO_2") (pintype "bidirectional"))
      (node (ref "LED34") (pin "4") (pinfunction "DI_4") (pintype "bidirectional"))
    )
    (net (code "39") (name "Net-(LED34-DO)") (class "Default")
      (node (ref "LED34") (pin "2") (pinfunction "DO_2") (pintype "bidirectional"))
      (node (ref "LED35") (pin "4") (pinfunction "DI_4") (pintype "bidirectional"))
    )
    (net (code "40") (name "Net-(LED35-DO)") (class "Default")
      (node (ref "LED35") (pin "2") (pinfunction "DO_2") (pintype "bidirectional"))
      (node (ref "LED36") (pin "4") (pinfunction "DI_4") (pintype "bidirectional"))
    )
    (net (code "41") (name "Net-(LED36-DO)") (class "Default")
      (node (ref "LED36") (pin "2") (pinfunction "DO_2") (pintype "bidirectional"))
      (node (ref "LED37") (pin "4") (pinfunction "DI_4") (pintype "bidirectional"))
    )
    (net (code "42") (name "Net-(LED37-DO)") (class "Default")
      (node (ref "LED37") (pin "2") (pinfunction "DO_2") (pintype "bidirectional"))
      (node (ref "LED38") (pin "4") (pinfunction "DI_4") (pintype "bidirectional"))
    )
    (net (code "43") (name "Net-(LED38-DO)") (class "Default")
      (node (ref "LED38") (pin "2") (pinfunction "DO_2") (pintype "bidirectional"))
      (node (ref "LED39") (pin "4") (pinfunction "DI_4") (pintype "bidirectional"))
    )
    (net (code "44") (name "Net-(LED39-DO)") (class "Default")
      (node (ref "LED39") (pin "2") (pinfunction "DO_2") (pintype "bidirectional"))
      (node (ref "LED40") (pin "4") (pinfunction "DI_4") (pintype "bidirectional"))
    )
    (net (code "45") (name "Net-(LED40-DO)") (class "Default")
      (node (ref "LED40") (pin "2") (pinfunction "DO_2") (pintype "bidirectional"))
      (node (ref "LED41") (pin "4") (pinfunction "DI_4") (pintype "bidirectional"))
    )
    (net (code "46") (name "Net-(LED41-DO)") (class "Default")
      (node (ref "LED41") (pin "2") (pinfunction "DO_2") (pintype "bidirectional"))
      (node (ref "LED42") (pin "4") (pinfunction "DI_4") (pintype "bidirectional"))
    )
    (net (code "47") (name "Net-(LED42-DO)") (class "Default")
      (node (ref "LED42") (pin "2") (pinfunction "DO_2") (pintype "bidirectional"))
      (node (ref "LED43") (pin "4") (pinfunction "DI_4") (pintype "bidirectional"))
    )
    (net (code "48") (name "Net-(LED43-DO)") (class "Default")
      (node (ref "LED43") (pin "2") (pinfunction "DO_2") (pintype "bidirectional"))
      (node (ref "LED44") (pin "4") (pinfunction "DI_4") (pintype "bidirectional"))
    )
    (net (code "49") (name "Net-(LED44-DO)") (class "Default")
      (node (ref "LED44") (pin "2") (pinfunction "DO_2") (pintype "bidirectional"))
      (node (ref "LED45") (pin "4") (pinfunction "DI_4") (pintype "bidirectional"))
    )
    (net (code "50") (name "Net-(LED45-DO)") (class "Default")
      (node (ref "LED45") (pin "2") (pinfunction "DO_2") (pintype "bidirectional"))
      (node (ref "LED46") (pin "4") (pinfunction "DI_4") (pintype "bidirectional"))
    )
    (net (code "51") (name "Net-(LED46-DO)") (class "Default")
      (node (ref "LED46") (pin "2") (pinfunction "DO_2") (pintype "bidirectional"))
      (node (ref "LED47") (pin "4") (pinfunction "DI_4") (pintype "bidirectional"))
    )
    (net (code "52") (name "Net-(LED47-DO)") (class "Default")
      (node (ref "LED47") (pin "2") (pinfunction "DO_2") (pintype "bidirectional"))
      (node (ref "LED48") (pin "4") (pinfunction "DI_4") (pintype "bidirectional"))
    )
    (net (code "53") (name "Net-(LED48-DO)") (class "Default")
      (node (ref "LED48") (pin "2") (pinfunction "DO_2") (pintype "bidirectional"))
      (node (ref "PAD16") (pin "1") (pinfunction "P_1") (pintype "passive"))
    )
    (net (code "54") (name "Net-(LED49-DI)") (class "Default")
      (node (ref "LED49") (pin "4") (pinfunction "DI_4") (pintype "bidirectional"))
      (node (ref "PAD5") (pin "1") (pinfunction "P_1") (pintype "passive"))
    )
    (net (code "55") (name "Net-(LED49-DO)") (class "Default")
      (node (ref "LED49") (pin "2") (pinfunction "DO_2") (pintype "bidirectional"))
      (node (ref "LED50") (pin "4") (pinfunction "DI_4") (pintype "bidirectional"))
    )
    (net (code "56") (name "Net-(LED50-DO)") (class "Default")
      (node (ref "LED50") (pin "2") (pinfunction "DO_2") (pintype "bidirectional"))
      (node (ref "LED51") (pin "4") (pinfunction "DI_4") (pintype "bidirectional"))
    )
    (net (code "57") (name "Net-(LED51-DO)") (class "Default")
      (node (ref "LED51") (pin "2") (pinfunction "DO_2") (pintype "bidirectional"))
      (node (ref "LED52") (pin "4") (pinfunction "DI_4") (pintype "bidirectional"))
    )
    (net (code "58") (name "Net-(LED52-DO)") (class "Default")
      (node (ref "LED52") (pin "2") (pinfunction "DO_2") (pintype "bidirectional"))
      (node (ref "LED53") (pin "4") (pinfunction "DI_4") (pintype "bidirectional"))
    )
    (net (code "59") (name "Net-(LED53-DO)") (class "Default")
      (node (ref "LED53") (pin "2") (pinfunction "DO_2") (pintype "bidirectional"))
      (node (ref "LED54") (pin "4") (pinfunction "DI_4") (pintype "bidirectional"))
    )
    (net (code "60") (name "Net-(LED54-DO)") (class "Default")
      (node (ref "LED54") (pin "2") (pinfunction "DO_2") (pintype "bidirectional"))
      (node (ref "LED55") (pin "4") (pinfunction "DI_4") (pintype "bidirectional"))
    )
    (net (code "61") (name "Net-(LED55-DO)") (class "Default")
      (node (ref "LED55") (pin "2") (pinfunction "DO_2") (pintype "bidirectional"))
      (node (ref "LED56") (pin "4") (pinfunction "DI_4") (pintype "bidirectional"))
    )
    (net (code "62") (name "Net-(LED56-DO)") (class "Default")
      (node (ref "LED56") (pin "2") (pinfunction "DO_2") (pintype "bidirectional"))
      (node (ref "LED57") (pin "4") (pinfunction "DI_4") (pintype "bidirectional"))
    )
    (net (code "63") (name "Net-(LED57-DO)") (class "Default")
      (node (ref "LED57") (pin "2") (pinfunction "DO_2") (pintype "bidirectional"))
      (node (ref "LED58") (pin "4") (pinfunction "DI_4") (pintype "bidirectional"))
    )
    (net (code "64") (name "Net-(LED58-DO)") (class "Default")
      (node (ref "LED58") (pin "2") (pinfunction "DO_2") (pintype "bidirectional"))
      (node (ref "LED59") (pin "4") (pinfunction "DI_4") (pintype "bidirectional"))
    )
    (net (code "65") (name "Net-(LED59-DO)") (class "Default")
      (node (ref "LED59") (pin "2") (pinfunction "DO_2") (pintype "bidirectional"))
      (node (ref "LED60") (pin "4") (pinfunction "DI_4") (pintype "bidirectional"))
    )
    (net (code "66") (name "Net-(LED60-DO)") (class "Default")
      (node (ref "LED60") (pin "2") (pinfunction "DO_2") (pintype "bidirectional"))
      (node (ref "PAD8") (pin "1") (pinfunction "P_1") (pintype "passive"))
    )
    (net (code "67") (name "Net-(LED61-DI)") (class "Default")
      (node (ref "LED61") (pin "4") (pinfunction "DI_4") (pintype "bidirectional"))
      (node (ref "PAD17") (pin "1") (pinfunction "P_1") (pintype "passive"))
    )
    (net (code "68") (name "Net-(LED61-DO)") (class "Default")
      (node (ref "LED61") (pin "2") (pinfunction "DO_2") (pintype "bidirectional"))
      (node (ref "LED62") (pin "4") (pinfunction "DI_4") (pintype "bidirectional"))
    )
    (net (code "69") (name "Net-(LED62-DO)") (class "Default")
      (node (ref "LED62") (pin "2") (pinfunction "DO_2") (pintype "bidirectional"))
      (node (ref "LED63") (pin "4") (pinfunction "DI_4") (pintype "bidirectional"))
    )
    (net (code "70") (name "Net-(LED63-DO)") (class "Default")
      (node (ref "LED63") (pin "2") (pinfunction "DO_2") (pintype "bidirectional"))
      (node (ref "LED64") (pin "4") (pinfunction "DI_4") (pintype "bidirectional"))
    )
    (net (code "71") (name "Net-(LED64-DO)") (class "Default")
      (node (ref "LED64") (pin "2") (pinfunction "DO_2") (pintype "bidirectional"))
      (node (ref "LED65") (pin "4") (pinfunction "DI_4") (pintype "bidirectional"))
    )
    (net (code "72") (name "Net-(LED65-DO)") (class "Default")
      (node (ref "LED65") (pin "2") (pinfunction "DO_2") (pintype "bidirectional"))
      (node (ref "LED66") (pin "4") (pinfunction "DI_4") (pintype "bidirectional"))
    )
    (net (code "73") (name "Net-(LED66-DO)") (class "Default")
      (node (ref "LED66") (pin "2") (pinfunction "DO_2") (pintype "bidirectional"))
      (node (ref "LED67") (pin "4") (pinfunction "DI_4") (pintype "bidirectional"))
    )
    (net (code "74") (name "Net-(LED67-DO)") (class "Default")
      (node (ref "LED67") (pin "2") (pinfunction "DO_2") (pintype "bidirectional"))
      (node (ref "LED68") (pin "4") (pinfunction "DI_4") (pintype "bidirectional"))
    )
    (net (code "75") (name "Net-(LED68-DO)") (class "Default")
      (node (ref "LED68") (pin "2") (pinfunction "DO_2") (pintype "bidirectional"))
      (node (ref "LED69") (pin "4") (pinfunction "DI_4") (pintype "bidirectional"))
    )
    (net (code "76") (name "Net-(LED69-DO)") (class "Default")
      (node (ref "LED69") (pin "2") (pinfunction "DO_2") (pintype "bidirectional"))
      (node (ref "LED70") (pin "4") (pinfunction "DI_4") (pintype "bidirectional"))
    )
    (net (code "77") (name "Net-(LED70-DO)") (class "Default")
      (node (ref "LED70") (pin "2") (pinfunction "DO_2") (pintype "bidirectional"))
      (node (ref "LED71") (pin "4") (pinfunction "DI_4") (pintype "bidirectional"))
    )
    (net (code "78") (name "Net-(LED71-DO)") (class "Default")
      (node (ref "LED71") (pin "2") (pinfunction "DO_2") (pintype "bidirectional"))
      (node (ref "LED72") (pin "4") (pinfunction "DI_4") (pintype "bidirectional"))
    )
    (net (code "79") (name "Net-(LED72-DO)") (class "Default")
      (node (ref "LED72") (pin "2") (pinfunction "DO_2") (pintype "bidirectional"))
      (node (ref "LED73") (pin "4") (pinfunction "DI_4") (pintype "bidirectional"))
    )
    (net (code "80") (name "Net-(LED73-DO)") (class "Default")
      (node (ref "LED73") (pin "2") (pinfunction "DO_2") (pintype "bidirectional"))
      (node (ref "LED74") (pin "4") (pinfunction "DI_4") (pintype "bidirectional"))
    )
    (net (code "81") (name "Net-(LED74-DO)") (class "Default")
      (node (ref "LED74") (pin "2") (pinfunction "DO_2") (pintype "bidirectional"))
      (node (ref "LED75") (pin "4") (pinfunction "DI_4") (pintype "bidirectional"))
    )
    (net (code "82") (name "Net-(LED75-DO)") (class "Default")
      (node (ref "LED75") (pin "2") (pinfunction "DO_2") (pintype "bidirectional"))
      (node (ref "LED76") (pin "4") (pinfunction "DI_4") (pintype "bidirectional"))
    )
    (net (code "83") (name "Net-(LED76-DO)") (class "Default")
      (node (ref "LED76") (pin "2") (pinfunction "DO_2") (pintype "bidirectional"))
      (node (ref "LED77") (pin "4") (pinfunction "DI_4") (pintype "bidirectional"))
    )
    (net (code "84") (name "Net-(LED77-DO)") (class "Default")
      (node (ref "LED77") (pin "2") (pinfunction "DO_2") (pintype "bidirectional"))
      (node (ref "LED78") (pin "4") (pinfunction "DI_4") (pintype "bidirectional"))
    )
    (net (code "85") (name "Net-(LED78-DO)") (class "Default")
      (node (ref "LED78") (pin "2") (pinfunction "DO_2") (pintype "bidirectional"))
      (node (ref "LED79") (pin "4") (pinfunction "DI_4") (pintype "bidirectional"))
    )
    (net (code "86") (name "Net-(LED79-DO)") (class "Default")
      (node (ref "LED79") (pin "2") (pinfunction "DO_2") (pintype "bidirectional"))
      (node (ref "LED80") (pin "4") (pinfunction "DI_4") (pintype "bidirectional"))
    )
    (net (code "87") (name "Net-(LED80-DO)") (class "Default")
      (node (ref "LED80") (pin "2") (pinfunction "DO_2") (pintype "bidirectional"))
      (node (ref "LED81") (pin "4") (pinfunction "DI_4") (pintype "bidirectional"))
    )
    (net (code "88") (name "Net-(LED81-DO)") (class "Default")
      (node (ref "LED81") (pin "2") (pinfunction "DO_2") (pintype "bidirectional"))
      (node (ref "LED82") (pin "4") (pinfunction "DI_4") (pintype "bidirectional"))
    )
    (net (code "89") (name "Net-(LED82-DO)") (class "Default")
      (node (ref "LED82") (pin "2") (pinfunction "DO_2") (pintype "bidirectional"))
      (node (ref "LED83") (pin "4") (pinfunction "DI_4") (pintype "bidirectional"))
    )
    (net (code "90") (name "Net-(LED83-DO)") (class "Default")
      (node (ref "LED83") (pin "2") (pinfunction "DO_2") (pintype "bidirectional"))
      (node (ref "LED84") (pin "4") (pinfunction "DI_4") (pintype "bidirectional"))
    )
    (net (code "91") (name "Net-(LED84-DO)") (class "Default")
      (node (ref "LED84") (pin "2") (pinfunction "DO_2") (pintype "bidirectional"))
      (node (ref "LED85") (pin "4") (pinfunction "DI_4") (pintype "bidirectional"))
    )
    (net (code "92") (name "Net-(LED85-DO)") (class "Default")
      (node (ref "LED85") (pin "2") (pinfunction "DO_2") (pintype "bidirectional"))
      (node (ref "LED86") (pin "4") (pinfunction "DI_4") (pintype "bidirectional"))
    )
    (net (code "93") (name "Net-(LED86-DO)") (class "Default")
      (node (ref "LED86") (pin "2") (pinfunction "DO_2") (pintype "bidirectional"))
      (node (ref "LED87") (pin "4") (pinfunction "DI_4") (pintype "bidirectional"))
    )
    (net (code "94") (name "Net-(LED87-DO)") (class "Default")
      (node (ref "LED87") (pin "2") (pinfunction "DO_2") (pintype "bidirectional"))
      (node (ref "LED88") (pin "4") (pinfunction "DI_4") (pintype "bidirectional"))
    )
    (net (code "95") (name "Net-(LED88-DO)") (class "Default")
      (node (ref "LED88") (pin "2") (pinfunction "DO_2") (pintype "bidirectional"))
      (node (ref "LED89") (pin "4") (pinfunction "DI_4") (pintype "bidirectional"))
    )
    (net (code "96") (name "Net-(LED89-DO)") (class "Default")
      (node (ref "LED89") (pin "2") (pinfunction "DO_2") (pintype "bidirectional"))
      (node (ref "LED90") (pin "4") (pinfunction "DI_4") (pintype "bidirectional"))
    )
    (net (code "97") (name "Net-(LED90-DO)") (class "Default")
      (node (ref "LED90") (pin "2") (pinfunction "DO_2") (pintype "bidirectional"))
      (node (ref "LED91") (pin "4") (pinfunction "DI_4") (pintype "bidirectional"))
    )
    (net (code "98") (name "Net-(LED91-DO)") (class "Default")
      (node (ref "LED91") (pin "2") (pinfunction "DO_2") (pintype "bidirectional"))
      (node (ref "LED92") (pin "4") (pinfunction "DI_4") (pintype "bidirectional"))
    )
    (net (code "99") (name "Net-(LED92-DO)") (class "Default")
      (node (ref "LED92") (pin "2") (pinfunction "DO_2") (pintype "bidirectional"))
      (node (ref "PAD20") (pin "1") (pinfunction "P_1") (pintype "passive"))
    )
    (net (code "100") (name "Net-(LED93-DI)") (class "Default")
      (node (ref "LED93") (pin "4") (pinfunction "DI_4") (pintype "bidirectional"))
      (node (ref "PAD25") (pin "1") (pinfunction "P_1") (pintype "passive"))
    )
    (net (code "101") (name "Net-(LED93-DO)") (class "Default")
      (node (ref "LED93") (pin "2") (pinfunction "DO_2") (pintype "bidirectional"))
      (node (ref "LED94") (pin "4") (pinfunction "DI_4") (pintype "bidirectional"))
    )
    (net (code "102") (name "Net-(LED94-DO)") (class "Default")
      (node (ref "LED94") (pin "2") (pinfunction "DO_2") (pintype "bidirectional"))
      (node (ref "LED95") (pin "4") (pinfunction "DI_4") (pintype "bidirectional"))
    )
    (net (code "103") (name "Net-(LED95-DO)") (class "Default")
      (node (ref "LED95") (pin "2") (pinfunction "DO_2") (pintype "bidirectional"))
      (node (ref "LED96") (pin "4") (pinfunction "DI_4") (pintype "bidirectional"))
    )
    (net (code "104") (name "Net-(LED96-DO)") (class "Default")
      (node (ref "LED96") (pin "2") (pinfunction "DO_2") (pintype "bidirectional"))
      (node (ref "LED97") (pin "4") (pinfunction "DI_4") (pintype "bidirectional"))
    )
    (net (code "105") (name "Net-(LED97-DO)") (class "Default")
      (node (ref "LED97") (pin "2") (pinfunction "DO_2") (pintype "bidirectional"))
      (node (ref "LED98") (pin "4") (pinfunction "DI_4") (pintype "bidirectional"))
    )
    (net (code "106") (name "Net-(LED98-DO)") (class "Default")
      (node (ref "LED98") (pin "2") (pinfunction "DO_2") (pintype "bidirectional"))
      (node (ref "LED99") (pin "4") (pinfunction "DI_4") (pintype "bidirectional"))
    )
    (net (code "107") (name "Net-(LED100-DI)") (class "Default")
      (node (ref "LED100") (pin "4") (pinfunction "DI_4") (pintype "bidirectional"))
      (node (ref "LED99") (pin "2") (pinfunction "DO_2") (pintype "bidirectional"))
    )
    (net (code "108") (name "Net-(LED100-DO)") (class "Default")
      (node (ref "LED100") (pin "2") (pinfunction "DO_2") (pintype "bidirectional"))
      (node (ref "LED101") (pin "4") (pinfunction "DI_4") (pintype "bidirectional"))
    )
    (net (code "109") (name "Net-(LED101-DO)") (class "Default")
      (node (ref "LED101") (pin "2") (pinfunction "DO_2") (pintype "bidirectional"))
      (node (ref "LED102") (pin "4") (pinfunction "DI_4") (pintype "bidirectional"))
    )
    (net (code "110") (name "Net-(LED102-DO)") (class "Default")
      (node (ref "LED102") (pin "2") (pinfunction "DO_2") (pintype "bidirectional"))
      (node (ref "LED103") (pin "4") (pinfunction "DI_4") (pintype "bidirectional"))
    )
    (net (code "111") (name "Net-(LED103-DO)") (class "Default")
      (node (ref "LED103") (pin "2") (pinfunction "DO_2") (pintype "bidirectional"))
      (node (ref "LED104") (pin "4") (pinfunction "DI_4") (pintype "bidirectional"))
    )
    (net (code "112") (name "Net-(LED104-DO)") (class "Default")
      (node (ref "LED104") (pin "2") (pinfunction "DO_2") (pintype "bidirectional"))
      (node (ref "LED105") (pin "4") (pinfunction "DI_4") (pintype "bidirectional"))
    )
    (net (code "113") (name "Net-(LED105-DO)") (class "Default")
      (node (ref "LED105") (pin "2") (pinfunction "DO_2") (pintype "bidirectional"))
      (node (ref "LED106") (pin "4") (pinfunction "DI_4") (pintype "bidirectional"))
    )
    (net (code "114") (name "Net-(LED106-DO)") (class "Default")
      (node (ref "LED106") (pin "2") (pinfunction "DO_2") (pintype "bidirectional"))
      (node (ref "LED107") (pin "4") (pinfunction "DI_4") (pintype "bidirectional"))
    )
    (net (code "115") (name "Net-(LED107-DO)") (class "Default")
      (node (ref "LED107") (pin "2") (pinfunction "DO_2") (pintype "bidirectional"))
      (node (ref "LED108") (pin "4") (pinfunction "DI_4") (pintype "bidirectional"))
    )
    (net (code "116") (name "Net-(LED108-DO)") (class "Default")
      (node (ref "LED108") (pin "2") (pinfunction "DO_2") (pintype "bidirectional"))
      (node (ref "LED109") (pin "4") (pinfunction "DI_4") (pintype "bidirectional"))
    )
    (net (code "117") (name "Net-(LED109-DO)") (class "Default")
      (node (ref "LED109") (pin "2") (pinfunction "DO_2") (pintype "bidirectional"))
      (node (ref "LED110") (pin "4") (pinfunction "DI_4") (pintype "bidirectional"))
    )
    (net (code "118") (name "Net-(LED110-DO)") (class "Default")
      (node (ref "LED110") (pin "2") (pinfunction "DO_2") (pintype "bidirectional"))
      (node (ref "LED111") (pin "4") (pinfunction "DI_4") (pintype "bidirectional"))
    )
    (net (code "119") (name "Net-(LED111-DO)") (class "Default")
      (node (ref "LED111") (pin "2") (pinfunction "DO_2") (pintype "bidirectional"))
      (node (ref "LED112") (pin "4") (pinfunction "DI_4") (pintype "bidirectional"))
    )
    (net (code "120") (name "Net-(LED112-DO)") (class "Default")
      (node (ref "LED112") (pin "2") (pinfunction "DO_2") (pintype "bidirectional"))
      (node (ref "LED113") (pin "4") (pinfunction "DI_4") (pintype "bidirectional"))
    )
    (net (code "121") (name "Net-(LED113-DO)") (class "Default")
      (node (ref "LED113") (pin "2") (pinfunction "DO_2") (pintype "bidirectional"))
      (node (ref "LED114") (pin "4") (pinfunction "DI_4") (pintype "bidirectional"))
    )
    (net (code "122") (name "Net-(LED114-DO)") (class "Default")
      (node (ref "LED114") (pin "2") (pinfunction "DO_2") (pintype "bidirectional"))
      (node (ref "LED115") (pin "4") (pinfunction "DI_4") (pintype "bidirectional"))
    )
    (net (code "123") (name "Net-(LED115-DO)") (class "Default")
      (node (ref "LED115") (pin "2") (pinfunction "DO_2") (pintype "bidirectional"))
      (node (ref "LED116") (pin "4") (pinfunction "DI_4") (pintype "bidirectional"))
    )
    (net (code "124") (name "Net-(LED116-DO)") (class "Default")
      (node (ref "LED116") (pin "2") (pinfunction "DO_2") (pintype "bidirectional"))
      (node (ref "LED117") (pin "4") (pinfunction "DI_4") (pintype "bidirectional"))
    )
    (net (code "125") (name "Net-(LED117-DO)") (class "Default")
      (node (ref "LED117") (pin "2") (pinfunction "DO_2") (pintype "bidirectional"))
      (node (ref "LED118") (pin "4") (pinfunction "DI_4") (pintype "bidirectional"))
    )
    (net (code "126") (name "Net-(LED118-DO)") (class "Default")
      (node (ref "LED118") (pin "2") (pinfunction "DO_2") (pintype "bidirectional"))
      (node (ref "LED119") (pin "4") (pinfunction "DI_4") (pintype "bidirectional"))
    )
    (net (code "127") (name "Net-(LED119-DO)") (class "Default")
      (node (ref "LED119") (pin "2") (pinfunction "DO_2") (pintype "bidirectional"))
      (node (ref "LED120") (pin "4") (pinfunction "DI_4") (pintype "bidirectional"))
    )
    (net (code "128") (name "Net-(LED120-DO)") (class "Default")
      (node (ref "LED120") (pin "2") (pinfunction "DO_2") (pintype "bidirectional"))
      (node (ref "LED121") (pin "4") (pinfunction "DI_4") (pintype "bidirectional"))
    )
    (net (code "129") (name "Net-(LED121-DO)") (class "Default")
      (node (ref "LED121") (pin "2") (pinfunction "DO_2") (pintype "bidirectional"))
      (node (ref "LED122") (pin "4") (pinfunction "DI_4") (pintype "bidirectional"))
    )
    (net (code "130") (name "Net-(LED122-DO)") (class "Default")
      (node (ref "LED122") (pin "2") (pinfunction "DO_2") (pintype "bidirectional"))
      (node (ref "LED123") (pin "4") (pinfunction "DI_4") (pintype "bidirectional"))
    )
    (net (code "131") (name "Net-(LED123-DO)") (class "Default")
      (node (ref "LED123") (pin "2") (pinfunction "DO_2") (pintype "bidirectional"))
      (node (ref "LED124") (pin "4") (pinfunction "DI_4") (pintype "bidirectional"))
    )
    (net (code "132") (name "Net-(LED124-DO)") (class "Default")
      (node (ref "LED124") (pin "2") (pinfunction "DO_2") (pintype "bidirectional"))
      (node (ref "LED125") (pin "4") (pinfunction "DI_4") (pintype "bidirectional"))
    )
    (net (code "133") (name "Net-(LED125-DO)") (class "Default")
      (node (ref "LED125") (pin "2") (pinfunction "DO_2") (pintype "bidirectional"))
      (node (ref "LED126") (pin "4") (pinfunction "DI_4") (pintype "bidirectional"))
    )
    (net (code "134") (name "Net-(LED126-DO)") (class "Default")
      (node (ref "LED126") (pin "2") (pinfunction "DO_2") (pintype "bidirectional"))
      (node (ref "LED127") (pin "4") (pinfunction "DI_4") (pintype "bidirectional"))
    )
    (net (code "135") (name "Net-(LED127-DO)") (class "Default")
      (node (ref "LED127") (pin "2") (pinfunction "DO_2") (pintype "bidirectional"))
      (node (ref "LED128") (pin "4") (pinfunction "DI_4") (pintype "bidirectional"))
    )
    (net (code "136") (name "Net-(LED128-DO)") (class "Default")
      (node (ref "LED128") (pin "2") (pinfunction "DO_2") (pintype "bidirectional"))
      (node (ref "LED129") (pin "4") (pinfunction "DI_4") (pintype "bidirectional"))
    )
    (net (code "137") (name "Net-(LED129-DO)") (class "Default")
      (node (ref "LED129") (pin "2") (pinfunction "DO_2") (pintype "bidirectional"))
      (node (ref "LED130") (pin "4") (pinfunction "DI_4") (pintype "bidirectional"))
    )
    (net (code "138") (name "Net-(LED130-DO)") (class "Default")
      (node (ref "LED130") (pin "2") (pinfunction "DO_2") (pintype "bidirectional"))
      (node (ref "LED131") (pin "4") (pinfunction "DI_4") (pintype "bidirectional"))
    )
    (net (code "139") (name "Net-(LED131-DO)") (class "Default")
      (node (ref "LED131") (pin "2") (pinfunction "DO_2") (pintype "bidirectional"))
      (node (ref "LED132") (pin "4") (pinfunction "DI_4") (pintype "bidirectional"))
    )
    (net (code "140") (name "Net-(LED132-DO)") (class "Default")
      (node (ref "LED132") (pin "2") (pinfunction "DO_2") (pintype "bidirectional"))
      (node (ref "PAD28") (pin "1") (pinfunction "P_1") (pintype "passive"))
    )
    (net (code "141") (name "Net-(LED133-DI)") (class "Default")
      (node (ref "LED133") (pin "4") (pinfunction "DI_4") (pintype "bidirectional"))
      (node (ref "PAD21") (pin "1") (pinfunction "P_1") (pintype "passive"))
    )
    (net (code "142") (name "Net-(LED133-DO)") (class "Default")
      (node (ref "LED133") (pin "2") (pinfunction "DO_2") (pintype "bidirectional"))
      (node (ref "LED134") (pin "4") (pinfunction "DI_4") (pintype "bidirectional"))
    )
    (net (code "143") (name "Net-(LED134-DO)") (class "Default")
      (node (ref "LED134") (pin "2") (pinfunction "DO_2") (pintype "bidirectional"))
      (node (ref "LED135") (pin "4") (pinfunction "DI_4") (pintype "bidirectional"))
    )
    (net (code "144") (name "Net-(LED135-DO)") (class "Default")
      (node (ref "LED135") (pin "2") (pinfunction "DO_2") (pintype "bidirectional"))
      (node (ref "LED136") (pin "4") (pinfunction "DI_4") (pintype "bidirectional"))
    )
    (net (code "145") (name "Net-(LED136-DO)") (class "Default")
      (node (ref "LED136") (pin "2") (pinfunction "DO_2") (pintype "bidirectional"))
      (node (ref "LED137") (pin "4") (pinfunction "DI_4") (pintype "bidirectional"))
    )
    (net (code "146") (name "Net-(LED137-DO)") (class "Default")
      (node (ref "LED137") (pin "2") (pinfunction "DO_2") (pintype "bidirectional"))
      (node (ref "LED138") (pin "4") (pinfunction "DI_4") (pintype "bidirectional"))
    )
    (net (code "147") (name "Net-(LED138-DO)") (class "Default")
      (node (ref "LED138") (pin "2") (pinfunction "DO_2") (pintype "bidirectional"))
      (node (ref "LED139") (pin "4") (pinfunction "DI_4") (pintype "bidirectional"))
    )
    (net (code "148") (name "Net-(LED139-DO)") (class "Default")
      (node (ref "LED139") (pin "2") (pinfunction "DO_2") (pintype "bidirectional"))
      (node (ref "LED140") (pin "4") (pinfunction "DI_4") (pintype "bidirectional"))
    )
    (net (code "149") (name "Net-(LED140-DO)") (class "Default")
      (node (ref "LED140") (pin "2") (pinfunction "DO_2") (pintype "bidirectional"))
      (node (ref "LED141") (pin "4") (pinfunction "DI_4") (pintype "bidirectional"))
    )
    (net (code "150") (name "Net-(LED141-DO)") (class "Default")
      (node (ref "LED141") (pin "2") (pinfunction "DO_2") (pintype "bidirectional"))
      (node (ref "LED142") (pin "4") (pinfunction "DI_4") (pintype "bidirectional"))
    )
    (net (code "151") (name "Net-(LED142-DO)") (class "Default")
      (node (ref "LED142") (pin "2") (pinfunction "DO_2") (pintype "bidirectional"))
      (node (ref "LED143") (pin "4") (pinfunction "DI_4") (pintype "bidirectional"))
    )
    (net (code "152") (name "Net-(LED143-DO)") (class "Default")
      (node (ref "LED143") (pin "2") (pinfunction "DO_2") (pintype "bidirectional"))
      (node (ref "LED144") (pin "4") (pinfunction "DI_4") (pintype "bidirectional"))
    )
    (net (code "153") (name "Net-(LED144-DO)") (class "Default")
      (node (ref "LED144") (pin "2") (pinfunction "DO_2") (pintype "bidirectional"))
      (node (ref "LED145") (pin "4") (pinfunction "DI_4") (pintype "bidirectional"))
    )
    (net (code "154") (name "Net-(LED145-DO)") (class "Default")
      (node (ref "LED145") (pin "2") (pinfunction "DO_2") (pintype "bidirectional"))
      (node (ref "LED146") (pin "4") (pinfunction "DI_4") (pintype "bidirectional"))
    )
    (net (code "155") (name "Net-(LED146-DO)") (class "Default")
      (node (ref "LED146") (pin "2") (pinfunction "DO_2") (pintype "bidirectional"))
      (node (ref "LED147") (pin "4") (pinfunction "DI_4") (pintype "bidirectional"))
    )
    (net (code "156") (name "Net-(LED147-DO)") (class "Default")
      (node (ref "LED147") (pin "2") (pinfunction "DO_2") (pintype "bidirectional"))
      (node (ref "LED148") (pin "4") (pinfunction "DI_4") (pintype "bidirectional"))
    )
    (net (code "157") (name "Net-(LED148-DO)") (class "Default")
      (node (ref "LED148") (pin "2") (pinfunction "DO_2") (pintype "bidirectional"))
      (node (ref "LED149") (pin "4") (pinfunction "DI_4") (pintype "bidirectional"))
    )
    (net (code "158") (name "Net-(LED149-DO)") (class "Default")
      (node (ref "LED149") (pin "2") (pinfunction "DO_2") (pintype "bidirectional"))
      (node (ref "LED150") (pin "4") (pinfunction "DI_4") (pintype "bidirectional"))
    )
    (net (code "159") (name "Net-(LED150-DO)") (class "Default")
      (node (ref "LED150") (pin "2") (pinfunction "DO_2") (pintype "bidirectional"))
      (node (ref "LED151") (pin "4") (pinfunction "DI_4") (pintype "bidirectional"))
    )
    (net (code "160") (name "Net-(LED151-DO)") (class "Default")
      (node (ref "LED151") (pin "2") (pinfunction "DO_2") (pintype "bidirectional"))
      (node (ref "LED152") (pin "4") (pinfunction "DI_4") (pintype "bidirectional"))
    )
    (net (code "161") (name "Net-(LED152-DO)") (class "Default")
      (node (ref "LED152") (pin "2") (pinfunction "DO_2") (pintype "bidirectional"))
      (node (ref "LED153") (pin "4") (pinfunction "DI_4") (pintype "bidirectional"))
    )
    (net (code "162") (name "Net-(LED153-DO)") (class "Default")
      (node (ref "LED153") (pin "2") (pinfunction "DO_2") (pintype "bidirectional"))
      (node (ref "LED154") (pin "4") (pinfunction "DI_4") (pintype "bidirectional"))
    )
    (net (code "163") (name "Net-(LED154-DO)") (class "Default")
      (node (ref "LED154") (pin "2") (pinfunction "DO_2") (pintype "bidirectional"))
      (node (ref "LED155") (pin "4") (pinfunction "DI_4") (pintype "bidirectional"))
    )
    (net (code "164") (name "Net-(LED155-DO)") (class "Default")
      (node (ref "LED155") (pin "2") (pinfunction "DO_2") (pintype "bidirectional"))
      (node (ref "LED156") (pin "4") (pinfunction "DI_4") (pintype "bidirectional"))
    )
    (net (code "165") (name "Net-(LED156-DO)") (class "Default")
      (node (ref "LED156") (pin "2") (pinfunction "DO_2") (pintype "bidirectional"))
      (node (ref "LED157") (pin "4") (pinfunction "DI_4") (pintype "bidirectional"))
    )
    (net (code "166") (name "Net-(LED157-DO)") (class "Default")
      (node (ref "LED157") (pin "2") (pinfunction "DO_2") (pintype "bidirectional"))
      (node (ref "LED158") (pin "4") (pinfunction "DI_4") (pintype "bidirectional"))
    )
    (net (code "167") (name "Net-(LED158-DO)") (class "Default")
      (node (ref "LED158") (pin "2") (pinfunction "DO_2") (pintype "bidirectional"))
      (node (ref "LED159") (pin "4") (pinfunction "DI_4") (pintype "bidirectional"))
    )
    (net (code "168") (name "Net-(LED159-DO)") (class "Default")
      (node (ref "LED159") (pin "2") (pinfunction "DO_2") (pintype "bidirectional"))
      (node (ref "LED160") (pin "4") (pinfunction "DI_4") (pintype "bidirectional"))
    )
    (net (code "169") (name "Net-(LED160-DO)") (class "Default")
      (node (ref "LED160") (pin "2") (pinfunction "DO_2") (pintype "bidirectional"))
      (node (ref "LED161") (pin "4") (pinfunction "DI_4") (pintype "bidirectional"))
    )
    (net (code "170") (name "Net-(LED161-DO)") (class "Default")
      (node (ref "LED161") (pin "2") (pinfunction "DO_2") (pintype "bidirectional"))
      (node (ref "LED162") (pin "4") (pinfunction "DI_4") (pintype "bidirectional"))
    )
    (net (code "171") (name "Net-(LED162-DO)") (class "Default")
      (node (ref "LED162") (pin "2") (pinfunction "DO_2") (pintype "bidirectional"))
      (node (ref "LED163") (pin "4") (pinfunction "DI_4") (pintype "bidirectional"))
    )
    (net (code "172") (name "Net-(LED163-DO)") (class "Default")
      (node (ref "LED163") (pin "2") (pinfunction "DO_2") (pintype "bidirectional"))
      (node (ref "LED164") (pin "4") (pinfunction "DI_4") (pintype "bidirectional"))
    )
    (net (code "173") (name "Net-(LED164-DO)") (class "Default")
      (node (ref "LED164") (pin "2") (pinfunction "DO_2") (pintype "bidirectional"))
      (node (ref "LED165") (pin "4") (pinfunction "DI_4") (pintype "bidirectional"))
    )
    (net (code "174") (name "Net-(LED165-DO)") (class "Default")
      (node (ref "LED165") (pin "2") (pinfunction "DO_2") (pintype "bidirectional"))
      (node (ref "LED166") (pin "4") (pinfunction "DI_4") (pintype "bidirectional"))
    )
    (net (code "175") (name "Net-(LED166-DO)") (class "Default")
      (node (ref "LED166") (pin "2") (pinfunction "DO_2") (pintype "bidirectional"))
      (node (ref "LED167") (pin "4") (pinfunction "DI_4") (pintype "bidirectional"))
    )
    (net (code "176") (name "Net-(LED167-DO)") (class "Default")
      (node (ref "LED167") (pin "2") (pinfunction "DO_2") (pintype "bidirectional"))
      (node (ref "LED168") (pin "4") (pinfunction "DI_4") (pintype "bidirectional"))
    )
    (net (code "177") (name "Net-(LED168-DO)") (class "Default")
      (node (ref "LED168") (pin "2") (pinfunction "DO_2") (pintype "bidirectional"))
      (node (ref "LED169") (pin "4") (pinfunction "DI_4") (pintype "bidirectional"))
    )
    (net (code "178") (name "Net-(LED169-DO)") (class "Default")
      (node (ref "LED169") (pin "2") (pinfunction "DO_2") (pintype "bidirectional"))
      (node (ref "LED170") (pin "4") (pinfunction "DI_4") (pintype "bidirectional"))
    )
    (net (code "179") (name "Net-(LED170-DO)") (class "Default")
      (node (ref "LED170") (pin "2") (pinfunction "DO_2") (pintype "bidirectional"))
      (node (ref "LED171") (pin "4") (pinfunction "DI_4") (pintype "bidirectional"))
    )
    (net (code "180") (name "Net-(LED171-DO)") (class "Default")
      (node (ref "LED171") (pin "2") (pinfunction "DO_2") (pintype "bidirectional"))
      (node (ref "LED172") (pin "4") (pinfunction "DI_4") (pintype "bidirectional"))
    )
    (net (code "181") (name "Net-(LED172-DO)") (class "Default")
      (node (ref "LED172") (pin "2") (pinfunction "DO_2") (pintype "bidirectional"))
      (node (ref "LED173") (pin "4") (pinfunction "DI_4") (pintype "bidirectional"))
    )
    (net (code "182") (name "Net-(LED173-DO)") (class "Default")
      (node (ref "LED173") (pin "2") (pinfunction "DO_2") (pintype "bidirectional"))
      (node (ref "LED174") (pin "4") (pinfunction "DI_4") (pintype "bidirectional"))
    )
    (net (code "183") (name "Net-(LED174-DO)") (class "Default")
      (node (ref "LED174") (pin "2") (pinfunction "DO_2") (pintype "bidirectional"))
      (node (ref "LED175") (pin "4") (pinfunction "DI_4") (pintype "bidirectional"))
    )
    (net (code "184") (name "Net-(LED175-DO)") (class "Default")
      (node (ref "LED175") (pin "2") (pinfunction "DO_2") (pintype "bidirectional"))
      (node (ref "LED176") (pin "4") (pinfunction "DI_4") (pintype "bidirectional"))
    )
    (net (code "185") (name "Net-(LED176-DO)") (class "Default")
      (node (ref "LED176") (pin "2") (pinfunction "DO_2") (pintype "bidirectional"))
      (node (ref "LED177") (pin "4") (pinfunction "DI_4") (pintype "bidirectional"))
    )
    (net (code "186") (name "Net-(LED177-DO)") (class "Default")
      (node (ref "LED177") (pin "2") (pinfunction "DO_2") (pintype "bidirectional"))
      (node (ref "LED178") (pin "4") (pinfunction "DI_4") (pintype "bidirectional"))
    )
    (net (code "187") (name "Net-(LED178-DO)") (class "Default")
      (node (ref "LED178") (pin "2") (pinfunction "DO_2") (pintype "bidirectional"))
      (node (ref "LED179") (pin "4") (pinfunction "DI_4") (pintype "bidirectional"))
    )
    (net (code "188") (name "Net-(LED179-DO)") (class "Default")
      (node (ref "LED179") (pin "2") (pinfunction "DO_2") (pintype "bidirectional"))
      (node (ref "LED180") (pin "4") (pinfunction "DI_4") (pintype "bidirectional"))
    )
    (net (code "189") (name "Net-(LED180-DO)") (class "Default")
      (node (ref "LED180") (pin "2") (pinfunction "DO_2") (pintype "bidirectional"))
      (node (ref "LED181") (pin "4") (pinfunction "DI_4") (pintype "bidirectional"))
    )
    (net (code "190") (name "Net-(LED181-DO)") (class "Default")
      (node (ref "LED181") (pin "2") (pinfunction "DO_2") (pintype "bidirectional"))
      (node (ref "LED182") (pin "4") (pinfunction "DI_4") (pintype "bidirectional"))
    )
    (net (code "191") (name "Net-(LED182-DO)") (class "Default")
      (node (ref "LED182") (pin "2") (pinfunction "DO_2") (pintype "bidirectional"))
      (node (ref "LED183") (pin "4") (pinfunction "DI_4") (pintype "bidirectional"))
    )
    (net (code "192") (name "Net-(LED183-DO)") (class "Default")
      (node (ref "LED183") (pin "2") (pinfunction "DO_2") (pintype "bidirectional"))
      (node (ref "LED184") (pin "4") (pinfunction "DI_4") (pintype "bidirectional"))
    )
    (net (code "193") (name "Net-(LED184-DO)") (class "Default")
      (node (ref "LED184") (pin "2") (pinfunction "DO_2") (pintype "bidirectional"))
      (node (ref "LED185") (pin "4") (pinfunction "DI_4") (pintype "bidirectional"))
    )
    (net (code "194") (name "Net-(LED185-DO)") (class "Default")
      (node (ref "LED185") (pin "2") (pinfunction "DO_2") (pintype "bidirectional"))
      (node (ref "LED186") (pin "4") (pinfunction "DI_4") (pintype "bidirectional"))
    )
    (net (code "195") (name "Net-(LED186-DO)") (class "Default")
      (node (ref "LED186") (pin "2") (pinfunction "DO_2") (pintype "bidirectional"))
      (node (ref "LED187") (pin "4") (pinfunction "DI_4") (pintype "bidirectional"))
    )
    (net (code "196") (name "Net-(LED187-DO)") (class "Default")
      (node (ref "LED187") (pin "2") (pinfunction "DO_2") (pintype "bidirectional"))
      (node (ref "LED188") (pin "4") (pinfunction "DI_4") (pintype "bidirectional"))
    )
    (net (code "197") (name "Net-(LED188-DO)") (class "Default")
      (node (ref "LED188") (pin "2") (pinfunction "DO_2") (pintype "bidirectional"))
      (node (ref "LED189") (pin "4") (pinfunction "DI_4") (pintype "bidirectional"))
    )
    (net (code "198") (name "Net-(LED189-DO)") (class "Default")
      (node (ref "LED189") (pin "2") (pinfunction "DO_2") (pintype "bidirectional"))
      (node (ref "LED190") (pin "4") (pinfunction "DI_4") (pintype "bidirectional"))
    )
    (net (code "199") (name "Net-(LED190-DO)") (class "Default")
      (node (ref "LED190") (pin "2") (pinfunction "DO_2") (pintype "bidirectional"))
      (node (ref "LED191") (pin "4") (pinfunction "DI_4") (pintype "bidirectional"))
    )
    (net (code "200") (name "Net-(LED191-DO)") (class "Default")
      (node (ref "LED191") (pin "2") (pinfunction "DO_2") (pintype "bidirectional"))
      (node (ref "LED192") (pin "4") (pinfunction "DI_4") (pintype "bidirectional"))
    )
    (net (code "201") (name "Net-(LED192-DO)") (class "Default")
      (node (ref "LED192") (pin "2") (pinfunction "DO_2") (pintype "bidirectional"))
      (node (ref "PAD24") (pin "1") (pinfunction "P_1") (pintype "passive"))
    )
    (net (code "202") (name "unconnected-(TP1-PadTP)") (class "Default")
      (node (ref "TP1") (pin "TP") (pinfunction "TP_TP") (pintype "input"))
    )
    (net (code "203") (name "unconnected-(TP2-PadTP)") (class "Default")
      (node (ref "TP2") (pin "TP") (pinfunction "TP_TP") (pintype "input"))
    )
    (net (code "204") (name "unconnected-(TP3-PadTP)") (class "Default")
      (node (ref "TP3") (pin "TP") (pinfunction "TP_TP") (pintype "input"))
    )
    (net (code "205") (name "unconnected-(TP4-PadTP)") (class "Default")
      (node (ref "TP4") (pin "TP") (pinfunction "TP_TP") (pintype "input"))
    )
  )
)
